# lisa_l.net
KiCad netlist of a schematic drawn in EAGLE
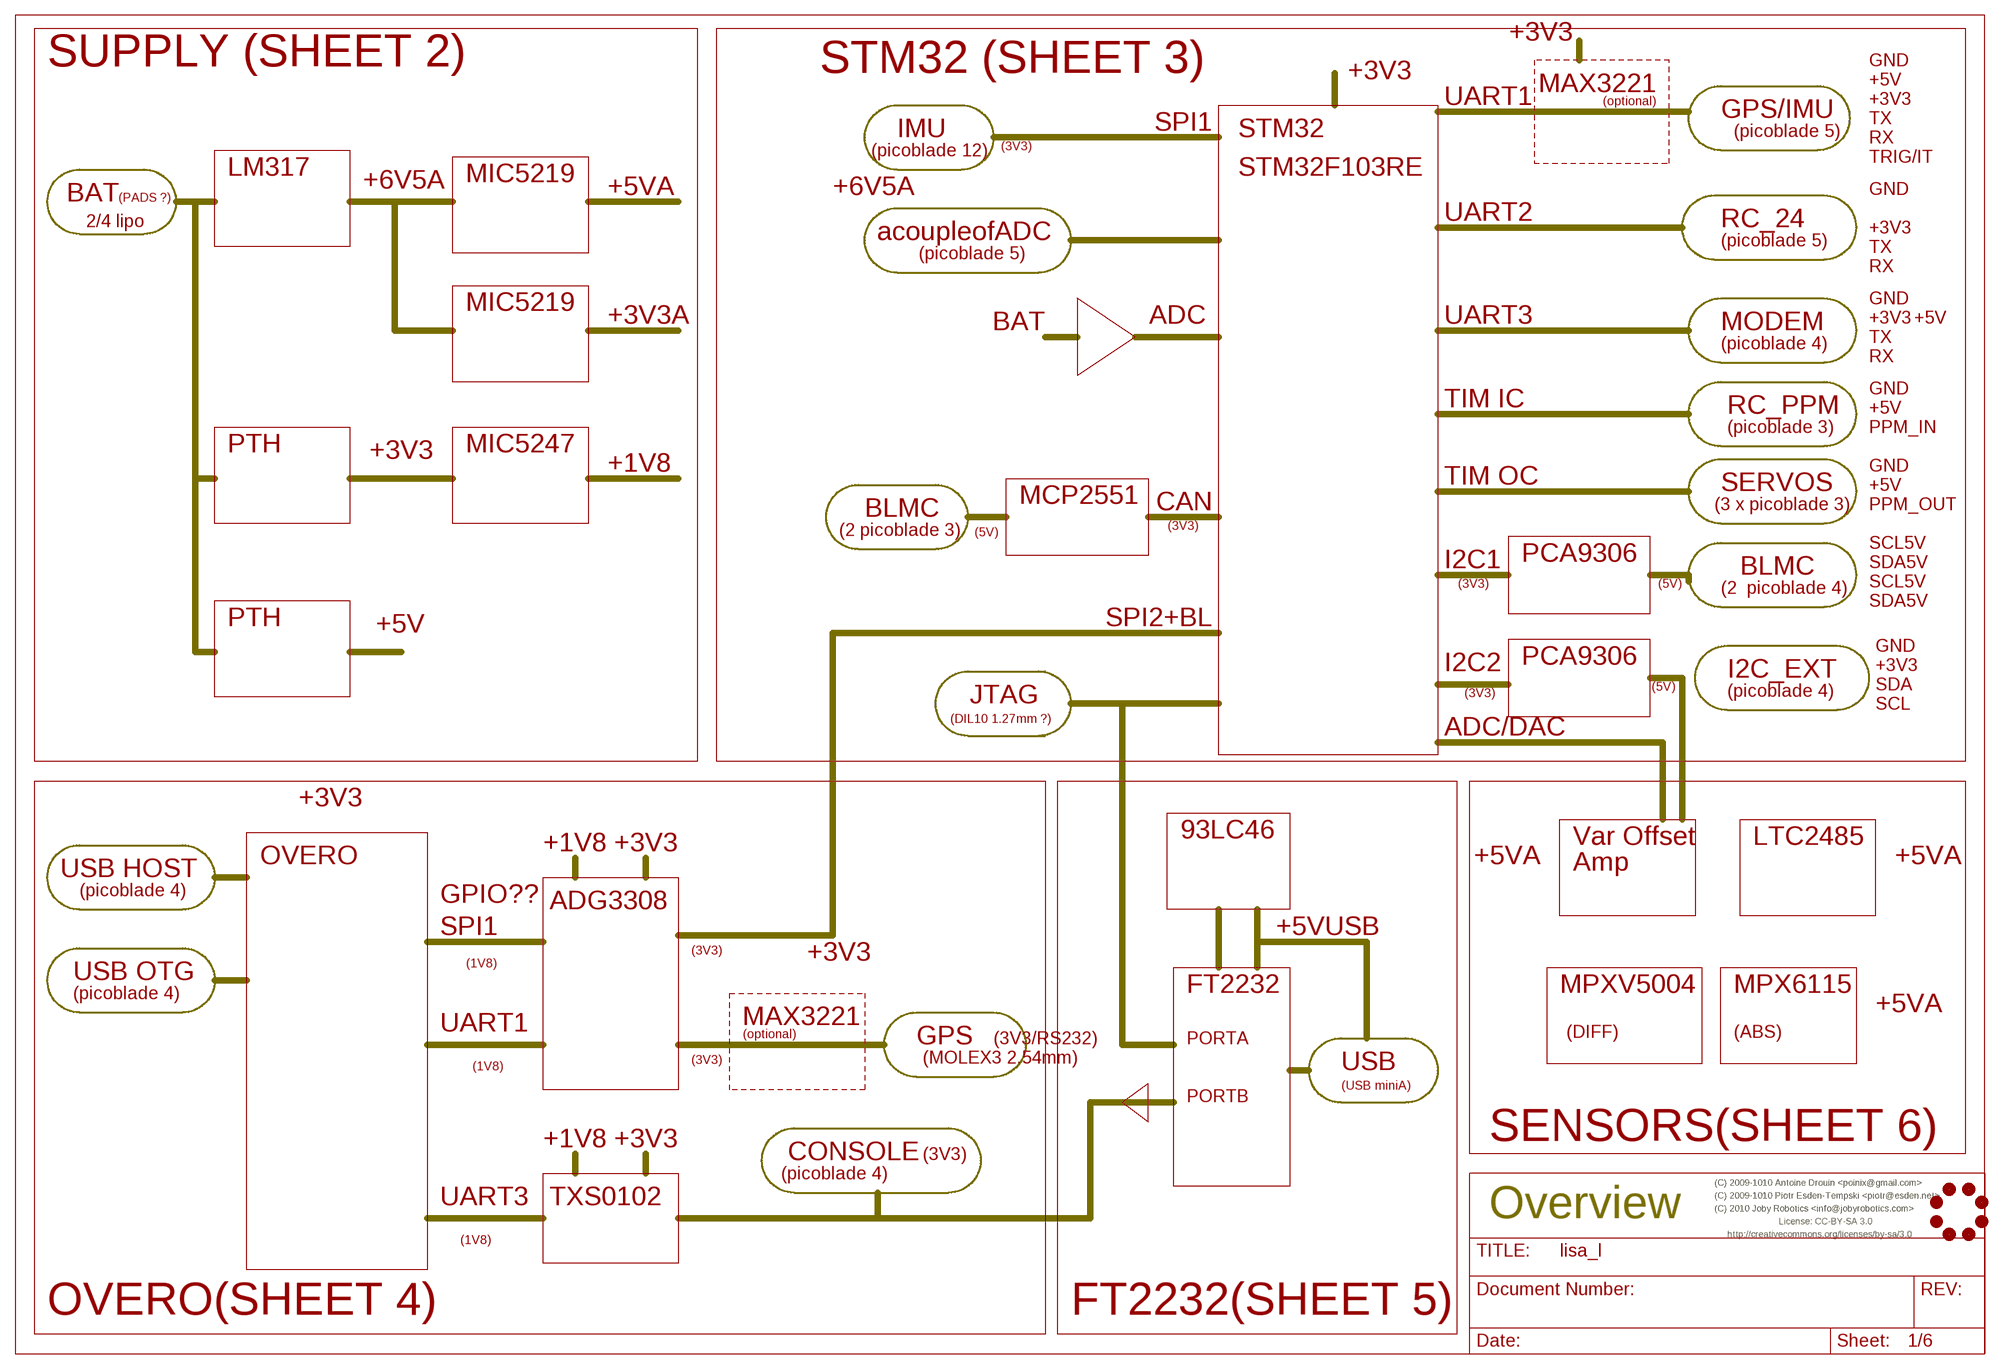
[diagram p0: schematic, sheet 1]
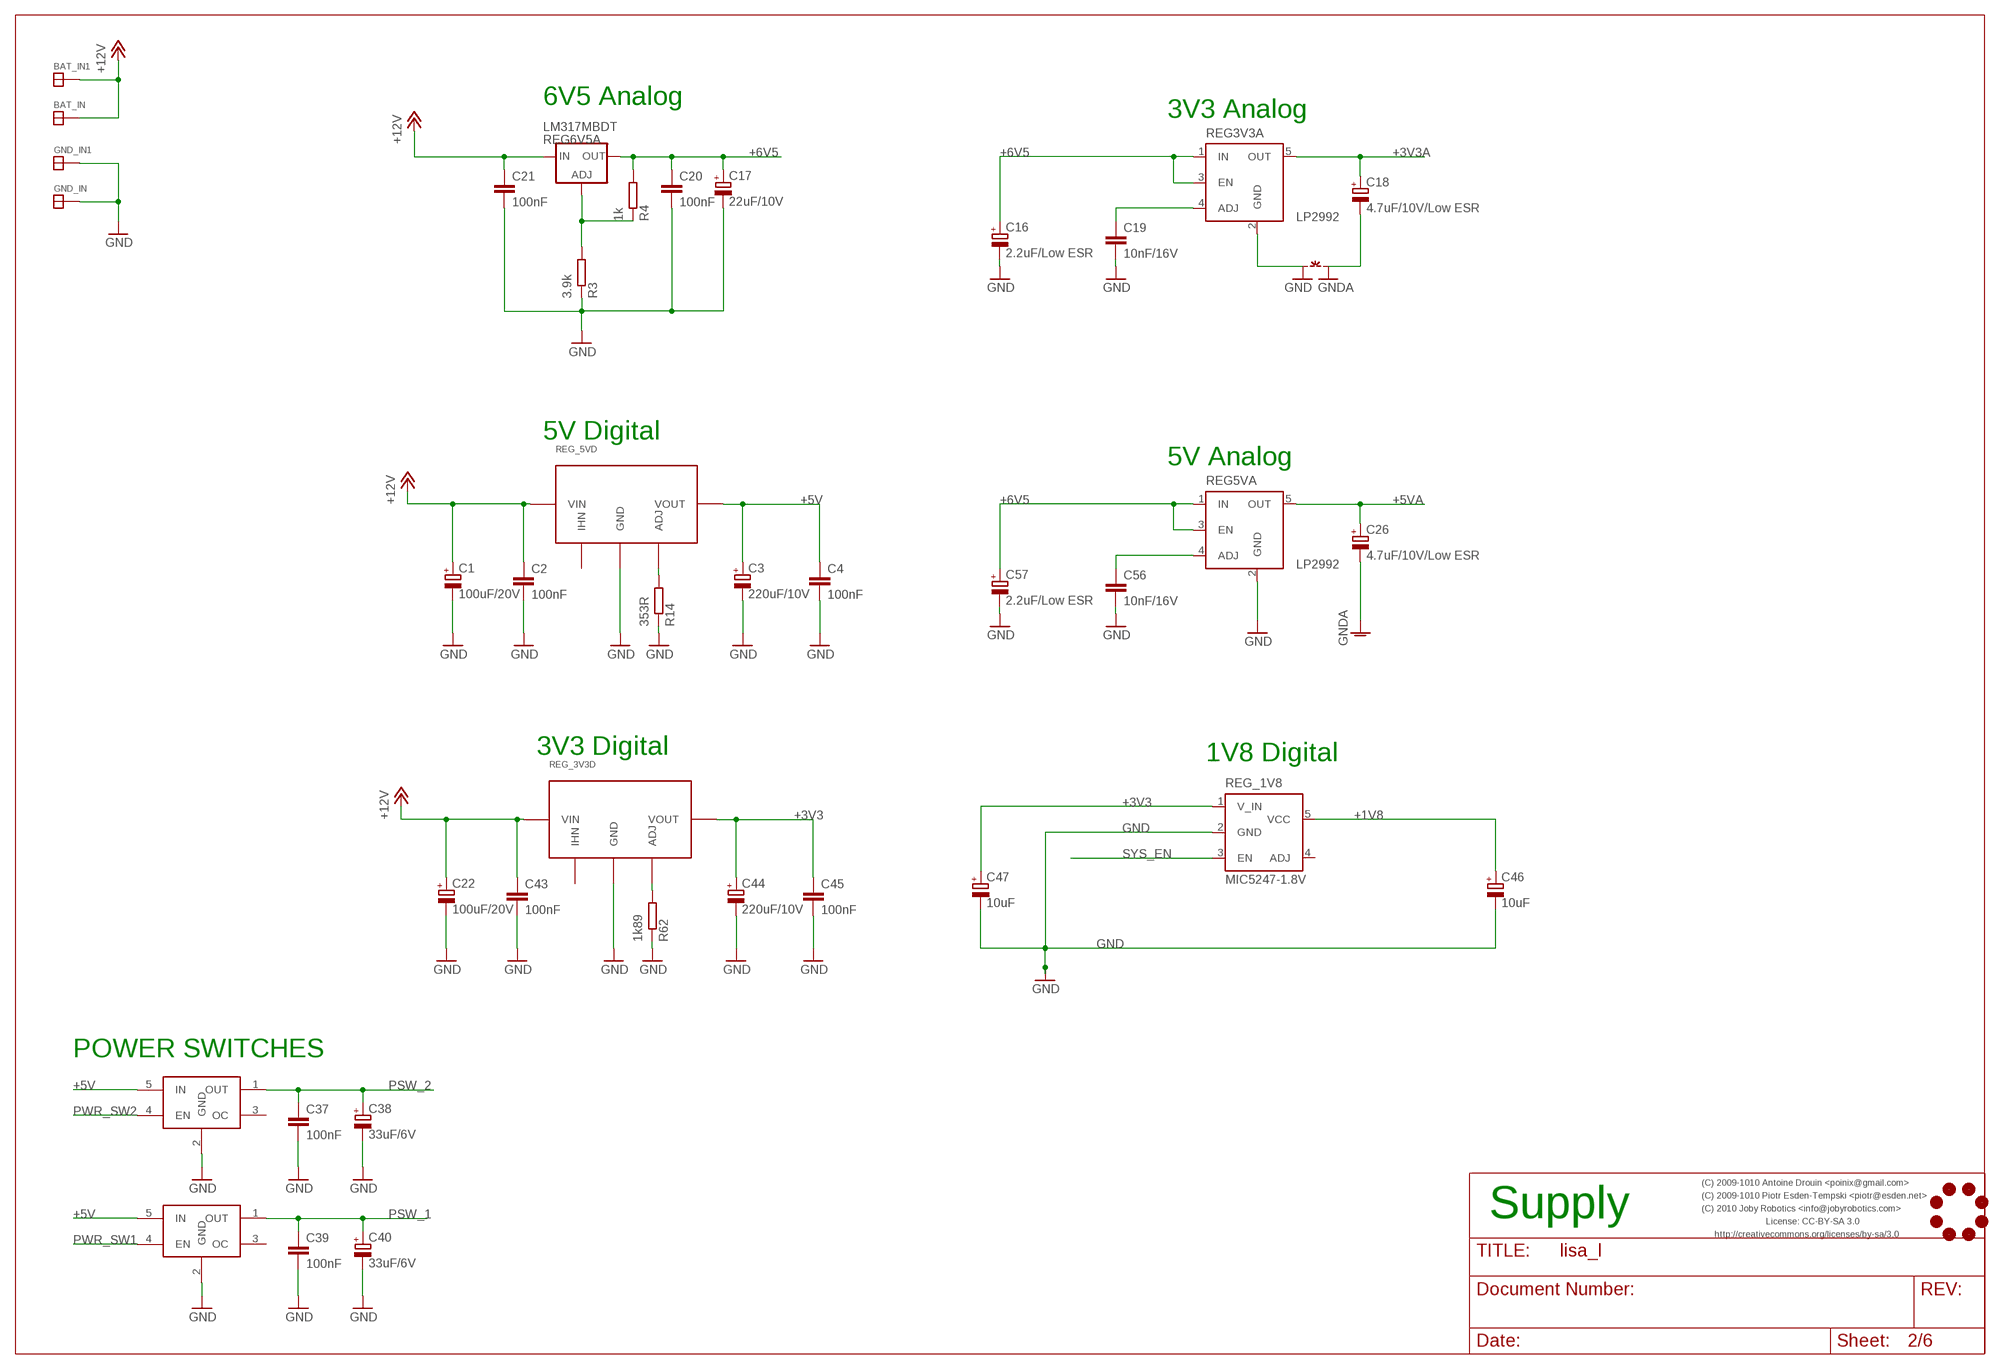
[diagram p1: schematic, sheet 2]
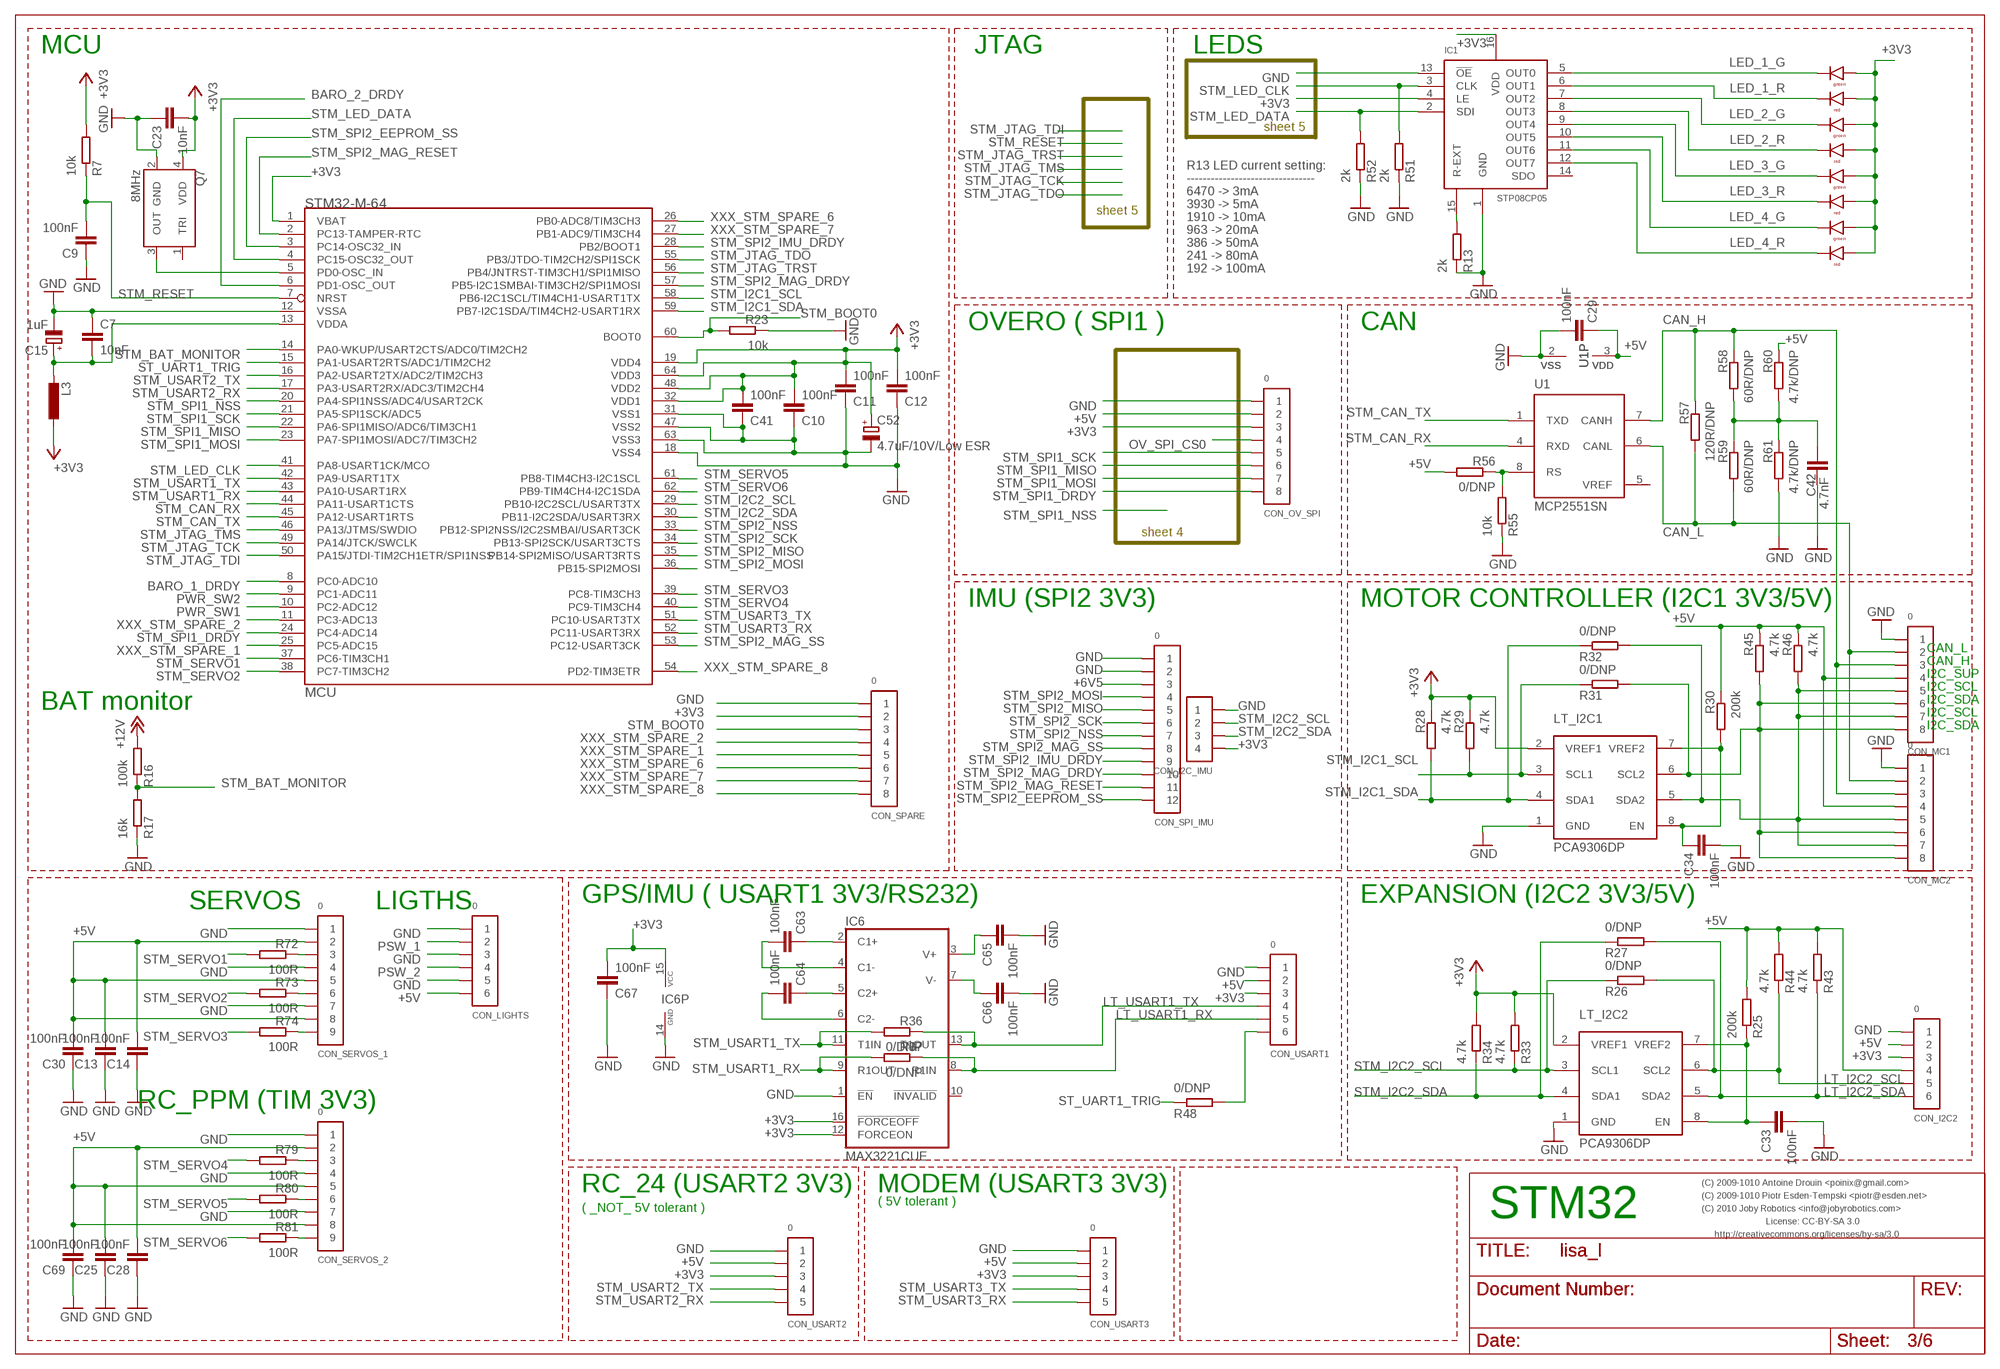
[diagram p2: schematic, sheet 3]
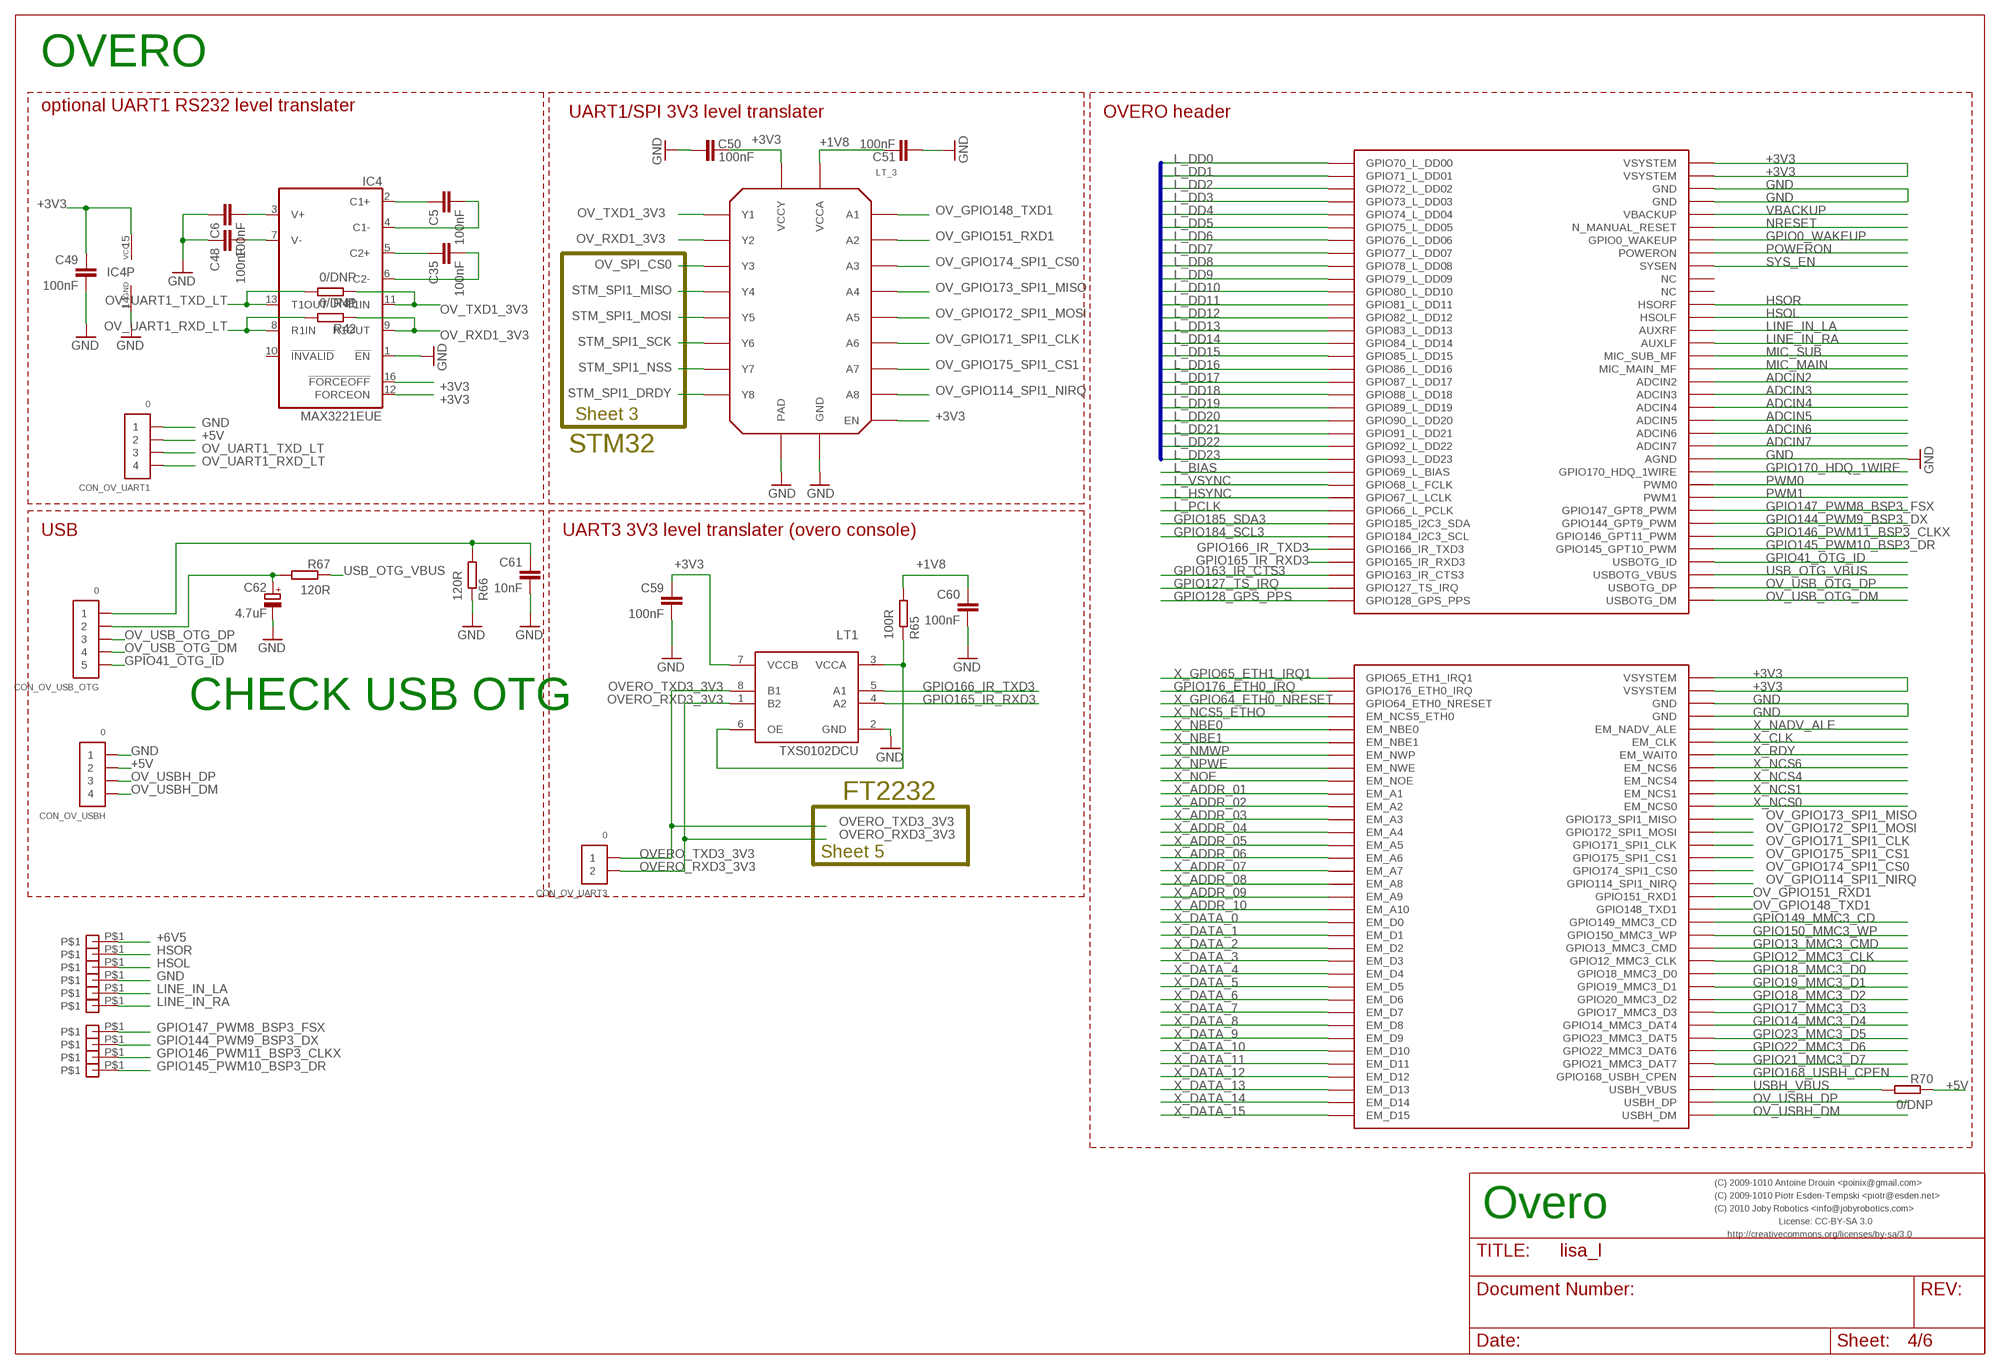
[diagram p3: schematic, sheet 4]
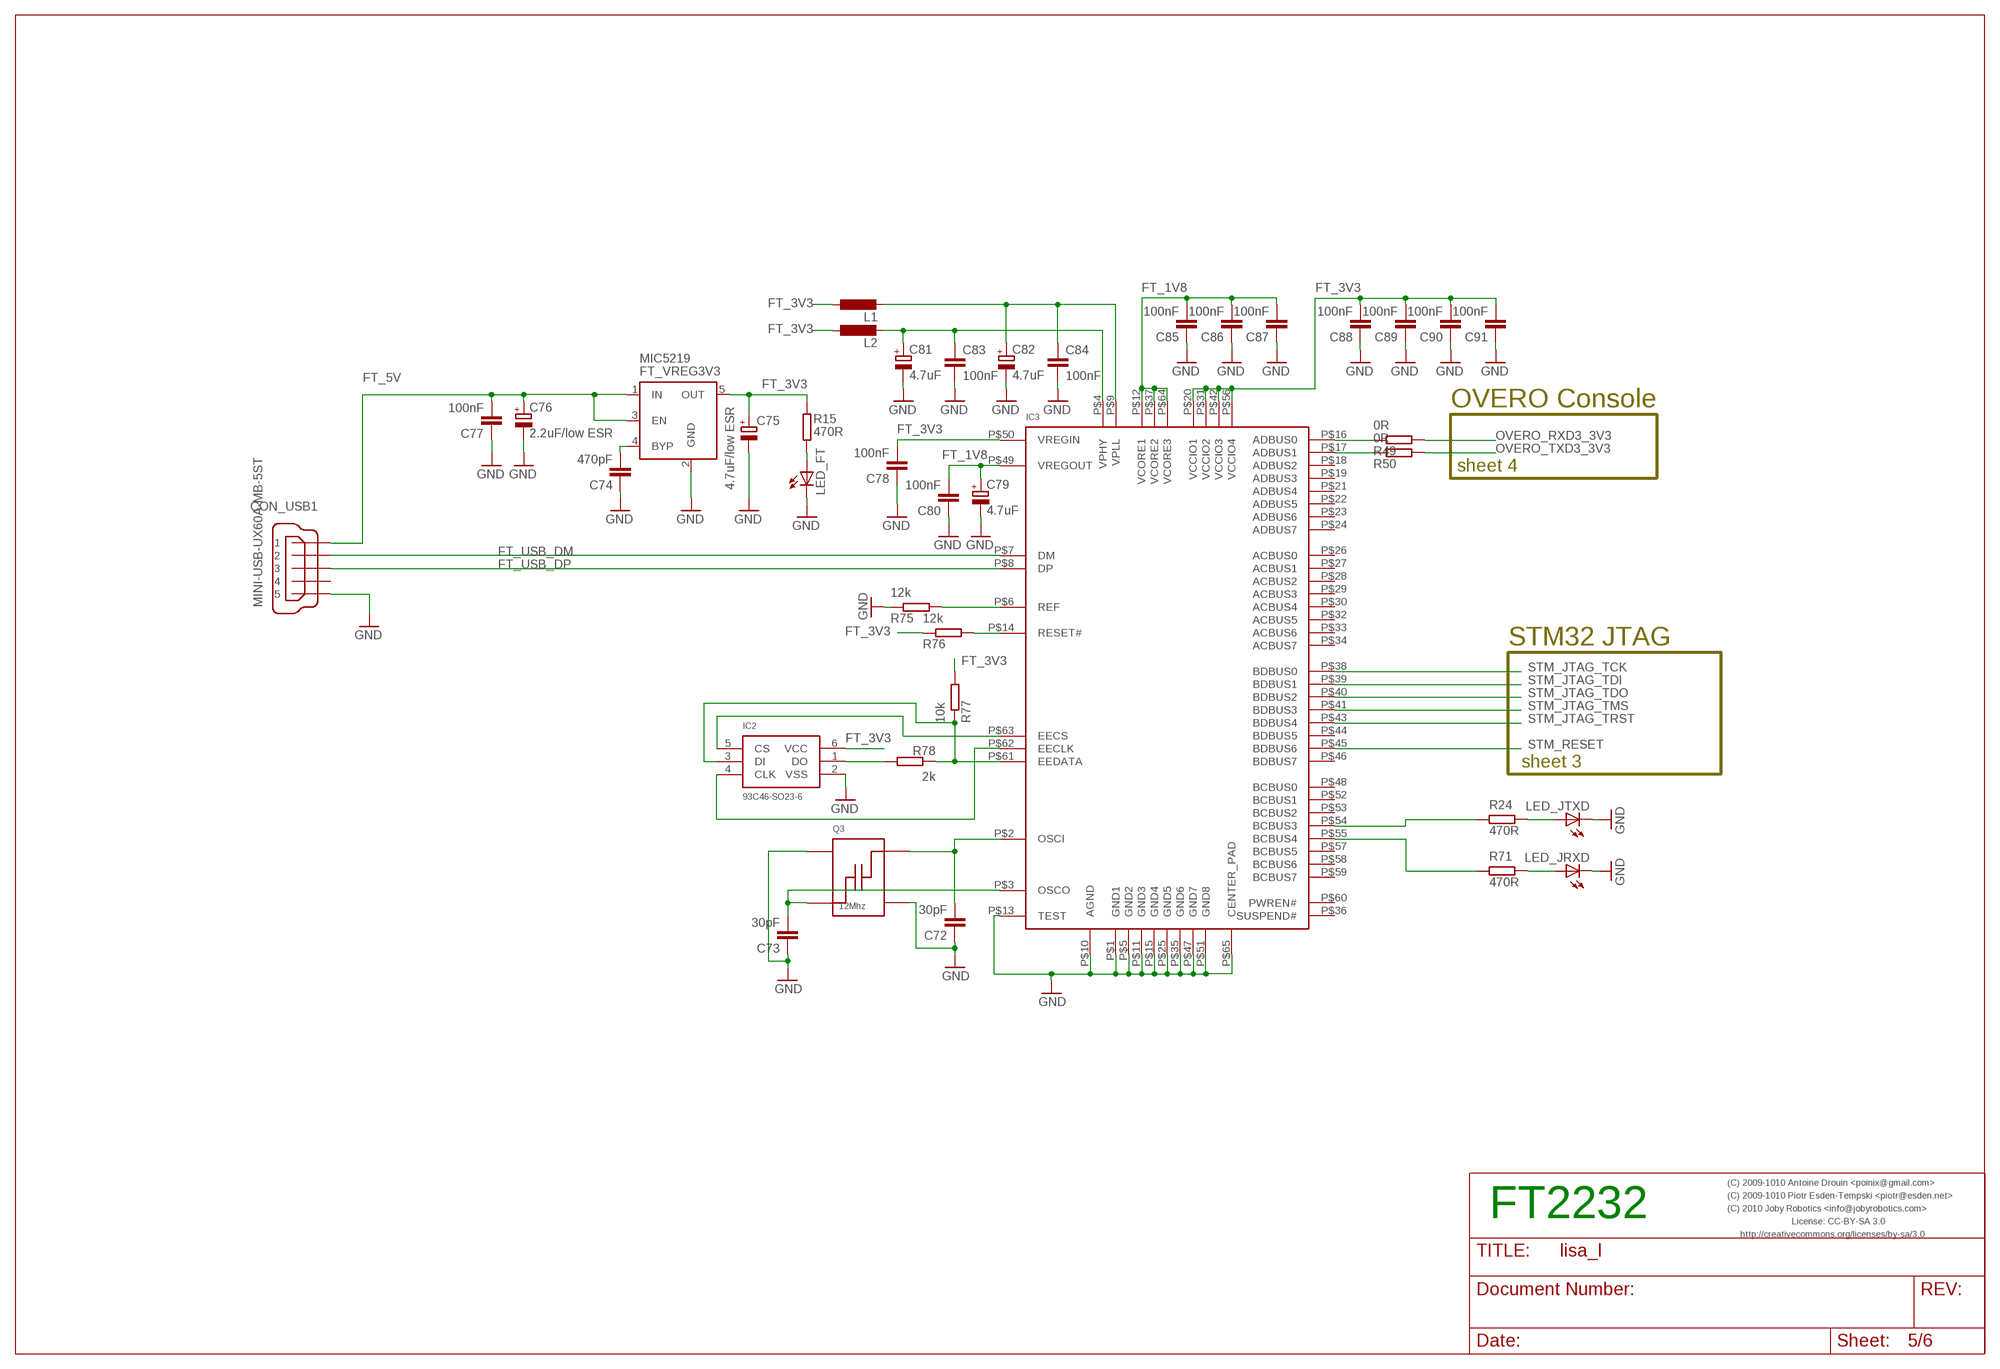
[diagram p4: schematic, sheet 5]
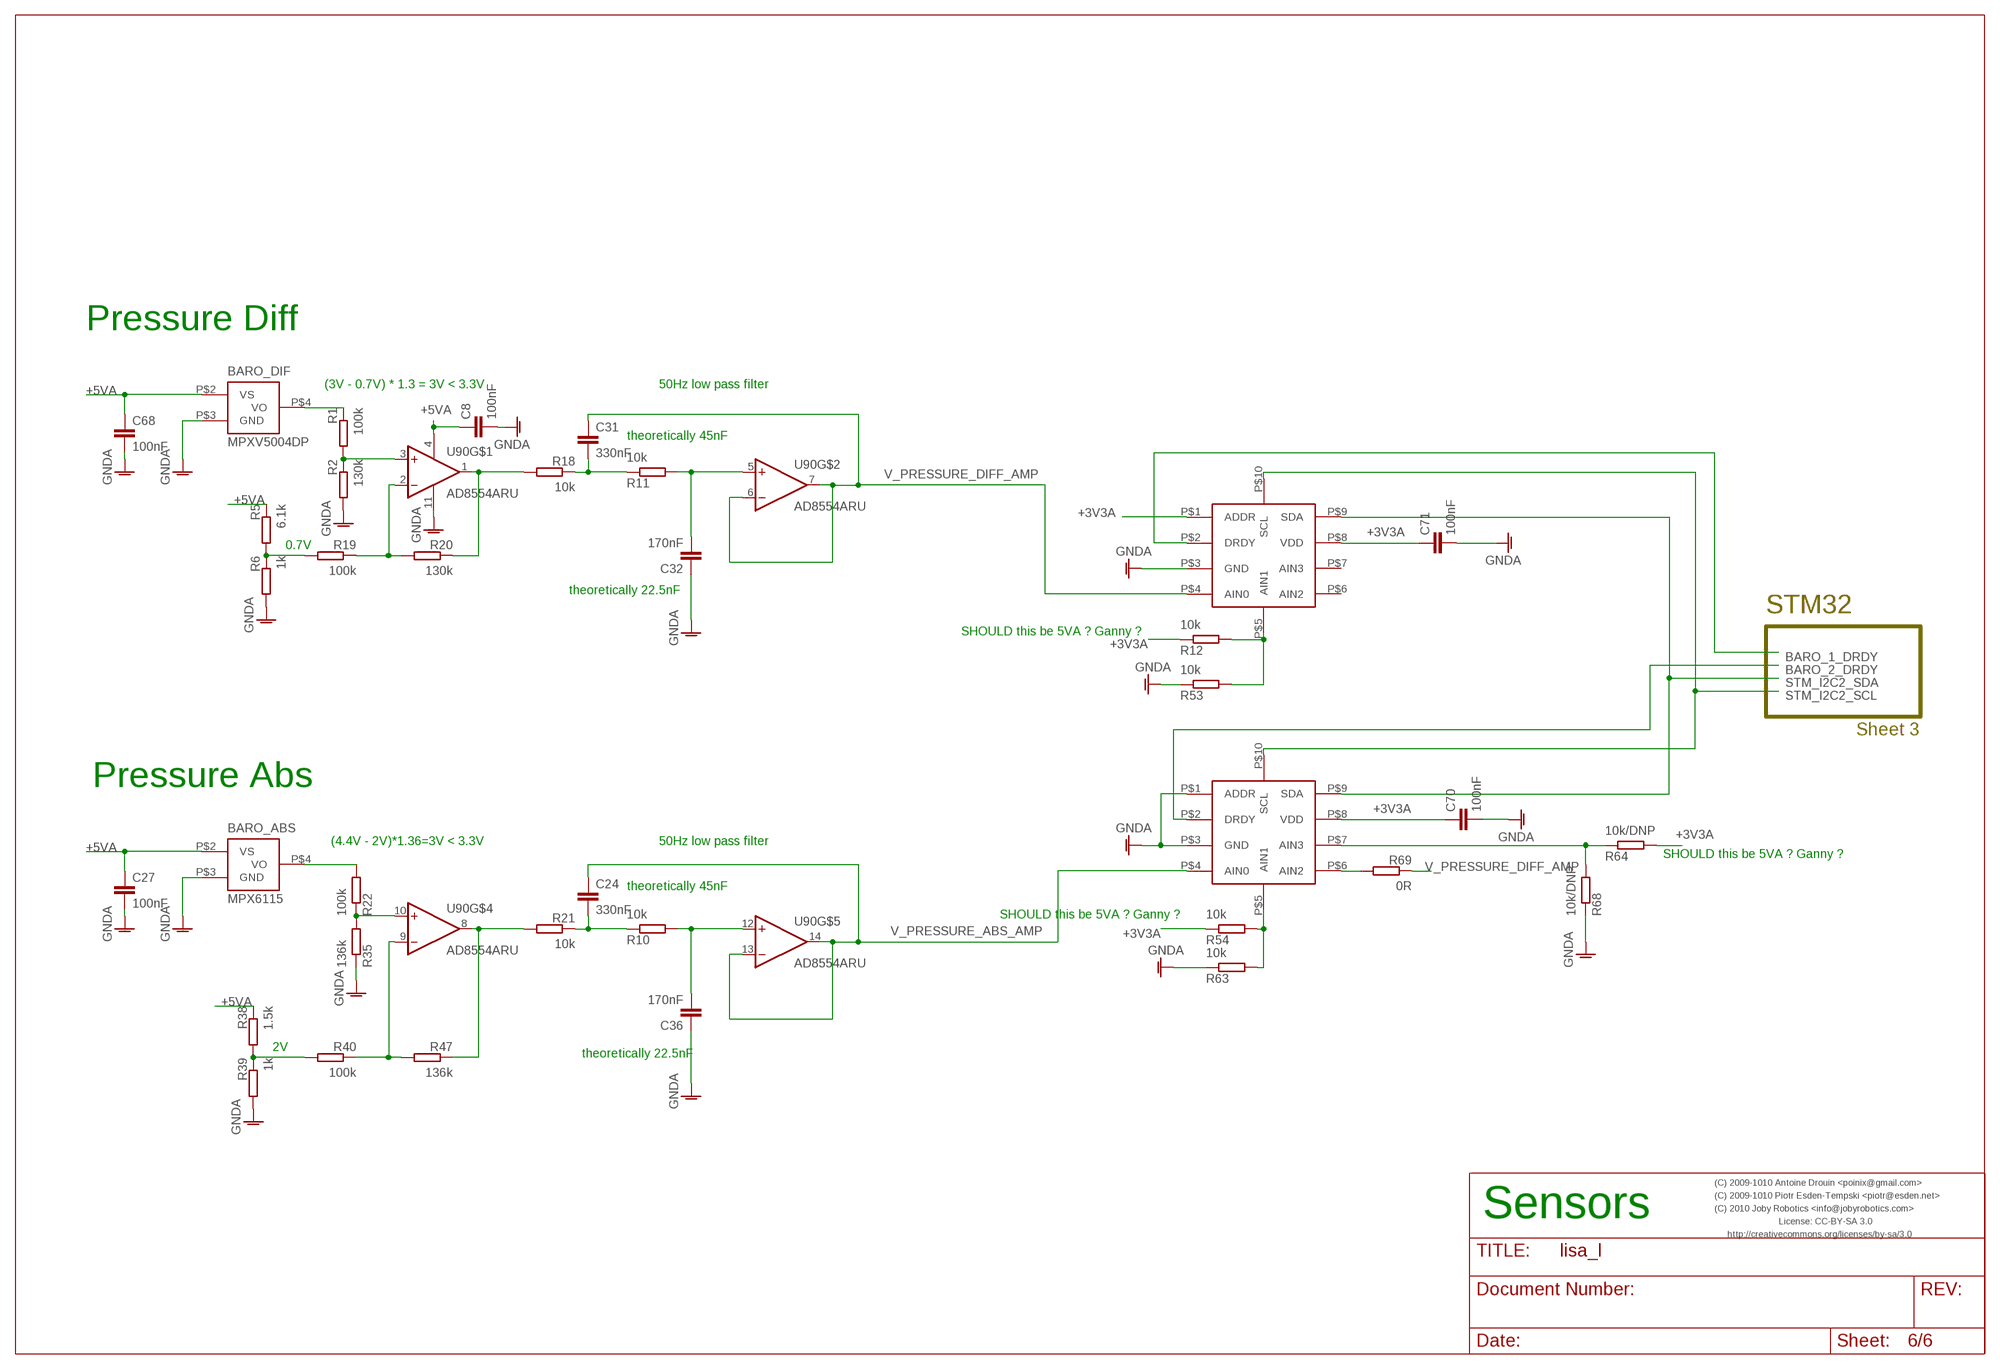
[diagram p5: schematic, sheet 6]

(export (version "E")
  (design (tool "Eeschema 10.0.6"))
  (components
    (comp (ref "C7")
      (value "10nF")
      (footprint "eagle-import:0603-CAP")
      (libsource (lib "eagle-import") (part "CAPACITOR-0603"))
    )
    (comp (ref "C9")
      (value "100nF")
      (footprint "eagle-import:0603-CAP")
      (libsource (lib "eagle-import") (part "res_cap_CAPACITOR-0603"))
    )
    (comp (ref "C10")
      (value "100nF")
      (footprint "eagle-import:0603-CAP")
      (libsource (lib "eagle-import") (part "CAPACITOR-0603"))
    )
    (comp (ref "C11")
      (value "100nF")
      (footprint "eagle-import:0603-CAP")
      (libsource (lib "eagle-import") (part "CAPACITOR-0603"))
    )
    (comp (ref "C12")
      (value "100nF")
      (footprint "eagle-import:0603-CAP")
      (libsource (lib "eagle-import") (part "CAPACITOR-0603"))
    )
    (comp (ref "C13")
      (value "100nF")
      (footprint "eagle-import:0603-CAP")
      (libsource (lib "eagle-import") (part "CAPACITOR-0603"))
    )
    (comp (ref "C14")
      (value "100nF")
      (footprint "eagle-import:0603-CAP")
      (libsource (lib "eagle-import") (part "CAPACITOR-0603"))
    )
    (comp (ref "C15")
      (value "1uF")
      (footprint "eagle-import:0603-POL-CAP")
      (libsource (lib "eagle-import") (part "CAPACITOR-POL-0603"))
    )
    (comp (ref "C23")
      (value "10nF")
      (footprint "eagle-import:0603-CAP")
      (libsource (lib "eagle-import") (part "CAPACITOR-0603"))
    )
    (comp (ref "C25")
      (value "100nF")
      (footprint "eagle-import:0603-CAP")
      (libsource (lib "eagle-import") (part "CAPACITOR-0603"))
    )
    (comp (ref "C28")
      (value "100nF")
      (footprint "eagle-import:0603-CAP")
      (libsource (lib "eagle-import") (part "CAPACITOR-0603"))
    )
    (comp (ref "C29")
      (value "100nF")
      (footprint "eagle-import:0603-CAP")
      (libsource (lib "eagle-import") (part "CAPACITOR-0603"))
    )
    (comp (ref "C30")
      (value "100nF")
      (footprint "eagle-import:0603-CAP")
      (libsource (lib "eagle-import") (part "CAPACITOR-0603"))
    )
    (comp (ref "C33")
      (value "100nF")
      (footprint "eagle-import:0603-CAP")
      (libsource (lib "eagle-import") (part "CAPACITOR-0603"))
    )
    (comp (ref "C34")
      (value "100nF")
      (footprint "eagle-import:0603-CAP")
      (libsource (lib "eagle-import") (part "CAPACITOR-0603"))
    )
    (comp (ref "C41")
      (value "100nF")
      (footprint "eagle-import:0603-CAP")
      (libsource (lib "eagle-import") (part "CAPACITOR-0603"))
    )
    (comp (ref "C42")
      (value "4.7nF")
      (footprint "eagle-import:0603-CAP")
      (libsource (lib "eagle-import") (part "CAPACITOR-0603"))
    )
    (comp (ref "C52")
      (value "4.7uF/10V/Low ESR")
      (footprint "eagle-import:0603-POL-CAP")
      (libsource (lib "eagle-import") (part "CAPACITOR-POL-0603"))
    )
    (comp (ref "C63")
      (value "100nF")
      (footprint "eagle-import:0603-CAP")
      (libsource (lib "eagle-import") (part "CAPACITOR-0603"))
    )
    (comp (ref "C64")
      (value "100nF")
      (footprint "eagle-import:0603-CAP")
      (libsource (lib "eagle-import") (part "CAPACITOR-0603"))
    )
    (comp (ref "C65")
      (value "100nF")
      (footprint "eagle-import:0603-CAP")
      (libsource (lib "eagle-import") (part "CAPACITOR-0603"))
    )
    (comp (ref "C66")
      (value "100nF")
      (footprint "eagle-import:0603-CAP")
      (libsource (lib "eagle-import") (part "CAPACITOR-0603"))
    )
    (comp (ref "C67")
      (value "100nF")
      (footprint "eagle-import:0603-CAP")
      (libsource (lib "eagle-import") (part "CAPACITOR-0603"))
    )
    (comp (ref "C69")
      (value "100nF")
      (footprint "eagle-import:0603-CAP")
      (libsource (lib "eagle-import") (part "CAPACITOR-0603"))
    )
    (comp (ref "CON_I2C2")
      (value "0")
      (footprint "eagle-import:PB-53261-06")
      (libsource (lib "eagle-import") (part "CONN_6-1-53261"))
    )
    (comp (ref "CON_I2C_IMU")
      (value "CONN_4-1-53398")
      (footprint "eagle-import:PB-53398-04")
      (libsource (lib "eagle-import") (part "CONN_4-1-53398"))
    )
    (comp (ref "CON_LIGHTS")
      (value "0")
      (footprint "eagle-import:PB-53261-06")
      (libsource (lib "eagle-import") (part "CONN_6-1-53261"))
    )
    (comp (ref "CON_MC1")
      (value "0")
      (footprint "eagle-import:PB-53261-08")
      (libsource (lib "eagle-import") (part "CONN_8-1-53261"))
    )
    (comp (ref "CON_MC2")
      (value "0")
      (footprint "eagle-import:PB-53261-08")
      (libsource (lib "eagle-import") (part "CONN_8-1-53261"))
    )
    (comp (ref "CON_OV_SPI")
      (value "0")
      (footprint "eagle-import:PB-53398-08")
      (libsource (lib "eagle-import") (part "CONN_8-1-53398"))
    )
    (comp (ref "CON_SERVOS_1")
      (value "0")
      (footprint "eagle-import:PB-53261-09")
      (libsource (lib "eagle-import") (part "CONN_9-1-53261"))
    )
    (comp (ref "CON_SERVOS_2")
      (value "0")
      (footprint "eagle-import:PB-53261-09")
      (libsource (lib "eagle-import") (part "CONN_9-1-53261"))
    )
    (comp (ref "CON_SPARE")
      (value "0")
      (footprint "eagle-import:PB-53261-08")
      (libsource (lib "eagle-import") (part "CONN_8-1-53261"))
    )
    (comp (ref "CON_SPI_IMU")
      (value "0")
      (footprint "eagle-import:PB-53398-12")
      (libsource (lib "eagle-import") (part "CONN_12-1-53398"))
    )
    (comp (ref "CON_USART1")
      (value "0")
      (footprint "eagle-import:PB-53398-06")
      (libsource (lib "eagle-import") (part "CONN_6-1-53398"))
    )
    (comp (ref "CON_USART2")
      (value "0")
      (footprint "eagle-import:PB-53261-05")
      (libsource (lib "eagle-import") (part "CONN_5-1-53261"))
    )
    (comp (ref "CON_USART3")
      (value "0")
      (footprint "eagle-import:PB-53261-05")
      (libsource (lib "eagle-import") (part "CONN_5-1-53261"))
    )
    (comp (ref "IC1")
      (value "STP08CP05")
      (footprint "eagle-import:TSSOP16")
      (libsource (lib "eagle-import") (part "STP08CP05"))
    )
    (comp (ref "IC6")
      (value "MAX3221CUE")
      (footprint "eagle-import:TSSOP16")
      (libsource (lib "eagle-import") (part "MAX3221UEC"))
    )
    (comp (ref "L3")
      (value "INDUCTOR-0603")
      (footprint "eagle-import:0603-IND")
      (libsource (lib "eagle-import") (part "INDUCTOR-0603"))
    )
    (comp (ref "LED_1")
      (value "LED_DUO")
      (footprint "eagle-import:DUO_LED")
      (libsource (lib "eagle-import") (part "LED_DUO"))
    )
    (comp (ref "LED_2")
      (value "LED_DUO")
      (footprint "eagle-import:DUO_LED")
      (libsource (lib "eagle-import") (part "LED_DUO"))
    )
    (comp (ref "LED_3")
      (value "LED_DUO")
      (footprint "eagle-import:DUO_LED")
      (libsource (lib "eagle-import") (part "LED_DUO"))
    )
    (comp (ref "LED_4")
      (value "LED_DUO")
      (footprint "eagle-import:DUO_LED")
      (libsource (lib "eagle-import") (part "LED_DUO"))
    )
    (comp (ref "LT_I2C1")
      (value "PCA9306DP")
      (footprint "eagle-import:TSSOP_B3")
      (libsource (lib "eagle-import") (part "PCA9306DP"))
    )
    (comp (ref "LT_I2C2")
      (value "PCA9306DP")
      (footprint "eagle-import:TSSOP_B3")
      (libsource (lib "eagle-import") (part "PCA9306DP"))
    )
    (comp (ref "MCU")
      (value "STM32-M-64")
      (footprint "eagle-import:LQFP64")
      (libsource (lib "eagle-import") (part "STM32-M-64"))
    )
    (comp (ref "Q7")
      (value "8MHz")
      (footprint "eagle-import:ASE_OSCILLATOR")
      (libsource (lib "eagle-import") (part "ASE_ASCILLATOR"))
    )
    (comp (ref "R7")
      (value "10k")
      (footprint "eagle-import:0603-RES")
      (libsource (lib "eagle-import") (part "RESISTOR-0603"))
    )
    (comp (ref "R13")
      (value "2k")
      (footprint "eagle-import:0603-RES")
      (libsource (lib "eagle-import") (part "RESISTOR-0603"))
    )
    (comp (ref "R16")
      (value "100k")
      (footprint "eagle-import:0603-RES")
      (libsource (lib "eagle-import") (part "RESISTOR-0603"))
    )
    (comp (ref "R17")
      (value "16k")
      (footprint "eagle-import:0603-RES")
      (libsource (lib "eagle-import") (part "RESISTOR-0603"))
    )
    (comp (ref "R23")
      (value "10k")
      (footprint "eagle-import:0603-RES")
      (libsource (lib "eagle-import") (part "RESISTOR-0603"))
    )
    (comp (ref "R25")
      (value "200k")
      (footprint "eagle-import:0603-RES")
      (libsource (lib "eagle-import") (part "RESISTOR-0603"))
    )
    (comp (ref "R26")
      (value "0/DNP")
      (footprint "eagle-import:0603-RES")
      (libsource (lib "eagle-import") (part "RESISTOR-0603"))
    )
    (comp (ref "R27")
      (value "0/DNP")
      (footprint "eagle-import:0603-RES")
      (libsource (lib "eagle-import") (part "RESISTOR-0603"))
    )
    (comp (ref "R28")
      (value "4.7k")
      (footprint "eagle-import:0603-RES")
      (libsource (lib "eagle-import") (part "RESISTOR-0603"))
    )
    (comp (ref "R29")
      (value "4.7k")
      (footprint "eagle-import:0603-RES")
      (libsource (lib "eagle-import") (part "RESISTOR-0603"))
    )
    (comp (ref "R30")
      (value "200k")
      (footprint "eagle-import:0603-RES")
      (libsource (lib "eagle-import") (part "RESISTOR-0603"))
    )
    (comp (ref "R31")
      (value "0/DNP")
      (footprint "eagle-import:0603-RES")
      (libsource (lib "eagle-import") (part "RESISTOR-0603"))
    )
    (comp (ref "R32")
      (value "0/DNP")
      (footprint "eagle-import:0603-RES")
      (libsource (lib "eagle-import") (part "RESISTOR-0603"))
    )
    (comp (ref "R33")
      (value "4.7k")
      (footprint "eagle-import:0603-RES")
      (libsource (lib "eagle-import") (part "RESISTOR-0603"))
    )
    (comp (ref "R34")
      (value "4.7k")
      (footprint "eagle-import:0603-RES")
      (libsource (lib "eagle-import") (part "RESISTOR-0603"))
    )
    (comp (ref "R36")
      (value "0/DNP")
      (footprint "eagle-import:0603-RES")
      (libsource (lib "eagle-import") (part "RESISTOR-0603"))
    )
    (comp (ref "R37")
      (value "0/DNP")
      (footprint "eagle-import:0603-RES")
      (libsource (lib "eagle-import") (part "RESISTOR-0603"))
    )
    (comp (ref "R43")
      (value "4.7k")
      (footprint "eagle-import:0603-RES")
      (libsource (lib "eagle-import") (part "RESISTOR-0603"))
    )
    (comp (ref "R44")
      (value "4.7k")
      (footprint "eagle-import:0603-RES")
      (libsource (lib "eagle-import") (part "RESISTOR-0603"))
    )
    (comp (ref "R45")
      (value "4.7k")
      (footprint "eagle-import:0603-RES")
      (libsource (lib "eagle-import") (part "RESISTOR-0603"))
    )
    (comp (ref "R46")
      (value "4.7k")
      (footprint "eagle-import:0603-RES")
      (libsource (lib "eagle-import") (part "RESISTOR-0603"))
    )
    (comp (ref "R48")
      (value "0/DNP")
      (footprint "eagle-import:0603-RES")
      (libsource (lib "eagle-import") (part "RESISTOR-0603"))
    )
    (comp (ref "R51")
      (value "2k")
      (footprint "eagle-import:0603-RES")
      (libsource (lib "eagle-import") (part "RESISTOR-0603"))
    )
    (comp (ref "R52")
      (value "2k")
      (footprint "eagle-import:0603-RES")
      (libsource (lib "eagle-import") (part "RESISTOR-0603"))
    )
    (comp (ref "R55")
      (value "10k")
      (footprint "eagle-import:0603-RES")
      (libsource (lib "eagle-import") (part "RESISTOR-0603"))
    )
    (comp (ref "R56")
      (value "0/DNP")
      (footprint "eagle-import:0603-RES")
      (libsource (lib "eagle-import") (part "RESISTOR-0603"))
    )
    (comp (ref "R57")
      (value "120R/DNP")
      (footprint "eagle-import:0603-RES")
      (libsource (lib "eagle-import") (part "RESISTOR-0603"))
    )
    (comp (ref "R58")
      (value "60R/DNP")
      (footprint "eagle-import:0603-RES")
      (libsource (lib "eagle-import") (part "RESISTOR-0603"))
    )
    (comp (ref "R59")
      (value "60R/DNP")
      (footprint "eagle-import:0603-RES")
      (libsource (lib "eagle-import") (part "RESISTOR-0603"))
    )
    (comp (ref "R60")
      (value "4.7k/DNP")
      (footprint "eagle-import:0603-RES")
      (libsource (lib "eagle-import") (part "RESISTOR-0603"))
    )
    (comp (ref "R61")
      (value "4.7k/DNP")
      (footprint "eagle-import:0603-RES")
      (libsource (lib "eagle-import") (part "RESISTOR-0603"))
    )
    (comp (ref "R72")
      (value "100R")
      (footprint "eagle-import:0603-RES")
      (libsource (lib "eagle-import") (part "RESISTOR-0603"))
    )
    (comp (ref "R73")
      (value "100R")
      (footprint "eagle-import:0603-RES")
      (libsource (lib "eagle-import") (part "RESISTOR-0603"))
    )
    (comp (ref "R74")
      (value "100R")
      (footprint "eagle-import:0603-RES")
      (libsource (lib "eagle-import") (part "RESISTOR-0603"))
    )
    (comp (ref "R79")
      (value "100R")
      (footprint "eagle-import:0603-RES")
      (libsource (lib "eagle-import") (part "RESISTOR-0603"))
    )
    (comp (ref "R80")
      (value "100R")
      (footprint "eagle-import:0603-RES")
      (libsource (lib "eagle-import") (part "RESISTOR-0603"))
    )
    (comp (ref "R81")
      (value "100R")
      (footprint "eagle-import:0603-RES")
      (libsource (lib "eagle-import") (part "RESISTOR-0603"))
    )
    (comp (ref "U1")
      (value "MCP2551SN")
      (footprint "eagle-import:SO-08")
      (libsource (lib "eagle-import") (part "MCP2551SN"))
    )
    (comp (ref "C5")
      (value "100nF")
      (footprint "eagle-import:0603-CAP")
      (libsource (lib "eagle-import") (part "CAPACITOR-0603"))
    )
    (comp (ref "C6")
      (value "100nF")
      (footprint "eagle-import:0603-CAP")
      (libsource (lib "eagle-import") (part "CAPACITOR-0603"))
    )
    (comp (ref "C35")
      (value "100nF")
      (footprint "eagle-import:0603-CAP")
      (libsource (lib "eagle-import") (part "CAPACITOR-0603"))
    )
    (comp (ref "C48")
      (value "100nF")
      (footprint "eagle-import:0603-CAP")
      (libsource (lib "eagle-import") (part "CAPACITOR-0603"))
    )
    (comp (ref "C49")
      (value "100nF")
      (footprint "eagle-import:0603-CAP")
      (libsource (lib "eagle-import") (part "CAPACITOR-0603"))
    )
    (comp (ref "C50")
      (value "100nF")
      (footprint "eagle-import:0603-CAP")
      (libsource (lib "eagle-import") (part "CAPACITOR-0603"))
    )
    (comp (ref "C51")
      (value "100nF")
      (footprint "eagle-import:0603-CAP")
      (libsource (lib "eagle-import") (part "CAPACITOR-0603"))
    )
    (comp (ref "C59")
      (value "100nF")
      (footprint "eagle-import:0603-CAP")
      (libsource (lib "eagle-import") (part "CAPACITOR-0603"))
    )
    (comp (ref "C60")
      (value "100nF")
      (footprint "eagle-import:0603-CAP")
      (libsource (lib "eagle-import") (part "CAPACITOR-0603"))
    )
    (comp (ref "C61")
      (value "10nF")
      (footprint "eagle-import:0603-CAP")
      (libsource (lib "eagle-import") (part "CAPACITOR-0603"))
    )
    (comp (ref "C62")
      (value "4.7uF")
      (footprint "eagle-import:0603-POL-CAP")
      (libsource (lib "eagle-import") (part "CAPACITOR-POL-0603"))
    )
    (comp (ref "CON_OV_UART1")
      (value "0")
      (footprint "eagle-import:PB-53261-04")
      (libsource (lib "eagle-import") (part "CONN_4-1-53261"))
    )
    (comp (ref "CON_OV_UART3")
      (value "0")
      (footprint "eagle-import:PB-53261-02")
      (libsource (lib "eagle-import") (part "CONN_2-1-53261"))
    )
    (comp (ref "CON_OV_USBH")
      (value "0")
      (footprint "eagle-import:PB-53261-04")
      (libsource (lib "eagle-import") (part "CONN_4-1-53261"))
    )
    (comp (ref "CON_OV_USB_OTG")
      (value "0")
      (footprint "eagle-import:PB-53261-05")
      (libsource (lib "eagle-import") (part "CONN_5-1-53261"))
    )
    (comp (ref "IC4")
      (value "MAX3221EUE")
      (footprint "eagle-import:TSSOP16")
      (libsource (lib "eagle-import") (part "MAX3221UEE"))
    )
    (comp (ref "J3&4")
      (value "OVERO")
      (footprint "eagle-import:OVERO")
      (libsource (lib "eagle-import") (part "OVERO"))
    )
    (comp (ref "LT1")
      (value "TXS0102DCU")
      (footprint "eagle-import:US8")
      (libsource (lib "eagle-import") (part "TXS0102DCU"))
    )
    (comp (ref "LT_3")
      (value "AD3308BCPZ")
      (footprint "eagle-import:LFCSP-20")
      (libsource (lib "eagle-import") (part "AD3308BCPZ"))
    )
    (comp (ref "R41")
      (value "0/DNP")
      (footprint "eagle-import:0603-RES")
      (libsource (lib "eagle-import") (part "RESISTOR-0603"))
    )
    (comp (ref "R42")
      (value "0/DNP")
      (footprint "eagle-import:0603-RES")
      (libsource (lib "eagle-import") (part "RESISTOR-0603"))
    )
    (comp (ref "R65")
      (value "100R")
      (footprint "eagle-import:0603-RES")
      (libsource (lib "eagle-import") (part "RESISTOR-0603"))
    )
    (comp (ref "R66")
      (value "120R")
      (footprint "eagle-import:0603-RES")
      (libsource (lib "eagle-import") (part "RESISTOR-0603"))
    )
    (comp (ref "R67")
      (value "120R")
      (footprint "eagle-import:0603-RES")
      (libsource (lib "eagle-import") (part "RESISTOR-0603"))
    )
    (comp (ref "R70")
      (value "0/DNP")
      (footprint "eagle-import:0603-RES")
      (libsource (lib "eagle-import") (part "RESISTOR-0603"))
    )
    (comp (ref "U$1")
      (value "SOLDER_PAD")
      (footprint "eagle-import:SOLDER_PAD_SMALL")
      (libsource (lib "eagle-import") (part "poinix_SOLDER_PAD"))
    )
    (comp (ref "U$2")
      (value "SOLDER_PAD")
      (footprint "eagle-import:SOLDER_PAD_SMALL")
      (libsource (lib "eagle-import") (part "poinix_SOLDER_PAD"))
    )
    (comp (ref "U$3")
      (value "SOLDER_PAD")
      (footprint "eagle-import:SOLDER_PAD_SMALL")
      (libsource (lib "eagle-import") (part "poinix_SOLDER_PAD"))
    )
    (comp (ref "U$4")
      (value "SOLDER_PAD")
      (footprint "eagle-import:SOLDER_PAD_SMALL")
      (libsource (lib "eagle-import") (part "poinix_SOLDER_PAD"))
    )
    (comp (ref "U$5")
      (value "SOLDER_PAD")
      (footprint "eagle-import:SOLDER_PAD_SMALL")
      (libsource (lib "eagle-import") (part "poinix_SOLDER_PAD"))
    )
    (comp (ref "U$6")
      (value "SOLDER_PAD")
      (footprint "eagle-import:SOLDER_PAD_SMALL")
      (libsource (lib "eagle-import") (part "poinix_SOLDER_PAD"))
    )
    (comp (ref "U$7")
      (value "SOLDER_PAD")
      (footprint "eagle-import:SOLDER_PAD_SMALL")
      (libsource (lib "eagle-import") (part "poinix_SOLDER_PAD"))
    )
    (comp (ref "U$8")
      (value "SOLDER_PAD")
      (footprint "eagle-import:SOLDER_PAD_SMALL")
      (libsource (lib "eagle-import") (part "poinix_SOLDER_PAD"))
    )
    (comp (ref "U$9")
      (value "SOLDER_PAD")
      (footprint "eagle-import:SOLDER_PAD_SMALL")
      (libsource (lib "eagle-import") (part "poinix_SOLDER_PAD"))
    )
    (comp (ref "U$10")
      (value "SOLDER_PAD")
      (footprint "eagle-import:SOLDER_PAD_SMALL")
      (libsource (lib "eagle-import") (part "poinix_SOLDER_PAD"))
    )
    (comp (ref "C72")
      (value "30pF")
      (footprint "eagle-import:0603-CAP")
      (libsource (lib "eagle-import") (part "res_cap_CAPACITOR-0603"))
    )
    (comp (ref "C73")
      (value "30pF")
      (footprint "eagle-import:0603-CAP")
      (libsource (lib "eagle-import") (part "res_cap_CAPACITOR-0603"))
    )
    (comp (ref "C74")
      (value "470pF")
      (footprint "eagle-import:0603-CAP")
      (libsource (lib "eagle-import") (part "res_cap_CAPACITOR-0603"))
    )
    (comp (ref "C75")
      (value "4.7uF/low ESR")
      (footprint "eagle-import:0603-POL-CAP")
      (libsource (lib "eagle-import") (part "CAPACITOR-POL-0603"))
    )
    (comp (ref "C76")
      (value "2.2uF/low ESR")
      (footprint "eagle-import:0603-POL-CAP")
      (libsource (lib "eagle-import") (part "CAPACITOR-POL-0603"))
    )
    (comp (ref "C77")
      (value "100nF")
      (footprint "eagle-import:0603-CAP")
      (libsource (lib "eagle-import") (part "res_cap_CAPACITOR-0603"))
    )
    (comp (ref "C78")
      (value "100nF")
      (footprint "eagle-import:0603-CAP")
      (libsource (lib "eagle-import") (part "res_cap_CAPACITOR-0603"))
    )
    (comp (ref "C79")
      (value "4.7uF")
      (footprint "eagle-import:0603-POL-CAP")
      (libsource (lib "eagle-import") (part "CAPACITOR-POL-0603"))
    )
    (comp (ref "C80")
      (value "100nF")
      (footprint "eagle-import:0603-CAP")
      (libsource (lib "eagle-import") (part "res_cap_CAPACITOR-0603"))
    )
    (comp (ref "C81")
      (value "4.7uF")
      (footprint "eagle-import:0603-POL-CAP")
      (libsource (lib "eagle-import") (part "CAPACITOR-POL-0603"))
    )
    (comp (ref "C82")
      (value "4.7uF")
      (footprint "eagle-import:0603-POL-CAP")
      (libsource (lib "eagle-import") (part "CAPACITOR-POL-0603"))
    )
    (comp (ref "C83")
      (value "100nF")
      (footprint "eagle-import:0603-CAP")
      (libsource (lib "eagle-import") (part "res_cap_CAPACITOR-0603"))
    )
    (comp (ref "C84")
      (value "100nF")
      (footprint "eagle-import:0603-CAP")
      (libsource (lib "eagle-import") (part "res_cap_CAPACITOR-0603"))
    )
    (comp (ref "C85")
      (value "100nF")
      (footprint "eagle-import:0603-CAP")
      (libsource (lib "eagle-import") (part "res_cap_CAPACITOR-0603"))
    )
    (comp (ref "C86")
      (value "100nF")
      (footprint "eagle-import:0603-CAP")
      (libsource (lib "eagle-import") (part "res_cap_CAPACITOR-0603"))
    )
    (comp (ref "C87")
      (value "100nF")
      (footprint "eagle-import:0603-CAP")
      (libsource (lib "eagle-import") (part "res_cap_CAPACITOR-0603"))
    )
    (comp (ref "C88")
      (value "100nF")
      (footprint "eagle-import:0603-CAP")
      (libsource (lib "eagle-import") (part "res_cap_CAPACITOR-0603"))
    )
    (comp (ref "C89")
      (value "100nF")
      (footprint "eagle-import:0603-CAP")
      (libsource (lib "eagle-import") (part "res_cap_CAPACITOR-0603"))
    )
    (comp (ref "C90")
      (value "100nF")
      (footprint "eagle-import:0603-CAP")
      (libsource (lib "eagle-import") (part "res_cap_CAPACITOR-0603"))
    )
    (comp (ref "C91")
      (value "100nF")
      (footprint "eagle-import:0603-CAP")
      (libsource (lib "eagle-import") (part "res_cap_CAPACITOR-0603"))
    )
    (comp (ref "CON_USB1")
      (value "MINI-USB-UX60A-MB-5ST")
      (footprint "eagle-import:UX60A-MB-5ST")
      (libsource (lib "eagle-import") (part "MINI-USB-UX60A-MB-5ST"))
    )
    (comp (ref "FT_VREG3V3")
      (value "MIC5219")
      (footprint "eagle-import:SOT23-5")
      (libsource (lib "eagle-import") (part "MIC5219XX"))
    )
    (comp (ref "IC2")
      (value "93C46-SO23-6")
      (footprint "eagle-import:SO23-6")
      (libsource (lib "eagle-import") (part "93C46-SO23-6"))
    )
    (comp (ref "IC3")
      (value "FT2232HQ")
      (footprint "eagle-import:QFN64")
      (libsource (lib "eagle-import") (part "FT2232HQ"))
    )
    (comp (ref "L1")
      (value "INDUCTOR-0603")
      (footprint "eagle-import:0603-IND")
      (libsource (lib "eagle-import") (part "INDUCTOR-0603"))
    )
    (comp (ref "L2")
      (value "INDUCTOR-0603")
      (footprint "eagle-import:0603-IND")
      (libsource (lib "eagle-import") (part "INDUCTOR-0603"))
    )
    (comp (ref "LED_FT")
      (value "LED-0603")
      (footprint "eagle-import:0603-LED")
      (libsource (lib "eagle-import") (part "LED-0603"))
    )
    (comp (ref "LED_JRXD")
      (value "LED-0603")
      (footprint "eagle-import:0603-LED")
      (libsource (lib "eagle-import") (part "LED-0603"))
    )
    (comp (ref "LED_JTXD")
      (value "LED-0603")
      (footprint "eagle-import:0603-LED")
      (libsource (lib "eagle-import") (part "LED-0603"))
    )
    (comp (ref "Q3")
      (value "12Mhz")
      (footprint "eagle-import:ABM8")
      (libsource (lib "eagle-import") (part "ABM8"))
    )
    (comp (ref "R15")
      (value "470R")
      (footprint "eagle-import:0603-RES")
      (libsource (lib "eagle-import") (part "res_cap_RESISTOR-0603"))
    )
    (comp (ref "R24")
      (value "470R")
      (footprint "eagle-import:0603-RES")
      (libsource (lib "eagle-import") (part "res_cap_RESISTOR-0603"))
    )
    (comp (ref "R49")
      (value "0R")
      (footprint "eagle-import:0603-RES")
      (libsource (lib "eagle-import") (part "RESISTOR-0603"))
    )
    (comp (ref "R50")
      (value "0R")
      (footprint "eagle-import:0603-RES")
      (libsource (lib "eagle-import") (part "RESISTOR-0603"))
    )
    (comp (ref "R71")
      (value "470R")
      (footprint "eagle-import:0603-RES")
      (libsource (lib "eagle-import") (part "res_cap_RESISTOR-0603"))
    )
    (comp (ref "R75")
      (value "12k")
      (footprint "eagle-import:0603-RES")
      (libsource (lib "eagle-import") (part "res_cap_RESISTOR-0603"))
    )
    (comp (ref "R76")
      (value "12k")
      (footprint "eagle-import:0603-RES")
      (libsource (lib "eagle-import") (part "res_cap_RESISTOR-0603"))
    )
    (comp (ref "R77")
      (value "10k")
      (footprint "eagle-import:0603-RES")
      (libsource (lib "eagle-import") (part "res_cap_RESISTOR-0603"))
    )
    (comp (ref "R78")
      (value "2k")
      (footprint "eagle-import:0603-RES")
      (libsource (lib "eagle-import") (part "res_cap_RESISTOR-0603"))
    )
    (comp (ref "ADC1")
      (value "ADS1114")
      (footprint "eagle-import:R-PQFP-N10")
      (libsource (lib "eagle-import") (part "ADS1114"))
    )
    (comp (ref "ADC2")
      (value "ADS1114")
      (footprint "eagle-import:R-PQFP-N10")
      (libsource (lib "eagle-import") (part "ADS1114"))
    )
    (comp (ref "BARO_ABS")
      (value "MPX6115")
      (footprint "eagle-import:CASE_1317")
      (libsource (lib "eagle-import") (part "MPX6115"))
    )
    (comp (ref "BARO_DIF")
      (value "MPXV5004DP")
      (footprint "eagle-import:CASE1351")
      (libsource (lib "eagle-import") (part "MPXV5004DP"))
    )
    (comp (ref "C8")
      (value "100nF")
      (footprint "eagle-import:0603-CAP")
      (libsource (lib "eagle-import") (part "CAPACITOR-0603"))
    )
    (comp (ref "C24")
      (value "330nF")
      (footprint "eagle-import:0603-CAP")
      (libsource (lib "eagle-import") (part "CAPACITOR-0603"))
    )
    (comp (ref "C27")
      (value "100nF")
      (footprint "eagle-import:0603-CAP")
      (libsource (lib "eagle-import") (part "CAPACITOR-0603"))
    )
    (comp (ref "C31")
      (value "330nF")
      (footprint "eagle-import:0603-CAP")
      (libsource (lib "eagle-import") (part "CAPACITOR-0603"))
    )
    (comp (ref "C32")
      (value "170nF")
      (footprint "eagle-import:0603-CAP")
      (libsource (lib "eagle-import") (part "CAPACITOR-0603"))
    )
    (comp (ref "C36")
      (value "170nF")
      (footprint "eagle-import:0603-CAP")
      (libsource (lib "eagle-import") (part "CAPACITOR-0603"))
    )
    (comp (ref "C68")
      (value "100nF")
      (footprint "eagle-import:0603-CAP")
      (libsource (lib "eagle-import") (part "CAPACITOR-0603"))
    )
    (comp (ref "C70")
      (value "100nF")
      (footprint "eagle-import:0603-CAP")
      (libsource (lib "eagle-import") (part "CAPACITOR-0603"))
    )
    (comp (ref "C71")
      (value "100nF")
      (footprint "eagle-import:0603-CAP")
      (libsource (lib "eagle-import") (part "CAPACITOR-0603"))
    )
    (comp (ref "R1")
      (value "100k")
      (footprint "eagle-import:0603-RES")
      (libsource (lib "eagle-import") (part "RESISTOR-0603"))
    )
    (comp (ref "R2")
      (value "130k")
      (footprint "eagle-import:0603-RES")
      (libsource (lib "eagle-import") (part "RESISTOR-0603"))
    )
    (comp (ref "R5")
      (value "6.1k")
      (footprint "eagle-import:0603-RES")
      (libsource (lib "eagle-import") (part "RESISTOR-0603"))
    )
    (comp (ref "R6")
      (value "1k")
      (footprint "eagle-import:0603-RES")
      (libsource (lib "eagle-import") (part "RESISTOR-0603"))
    )
    (comp (ref "R10")
      (value "10k")
      (footprint "eagle-import:0603-RES")
      (libsource (lib "eagle-import") (part "RESISTOR-0603"))
    )
    (comp (ref "R11")
      (value "10k")
      (footprint "eagle-import:0603-RES")
      (libsource (lib "eagle-import") (part "RESISTOR-0603"))
    )
    (comp (ref "R12")
      (value "10k")
      (footprint "eagle-import:0603-RES")
      (libsource (lib "eagle-import") (part "RESISTOR-0603"))
    )
    (comp (ref "R18")
      (value "10k")
      (footprint "eagle-import:0603-RES")
      (libsource (lib "eagle-import") (part "RESISTOR-0603"))
    )
    (comp (ref "R19")
      (value "100k")
      (footprint "eagle-import:0603-RES")
      (libsource (lib "eagle-import") (part "RESISTOR-0603"))
    )
    (comp (ref "R20")
      (value "130k")
      (footprint "eagle-import:0603-RES")
      (libsource (lib "eagle-import") (part "RESISTOR-0603"))
    )
    (comp (ref "R21")
      (value "10k")
      (footprint "eagle-import:0603-RES")
      (libsource (lib "eagle-import") (part "RESISTOR-0603"))
    )
    (comp (ref "R22")
      (value "100k")
      (footprint "eagle-import:0603-RES")
      (libsource (lib "eagle-import") (part "res_cap_RESISTOR-0603"))
    )
    (comp (ref "R35")
      (value "136k")
      (footprint "eagle-import:0603-RES")
      (libsource (lib "eagle-import") (part "res_cap_RESISTOR-0603"))
    )
    (comp (ref "R38")
      (value "1.5k")
      (footprint "eagle-import:0603-RES")
      (libsource (lib "eagle-import") (part "RESISTOR-0603"))
    )
    (comp (ref "R39")
      (value "1k")
      (footprint "eagle-import:0603-RES")
      (libsource (lib "eagle-import") (part "RESISTOR-0603"))
    )
    (comp (ref "R40")
      (value "100k")
      (footprint "eagle-import:0603-RES")
      (libsource (lib "eagle-import") (part "RESISTOR-0603"))
    )
    (comp (ref "R47")
      (value "136k")
      (footprint "eagle-import:0603-RES")
      (libsource (lib "eagle-import") (part "RESISTOR-0603"))
    )
    (comp (ref "R53")
      (value "10k")
      (footprint "eagle-import:0603-RES")
      (libsource (lib "eagle-import") (part "RESISTOR-0603"))
    )
    (comp (ref "R54")
      (value "10k")
      (footprint "eagle-import:0603-RES")
      (libsource (lib "eagle-import") (part "RESISTOR-0603"))
    )
    (comp (ref "R63")
      (value "10k")
      (footprint "eagle-import:0603-RES")
      (libsource (lib "eagle-import") (part "RESISTOR-0603"))
    )
    (comp (ref "R64")
      (value "10k/DNP")
      (footprint "eagle-import:0603-RES")
      (libsource (lib "eagle-import") (part "RESISTOR-0603"))
    )
    (comp (ref "R68")
      (value "10k/DNP")
      (footprint "eagle-import:0603-RES")
      (libsource (lib "eagle-import") (part "RESISTOR-0603"))
    )
    (comp (ref "R69")
      (value "0R")
      (footprint "eagle-import:0603-RES")
      (libsource (lib "eagle-import") (part "RESISTOR-0603"))
    )
    (comp (ref "U90")
      (value "AD8554ARU")
      (footprint "eagle-import:TSSOP14")
      (libsource (lib "eagle-import") (part "AD8554ARU"))
    )
    (comp (ref "BAT_IN")
      (value "SOLDER_PAD150_75")
      (footprint "eagle-import:SOLD_PAD_150_75")
      (libsource (lib "eagle-import") (part "SOLDER_PAD150_75"))
    )
    (comp (ref "BAT_IN1")
      (value "SOLDER_PAD150_75")
      (footprint "eagle-import:SOLD_PAD_150_75")
      (libsource (lib "eagle-import") (part "SOLDER_PAD150_75"))
    )
    (comp (ref "C1")
      (value "100uF/20V")
      (footprint "eagle-import:7343_D")
      (libsource (lib "eagle-import") (part "CAPACITOR-POLD"))
    )
    (comp (ref "C2")
      (value "100nF")
      (footprint "eagle-import:0603-CAP")
      (libsource (lib "eagle-import") (part "CAPACITOR-0603"))
    )
    (comp (ref "C3")
      (value "220uF/10V")
      (footprint "eagle-import:7343_D")
      (libsource (lib "eagle-import") (part "CAPACITOR-POLD"))
    )
    (comp (ref "C4")
      (value "100nF")
      (footprint "eagle-import:0603-CAP")
      (libsource (lib "eagle-import") (part "CAPACITOR-0603"))
    )
    (comp (ref "C16")
      (value "2.2uF/Low ESR")
      (footprint "eagle-import:0603-POL-CAP")
      (libsource (lib "eagle-import") (part "CAPACITOR-POL-0603"))
    )
    (comp (ref "C17")
      (value "22uF/10V")
      (footprint "eagle-import:1206-POL-CAP")
      (libsource (lib "eagle-import") (part "CAPACITOR-POL-1206"))
    )
    (comp (ref "C18")
      (value "4.7uF/10V/Low ESR")
      (footprint "eagle-import:0603-POL-CAP")
      (libsource (lib "eagle-import") (part "CAPACITOR-POL-0603"))
    )
    (comp (ref "C19")
      (value "10nF/16V")
      (footprint "eagle-import:0603-CAP")
      (libsource (lib "eagle-import") (part "CAPACITOR-0603"))
    )
    (comp (ref "C20")
      (value "100nF")
      (footprint "eagle-import:0603-CAP")
      (libsource (lib "eagle-import") (part "CAPACITOR-0603"))
    )
    (comp (ref "C21")
      (value "100nF")
      (footprint "eagle-import:0603-CAP")
      (libsource (lib "eagle-import") (part "CAPACITOR-0603"))
    )
    (comp (ref "C22")
      (value "100uF/20V")
      (footprint "eagle-import:7343_D")
      (libsource (lib "eagle-import") (part "CAPACITOR-POLD"))
    )
    (comp (ref "C26")
      (value "4.7uF/10V/Low ESR")
      (footprint "eagle-import:0603-POL-CAP")
      (libsource (lib "eagle-import") (part "CAPACITOR-POL-0603"))
    )
    (comp (ref "C37")
      (value "100nF")
      (footprint "eagle-import:0603-CAP")
      (libsource (lib "eagle-import") (part "res_cap_CAPACITOR-0603"))
    )
    (comp (ref "C38")
      (value "33uF/6V")
      (footprint "eagle-import:1206-POL-CAP")
      (libsource (lib "eagle-import") (part "CAPACITOR-POL-1206"))
    )
    (comp (ref "C39")
      (value "100nF")
      (footprint "eagle-import:0603-CAP")
      (libsource (lib "eagle-import") (part "res_cap_CAPACITOR-0603"))
    )
    (comp (ref "C40")
      (value "33uF/6V")
      (footprint "eagle-import:1206-POL-CAP")
      (libsource (lib "eagle-import") (part "CAPACITOR-POL-1206"))
    )
    (comp (ref "C43")
      (value "100nF")
      (footprint "eagle-import:0603-CAP")
      (libsource (lib "eagle-import") (part "CAPACITOR-0603"))
    )
    (comp (ref "C44")
      (value "220uF/10V")
      (footprint "eagle-import:7343_D")
      (libsource (lib "eagle-import") (part "CAPACITOR-POLD"))
    )
    (comp (ref "C45")
      (value "100nF")
      (footprint "eagle-import:0603-CAP")
      (libsource (lib "eagle-import") (part "CAPACITOR-0603"))
    )
    (comp (ref "C46")
      (value "10uF")
      (footprint "eagle-import:0603-POL-CAP")
      (libsource (lib "eagle-import") (part "CAPACITOR-POL-0603"))
    )
    (comp (ref "C47")
      (value "10uF")
      (footprint "eagle-import:0603-POL-CAP")
      (libsource (lib "eagle-import") (part "CAPACITOR-POL-0603"))
    )
    (comp (ref "C56")
      (value "10nF/16V")
      (footprint "eagle-import:0603-CAP")
      (libsource (lib "eagle-import") (part "CAPACITOR-0603"))
    )
    (comp (ref "C57")
      (value "2.2uF/Low ESR")
      (footprint "eagle-import:0603-POL-CAP")
      (libsource (lib "eagle-import") (part "CAPACITOR-POL-0603"))
    )
    (comp (ref "GND_IN")
      (value "SOLDER_PAD150_75")
      (footprint "eagle-import:SOLD_PAD_150_75")
      (libsource (lib "eagle-import") (part "SOLDER_PAD150_75"))
    )
    (comp (ref "GND_IN1")
      (value "SOLDER_PAD150_75")
      (footprint "eagle-import:SOLD_PAD_150_75")
      (libsource (lib "eagle-import") (part "SOLDER_PAD150_75"))
    )
    (comp (ref "JL2")
      (value "JOBY_LOGO-12MIL")
      (footprint "eagle-import:JOBY_LOGO_12MIL")
      (libsource (lib "eagle-import") (part "JOBY_LOGO-12MIL"))
    )
    (comp (ref "PWS1")
      (value "TPS2051B")
      (footprint "eagle-import:SOT23-5L")
      (libsource (lib "eagle-import") (part "TPS2051B"))
    )
    (comp (ref "PWS2")
      (value "TPS2051B")
      (footprint "eagle-import:SOT23-5L")
      (libsource (lib "eagle-import") (part "TPS2051B"))
    )
    (comp (ref "R3")
      (value "3.9k")
      (footprint "eagle-import:0603-RES")
      (libsource (lib "eagle-import") (part "res_cap_RESISTOR-0603"))
    )
    (comp (ref "R4")
      (value "1k")
      (footprint "eagle-import:0603-RES")
      (libsource (lib "eagle-import") (part "res_cap_RESISTOR-0603"))
    )
    (comp (ref "R14")
      (value "353R")
      (footprint "eagle-import:0603-RES")
      (libsource (lib "eagle-import") (part "res_cap_RESISTOR-0603"))
    )
    (comp (ref "R62")
      (value "1k89")
      (footprint "eagle-import:0603-RES")
      (libsource (lib "eagle-import") (part "RESISTOR-0603"))
    )
    (comp (ref "REG3V3A")
      (value "LP2992")
      (footprint "eagle-import:SOT23-5")
      (libsource (lib "eagle-import") (part "v-reg-micrel_MIC5219BM5"))
    )
    (comp (ref "REG5VA")
      (value "LP2992")
      (footprint "eagle-import:SOT23-5")
      (libsource (lib "eagle-import") (part "v-reg-micrel_MIC5219BM5"))
    )
    (comp (ref "REG6V5A")
      (value "LM317MBDT")
      (footprint "eagle-import:DPACK")
      (libsource (lib "eagle-import") (part "LM317?MBDT"))
    )
    (comp (ref "REG_1V8")
      (value "MIC5247-1.8V")
      (footprint "eagle-import:SOT-23-5")
      (libsource (lib "eagle-import") (part "MIC5219YM5"))
    )
    (comp (ref "REG_3V3D")
      (value "PTHTH")
      (footprint "eagle-import:PTH_TH")
      (libsource (lib "eagle-import") (part "PTHTH"))
    )
    (comp (ref "REG_5VD")
      (value "PTHTH")
      (footprint "eagle-import:PTH_TH")
      (libsource (lib "eagle-import") (part "PTHTH"))
    )
    (comp (ref "~NUDEV~1")
      (value "GND-GNDA")
      (footprint "eagle-import:GND-GNDA")
      (libsource (lib "eagle-import") (part "GND-GNDA"))
    )
    (comp (ref "JL1")
      (value "JOBY_LOGO-12MIL")
      (footprint "eagle-import:JOBY_LOGO_12MIL")
      (libsource (lib "eagle-import") (part "JOBY_LOGO-12MIL"))
    )
  )
  (nets
    (net (code "1") (name "+1V8") (class "Default")
      (node (ref "C46") (pin "+") (pinfunction "+_+") (pintype "passive"))
      (node (ref "C51") (pin "P$1") (pinfunction "1_P$1") (pintype "passive"))
      (node (ref "C60") (pin "P$1") (pinfunction "1_P$1") (pintype "passive"))
      (node (ref "LT_3") (pin "P$19") (pinfunction "VCCA_P$19") (pintype "bidirectional"))
      (node (ref "R65") (pin "P$2") (pinfunction "2_P$2") (pintype "passive"))
      (node (ref "REG_1V8") (pin "5") (pinfunction "VCC_5") (pintype "power_in"))
    )
    (net (code "2") (name "+3V3") (class "Default")
      (node (ref "C10") (pin "P$2") (pinfunction "2_P$2") (pintype "passive"))
      (node (ref "C11") (pin "P$2") (pinfunction "2_P$2") (pintype "passive"))
      (node (ref "C12") (pin "P$2") (pinfunction "2_P$2") (pintype "passive"))
      (node (ref "C23") (pin "P$2") (pinfunction "2_P$2") (pintype "passive"))
      (node (ref "C41") (pin "P$2") (pinfunction "2_P$2") (pintype "passive"))
      (node (ref "C44") (pin "+") (pinfunction "+_+") (pintype "passive"))
      (node (ref "C45") (pin "P$1") (pinfunction "1_P$1") (pintype "passive"))
      (node (ref "C47") (pin "+") (pinfunction "+_+") (pintype "passive"))
      (node (ref "C49") (pin "P$1") (pinfunction "1_P$1") (pintype "passive"))
      (node (ref "C50") (pin "P$1") (pinfunction "1_P$1") (pintype "passive"))
      (node (ref "C52") (pin "+") (pinfunction "+_+") (pintype "passive"))
      (node (ref "C59") (pin "P$1") (pinfunction "1_P$1") (pintype "passive"))
      (node (ref "C67") (pin "P$2") (pinfunction "2_P$2") (pintype "passive"))
      (node (ref "CON_I2C2") (pin "3") (pinfunction "3_3") (pintype "bidirectional"))
      (node (ref "CON_I2C_IMU") (pin "4") (pinfunction "4_4") (pintype "bidirectional"))
      (node (ref "CON_OV_SPI") (pin "3") (pinfunction "3_3") (pintype "bidirectional"))
      (node (ref "CON_SPARE") (pin "2") (pinfunction "2_2") (pintype "bidirectional"))
      (node (ref "CON_USART1") (pin "3") (pinfunction "3_3") (pintype "bidirectional"))
      (node (ref "CON_USART2") (pin "3") (pinfunction "3_3") (pintype "bidirectional"))
      (node (ref "CON_USART3") (pin "3") (pinfunction "3_3") (pintype "bidirectional"))
      (node (ref "IC1") (pin "16") (pinfunction "VDD_16") (pintype "bidirectional"))
      (node (ref "IC1") (pin "4") (pinfunction "LE_4") (pintype "bidirectional"))
      (node (ref "IC4") (pin "12") (pinfunction "FORCEON_12") (pintype "input"))
      (node (ref "IC4") (pin "15") (pinfunction "VCC_15") (pintype "power_in"))
      (node (ref "IC4") (pin "16") (pinfunction "~{FORCEOFF}_16") (pintype "input"))
      (node (ref "IC6") (pin "12") (pinfunction "FORCEON_12") (pintype "input"))
      (node (ref "IC6") (pin "15") (pinfunction "VCC_15") (pintype "power_in"))
      (node (ref "IC6") (pin "16") (pinfunction "~{FORCEOFF}_16") (pintype "input"))
      (node (ref "J3&4") (pin "VSYSTEM@1") (pinfunction "VSYSTEM_VSYSTEM@1") (pintype "bidirectional"))
      (node (ref "J3&4") (pin "VSYSTEM@2") (pinfunction "VSYSTEM_VSYSTEM@2") (pintype "bidirectional"))
      (node (ref "J3&4") (pin "VSYSTEM@66") (pinfunction "VSYSTEM_VSYSTEM@66") (pintype "bidirectional"))
      (node (ref "J3&4") (pin "VSYSTEM@67") (pinfunction "VSYSTEM_VSYSTEM@67") (pintype "bidirectional"))
      (node (ref "L3") (pin "P$1") (pinfunction "1_P$1") (pintype "passive"))
      (node (ref "LED_1") (pin "1") (pinfunction "P$1_1") (pintype "bidirectional"))
      (node (ref "LED_1") (pin "4") (pinfunction "P$4_4") (pintype "bidirectional"))
      (node (ref "LED_2") (pin "1") (pinfunction "P$1_1") (pintype "bidirectional"))
      (node (ref "LED_2") (pin "4") (pinfunction "P$4_4") (pintype "bidirectional"))
      (node (ref "LED_3") (pin "1") (pinfunction "P$1_1") (pintype "bidirectional"))
      (node (ref "LED_3") (pin "4") (pinfunction "P$4_4") (pintype "bidirectional"))
      (node (ref "LED_4") (pin "1") (pinfunction "P$1_1") (pintype "bidirectional"))
      (node (ref "LED_4") (pin "4") (pinfunction "P$4_4") (pintype "bidirectional"))
      (node (ref "LT1") (pin "7") (pinfunction "VCCB_7") (pintype "bidirectional"))
      (node (ref "LT_3") (pin "P$18") (pinfunction "VCCY_P$18") (pintype "bidirectional"))
      (node (ref "LT_3") (pin "P$8") (pinfunction "EN_P$8") (pintype "bidirectional"))
      (node (ref "LT_I2C1") (pin "2") (pinfunction "VREF1_2") (pintype "bidirectional"))
      (node (ref "LT_I2C2") (pin "2") (pinfunction "VREF1_2") (pintype "bidirectional"))
      (node (ref "MCU") (pin "1") (pinfunction "VBAT_1") (pintype "power_in"))
      (node (ref "MCU") (pin "19") (pinfunction "VDD4_19") (pintype "bidirectional"))
      (node (ref "MCU") (pin "32") (pinfunction "VDD1_32") (pintype "power_in"))
      (node (ref "MCU") (pin "48") (pinfunction "VDD2_48") (pintype "power_in"))
      (node (ref "MCU") (pin "64") (pinfunction "VDD3_64") (pintype "power_in"))
      (node (ref "Q7") (pin "4") (pinfunction "VDD_4") (pintype "power_in"))
      (node (ref "R28") (pin "P$1") (pinfunction "1_P$1") (pintype "passive"))
      (node (ref "R29") (pin "P$1") (pinfunction "1_P$1") (pintype "passive"))
      (node (ref "R33") (pin "P$2") (pinfunction "2_P$2") (pintype "passive"))
      (node (ref "R34") (pin "P$2") (pinfunction "2_P$2") (pintype "passive"))
      (node (ref "R7") (pin "P$2") (pinfunction "2_P$2") (pintype "passive"))
      (node (ref "REG_1V8") (pin "1") (pinfunction "V_IN_1") (pintype "input"))
      (node (ref "REG_3V3D") (pin "P$3") (pinfunction "VOUT_P$3") (pintype "bidirectional"))
    )
    (net (code "3") (name "+3V3A") (class "Default")
      (node (ref "ADC1") (pin "P$1") (pinfunction "ADDR_P$1") (pintype "bidirectional"))
      (node (ref "ADC1") (pin "P$8") (pinfunction "VDD_P$8") (pintype "bidirectional"))
      (node (ref "ADC2") (pin "P$8") (pinfunction "VDD_P$8") (pintype "bidirectional"))
      (node (ref "C18") (pin "+") (pinfunction "+_+") (pintype "passive"))
      (node (ref "C70") (pin "P$1") (pinfunction "1_P$1") (pintype "passive"))
      (node (ref "C71") (pin "P$1") (pinfunction "1_P$1") (pintype "passive"))
      (node (ref "R12") (pin "P$1") (pinfunction "1_P$1") (pintype "passive"))
      (node (ref "R54") (pin "P$1") (pinfunction "1_P$1") (pintype "passive"))
      (node (ref "R64") (pin "P$2") (pinfunction "2_P$2") (pintype "passive"))
      (node (ref "REG3V3A") (pin "5") (pinfunction "OUT_5") (pintype "output"))
    )
    (net (code "4") (name "+5V") (class "Default")
      (node (ref "C13") (pin "P$2") (pinfunction "2_P$2") (pintype "passive"))
      (node (ref "C14") (pin "P$2") (pinfunction "2_P$2") (pintype "passive"))
      (node (ref "C25") (pin "P$2") (pinfunction "2_P$2") (pintype "passive"))
      (node (ref "C28") (pin "P$2") (pinfunction "2_P$2") (pintype "passive"))
      (node (ref "C29") (pin "P$1") (pinfunction "1_P$1") (pintype "passive"))
      (node (ref "C3") (pin "+") (pinfunction "+_+") (pintype "passive"))
      (node (ref "C30") (pin "P$2") (pinfunction "2_P$2") (pintype "passive"))
      (node (ref "C4") (pin "P$1") (pinfunction "1_P$1") (pintype "passive"))
      (node (ref "C69") (pin "P$2") (pinfunction "2_P$2") (pintype "passive"))
      (node (ref "CON_I2C2") (pin "2") (pinfunction "2_2") (pintype "bidirectional"))
      (node (ref "CON_I2C2") (pin "4") (pinfunction "4_4") (pintype "bidirectional"))
      (node (ref "CON_LIGHTS") (pin "6") (pinfunction "6_6") (pintype "bidirectional"))
      (node (ref "CON_MC1") (pin "4") (pinfunction "4_4") (pintype "bidirectional"))
      (node (ref "CON_MC2") (pin "4") (pinfunction "4_4") (pintype "bidirectional"))
      (node (ref "CON_OV_SPI") (pin "2") (pinfunction "2_2") (pintype "bidirectional"))
      (node (ref "CON_OV_UART1") (pin "2") (pinfunction "2_2") (pintype "bidirectional"))
      (node (ref "CON_OV_USBH") (pin "2") (pinfunction "2_2") (pintype "bidirectional"))
      (node (ref "CON_SERVOS_1") (pin "2") (pinfunction "2_2") (pintype "bidirectional"))
      (node (ref "CON_SERVOS_1") (pin "5") (pinfunction "5_5") (pintype "bidirectional"))
      (node (ref "CON_SERVOS_1") (pin "8") (pinfunction "8_8") (pintype "bidirectional"))
      (node (ref "CON_SERVOS_2") (pin "2") (pinfunction "2_2") (pintype "bidirectional"))
      (node (ref "CON_SERVOS_2") (pin "5") (pinfunction "5_5") (pintype "bidirectional"))
      (node (ref "CON_SERVOS_2") (pin "8") (pinfunction "8_8") (pintype "bidirectional"))
      (node (ref "CON_USART1") (pin "2") (pinfunction "2_2") (pintype "bidirectional"))
      (node (ref "CON_USART2") (pin "2") (pinfunction "2_2") (pintype "bidirectional"))
      (node (ref "CON_USART3") (pin "2") (pinfunction "2_2") (pintype "bidirectional"))
      (node (ref "PWS1") (pin "5") (pinfunction "IN_5") (pintype "bidirectional"))
      (node (ref "PWS2") (pin "5") (pinfunction "IN_5") (pintype "bidirectional"))
      (node (ref "R25") (pin "P$2") (pinfunction "2_P$2") (pintype "passive"))
      (node (ref "R30") (pin "P$1") (pinfunction "1_P$1") (pintype "passive"))
      (node (ref "R43") (pin "P$2") (pinfunction "2_P$2") (pintype "passive"))
      (node (ref "R44") (pin "P$2") (pinfunction "2_P$2") (pintype "passive"))
      (node (ref "R45") (pin "P$1") (pinfunction "1_P$1") (pintype "passive"))
      (node (ref "R46") (pin "P$1") (pinfunction "1_P$1") (pintype "passive"))
      (node (ref "R56") (pin "P$2") (pinfunction "2_P$2") (pintype "passive"))
      (node (ref "R60") (pin "P$1") (pinfunction "1_P$1") (pintype "passive"))
      (node (ref "R70") (pin "P$1") (pinfunction "1_P$1") (pintype "passive"))
      (node (ref "REG_5VD") (pin "P$3") (pinfunction "VOUT_P$3") (pintype "bidirectional"))
      (node (ref "U1") (pin "3") (pinfunction "VDD_3") (pintype "power_in"))
    )
    (net (code "5") (name "+5VA") (class "Default")
      (node (ref "BARO_ABS") (pin "P$2") (pinfunction "VS_P$2") (pintype "bidirectional"))
      (node (ref "BARO_DIF") (pin "P$2") (pinfunction "VS_P$2") (pintype "bidirectional"))
      (node (ref "C26") (pin "+") (pinfunction "+_+") (pintype "passive"))
      (node (ref "C27") (pin "P$1") (pinfunction "1_P$1") (pintype "passive"))
      (node (ref "C68") (pin "P$1") (pinfunction "1_P$1") (pintype "passive"))
      (node (ref "C8") (pin "P$1") (pinfunction "1_P$1") (pintype "passive"))
      (node (ref "R38") (pin "P$1") (pinfunction "1_P$1") (pintype "passive"))
      (node (ref "R5") (pin "P$1") (pinfunction "1_P$1") (pintype "passive"))
      (node (ref "REG5VA") (pin "5") (pinfunction "OUT_5") (pintype "output"))
      (node (ref "U90") (pin "4") (pinfunction "V+_4") (pintype "power_in"))
    )
    (net (code "6") (name "+6V5") (class "Default")
      (node (ref "C16") (pin "+") (pinfunction "+_+") (pintype "passive"))
      (node (ref "C17") (pin "+") (pinfunction "+_+") (pintype "passive"))
      (node (ref "C20") (pin "P$1") (pinfunction "1_P$1") (pintype "passive"))
      (node (ref "C57") (pin "+") (pinfunction "+_+") (pintype "passive"))
      (node (ref "CON_SPI_IMU") (pin "3") (pinfunction "3_3") (pintype "bidirectional"))
      (node (ref "R4") (pin "P$2") (pinfunction "2_P$2") (pintype "passive"))
      (node (ref "REG3V3A") (pin "1") (pinfunction "IN_1") (pintype "input"))
      (node (ref "REG3V3A") (pin "3") (pinfunction "EN_3") (pintype "input"))
      (node (ref "REG5VA") (pin "1") (pinfunction "IN_1") (pintype "input"))
      (node (ref "REG5VA") (pin "3") (pinfunction "EN_3") (pintype "input"))
      (node (ref "REG6V5A") (pin "4") (pinfunction "OUT_4") (pintype "passive"))
      (node (ref "U$1") (pin "P$1") (pinfunction "P$1_P$1") (pintype "bidirectional"))
    )
    (net (code "7") (name "+12V") (class "Default")
      (node (ref "BAT_IN") (pin "P$1") (pinfunction "P$1_P$1") (pintype "bidirectional"))
      (node (ref "BAT_IN1") (pin "P$1") (pinfunction "P$1_P$1") (pintype "bidirectional"))
      (node (ref "C1") (pin "+") (pinfunction "+_+") (pintype "passive"))
      (node (ref "C2") (pin "P$1") (pinfunction "1_P$1") (pintype "passive"))
      (node (ref "C21") (pin "P$1") (pinfunction "1_P$1") (pintype "passive"))
      (node (ref "C22") (pin "+") (pinfunction "+_+") (pintype "passive"))
      (node (ref "C43") (pin "P$1") (pinfunction "1_P$1") (pintype "passive"))
      (node (ref "R16") (pin "P$2") (pinfunction "2_P$2") (pintype "passive"))
      (node (ref "REG6V5A") (pin "3") (pinfunction "IN_3") (pintype "input"))
      (node (ref "REG_3V3D") (pin "P$1") (pinfunction "VIN_P$1") (pintype "bidirectional"))
      (node (ref "REG_5VD") (pin "P$1") (pinfunction "VIN_P$1") (pintype "bidirectional"))
    )
    (net (code "8") (name "ADCIN2") (class "Default")
      (node (ref "J3&4") (pin "ADCIN2") (pinfunction "ADCIN2_ADCIN2") (pintype "bidirectional"))
    )
    (net (code "9") (name "ADCIN3") (class "Default")
      (node (ref "J3&4") (pin "ADCIN3") (pinfunction "ADCIN3_ADCIN3") (pintype "bidirectional"))
    )
    (net (code "10") (name "ADCIN4") (class "Default")
      (node (ref "J3&4") (pin "ADCIN4") (pinfunction "ADCIN4_ADCIN4") (pintype "bidirectional"))
    )
    (net (code "11") (name "ADCIN5") (class "Default")
      (node (ref "J3&4") (pin "ADCIN5") (pinfunction "ADCIN5_ADCIN5") (pintype "bidirectional"))
    )
    (net (code "12") (name "ADCIN6") (class "Default")
      (node (ref "J3&4") (pin "ADCIN6") (pinfunction "ADCIN6_ADCIN6") (pintype "bidirectional"))
    )
    (net (code "13") (name "ADCIN7") (class "Default")
      (node (ref "J3&4") (pin "ADCIN7") (pinfunction "ADCIN7_ADCIN7") (pintype "bidirectional"))
    )
    (net (code "14") (name "BARO_1_DRDY") (class "Default")
      (node (ref "ADC1") (pin "P$2") (pinfunction "DRDY_P$2") (pintype "bidirectional"))
      (node (ref "MCU") (pin "8") (pinfunction "PC0-ADC10_8") (pintype "bidirectional"))
    )
    (net (code "15") (name "BARO_2_DRDY") (class "Default")
      (node (ref "ADC2") (pin "P$2") (pinfunction "DRDY_P$2") (pintype "bidirectional"))
      (node (ref "MCU") (pin "6") (pinfunction "PD1-OSC_OUT_6") (pintype "output"))
    )
    (net (code "16") (name "CAN_H") (class "Default")
      (node (ref "CON_MC1") (pin "3") (pinfunction "3_3") (pintype "bidirectional"))
      (node (ref "CON_MC2") (pin "3") (pinfunction "3_3") (pintype "bidirectional"))
      (node (ref "R57") (pin "P$1") (pinfunction "1_P$1") (pintype "passive"))
      (node (ref "R58") (pin "P$1") (pinfunction "1_P$1") (pintype "passive"))
      (node (ref "U1") (pin "7") (pinfunction "CANH_7") (pintype "bidirectional"))
    )
    (net (code "17") (name "CAN_L") (class "Default")
      (node (ref "CON_MC1") (pin "2") (pinfunction "2_2") (pintype "bidirectional"))
      (node (ref "CON_MC2") (pin "2") (pinfunction "2_2") (pintype "bidirectional"))
      (node (ref "R57") (pin "P$2") (pinfunction "2_P$2") (pintype "passive"))
      (node (ref "R59") (pin "P$2") (pinfunction "2_P$2") (pintype "passive"))
      (node (ref "U1") (pin "6") (pinfunction "CANL_6") (pintype "bidirectional"))
    )
    (net (code "18") (name "FT_1V8") (class "Default")
      (node (ref "C79") (pin "+") (pinfunction "+_+") (pintype "passive"))
      (node (ref "C80") (pin "P$2") (pinfunction "2_P$2") (pintype "passive"))
      (node (ref "C85") (pin "P$2") (pinfunction "2_P$2") (pintype "passive"))
      (node (ref "C86") (pin "P$2") (pinfunction "2_P$2") (pintype "passive"))
      (node (ref "C87") (pin "P$2") (pinfunction "2_P$2") (pintype "passive"))
      (node (ref "IC3") (pin "P$12") (pinfunction "VCORE1_P$12") (pintype "bidirectional"))
      (node (ref "IC3") (pin "P$37") (pinfunction "VCORE2_P$37") (pintype "bidirectional"))
      (node (ref "IC3") (pin "P$49") (pinfunction "VREGOUT_P$49") (pintype "bidirectional"))
      (node (ref "IC3") (pin "P$64") (pinfunction "VCORE3_P$64") (pintype "bidirectional"))
    )
    (net (code "19") (name "FT_3V3") (class "Default")
      (node (ref "C75") (pin "+") (pinfunction "+_+") (pintype "passive"))
      (node (ref "C78") (pin "P$2") (pinfunction "2_P$2") (pintype "passive"))
      (node (ref "C88") (pin "P$2") (pinfunction "2_P$2") (pintype "passive"))
      (node (ref "C89") (pin "P$2") (pinfunction "2_P$2") (pintype "passive"))
      (node (ref "C90") (pin "P$2") (pinfunction "2_P$2") (pintype "passive"))
      (node (ref "C91") (pin "P$2") (pinfunction "2_P$2") (pintype "passive"))
      (node (ref "FT_VREG3V3") (pin "5") (pinfunction "OUT_5") (pintype "output"))
      (node (ref "IC2") (pin "6") (pinfunction "VCC_6") (pintype "bidirectional"))
      (node (ref "IC3") (pin "P$20") (pinfunction "VCCIO1_P$20") (pintype "bidirectional"))
      (node (ref "IC3") (pin "P$31") (pinfunction "VCCIO2_P$31") (pintype "bidirectional"))
      (node (ref "IC3") (pin "P$42") (pinfunction "VCCIO3_P$42") (pintype "bidirectional"))
      (node (ref "IC3") (pin "P$50") (pinfunction "VREGIN_P$50") (pintype "bidirectional"))
      (node (ref "IC3") (pin "P$56") (pinfunction "VCCIO4_P$56") (pintype "bidirectional"))
      (node (ref "L1") (pin "P$1") (pinfunction "1_P$1") (pintype "passive"))
      (node (ref "L2") (pin "P$1") (pinfunction "1_P$1") (pintype "passive"))
      (node (ref "R15") (pin "P$2") (pinfunction "2_P$2") (pintype "passive"))
      (node (ref "R76") (pin "P$1") (pinfunction "1_P$1") (pintype "passive"))
      (node (ref "R77") (pin "P$2") (pinfunction "2_P$2") (pintype "passive"))
    )
    (net (code "20") (name "FT_5V") (class "Default")
      (node (ref "C76") (pin "+") (pinfunction "+_+") (pintype "passive"))
      (node (ref "C77") (pin "P$2") (pinfunction "2_P$2") (pintype "passive"))
      (node (ref "CON_USB1") (pin "1") (pinfunction "1_1") (pintype "input"))
      (node (ref "FT_VREG3V3") (pin "1") (pinfunction "IN_1") (pintype "input"))
      (node (ref "FT_VREG3V3") (pin "3") (pinfunction "EN_3") (pintype "input"))
    )
    (net (code "21") (name "FT_USB_DM") (class "Default")
      (node (ref "CON_USB1") (pin "2") (pinfunction "2_2") (pintype "input"))
      (node (ref "IC3") (pin "P$7") (pinfunction "DM_P$7") (pintype "bidirectional"))
    )
    (net (code "22") (name "FT_USB_DP") (class "Default")
      (node (ref "CON_USB1") (pin "3") (pinfunction "3_3") (pintype "input"))
      (node (ref "IC3") (pin "P$8") (pinfunction "DP_P$8") (pintype "bidirectional"))
    )
    (net (code "23") (name "GND") (class "Default")
      (node (ref "C1") (pin "-") (pinfunction "-_-") (pintype "passive"))
      (node (ref "C10") (pin "P$1") (pinfunction "1_P$1") (pintype "passive"))
      (node (ref "C11") (pin "P$1") (pinfunction "1_P$1") (pintype "passive"))
      (node (ref "C12") (pin "P$1") (pinfunction "1_P$1") (pintype "passive"))
      (node (ref "C13") (pin "P$1") (pinfunction "1_P$1") (pintype "passive"))
      (node (ref "C14") (pin "P$1") (pinfunction "1_P$1") (pintype "passive"))
      (node (ref "C15") (pin "-") (pinfunction "-_-") (pintype "passive"))
      (node (ref "C16") (pin "-") (pinfunction "-_-") (pintype "passive"))
      (node (ref "C17") (pin "-") (pinfunction "-_-") (pintype "passive"))
      (node (ref "C19") (pin "P$2") (pinfunction "2_P$2") (pintype "passive"))
      (node (ref "C2") (pin "P$2") (pinfunction "2_P$2") (pintype "passive"))
      (node (ref "C20") (pin "P$2") (pinfunction "2_P$2") (pintype "passive"))
      (node (ref "C21") (pin "P$2") (pinfunction "2_P$2") (pintype "passive"))
      (node (ref "C22") (pin "-") (pinfunction "-_-") (pintype "passive"))
      (node (ref "C23") (pin "P$1") (pinfunction "1_P$1") (pintype "passive"))
      (node (ref "C25") (pin "P$1") (pinfunction "1_P$1") (pintype "passive"))
      (node (ref "C28") (pin "P$1") (pinfunction "1_P$1") (pintype "passive"))
      (node (ref "C29") (pin "P$2") (pinfunction "2_P$2") (pintype "passive"))
      (node (ref "C3") (pin "-") (pinfunction "-_-") (pintype "passive"))
      (node (ref "C30") (pin "P$1") (pinfunction "1_P$1") (pintype "passive"))
      (node (ref "C33") (pin "P$2") (pinfunction "2_P$2") (pintype "passive"))
      (node (ref "C34") (pin "P$2") (pinfunction "2_P$2") (pintype "passive"))
      (node (ref "C37") (pin "P$2") (pinfunction "2_P$2") (pintype "passive"))
      (node (ref "C38") (pin "-") (pinfunction "-_-") (pintype "passive"))
      (node (ref "C39") (pin "P$2") (pinfunction "2_P$2") (pintype "passive"))
      (node (ref "C4") (pin "P$2") (pinfunction "2_P$2") (pintype "passive"))
      (node (ref "C40") (pin "-") (pinfunction "-_-") (pintype "passive"))
      (node (ref "C41") (pin "P$1") (pinfunction "1_P$1") (pintype "passive"))
      (node (ref "C42") (pin "P$1") (pinfunction "1_P$1") (pintype "passive"))
      (node (ref "C43") (pin "P$2") (pinfunction "2_P$2") (pintype "passive"))
      (node (ref "C44") (pin "-") (pinfunction "-_-") (pintype "passive"))
      (node (ref "C45") (pin "P$2") (pinfunction "2_P$2") (pintype "passive"))
      (node (ref "C46") (pin "-") (pinfunction "-_-") (pintype "passive"))
      (node (ref "C47") (pin "-") (pinfunction "-_-") (pintype "passive"))
      (node (ref "C48") (pin "P$1") (pinfunction "1_P$1") (pintype "passive"))
      (node (ref "C49") (pin "P$2") (pinfunction "2_P$2") (pintype "passive"))
      (node (ref "C50") (pin "P$2") (pinfunction "2_P$2") (pintype "passive"))
      (node (ref "C51") (pin "P$2") (pinfunction "2_P$2") (pintype "passive"))
      (node (ref "C52") (pin "-") (pinfunction "-_-") (pintype "passive"))
      (node (ref "C56") (pin "P$2") (pinfunction "2_P$2") (pintype "passive"))
      (node (ref "C57") (pin "-") (pinfunction "-_-") (pintype "passive"))
      (node (ref "C59") (pin "P$2") (pinfunction "2_P$2") (pintype "passive"))
      (node (ref "C6") (pin "P$1") (pinfunction "1_P$1") (pintype "passive"))
      (node (ref "C60") (pin "P$2") (pinfunction "2_P$2") (pintype "passive"))
      (node (ref "C61") (pin "P$2") (pinfunction "2_P$2") (pintype "passive"))
      (node (ref "C62") (pin "-") (pinfunction "-_-") (pintype "passive"))
      (node (ref "C65") (pin "P$2") (pinfunction "2_P$2") (pintype "passive"))
      (node (ref "C66") (pin "P$2") (pinfunction "2_P$2") (pintype "passive"))
      (node (ref "C67") (pin "P$1") (pinfunction "1_P$1") (pintype "passive"))
      (node (ref "C69") (pin "P$1") (pinfunction "1_P$1") (pintype "passive"))
      (node (ref "C7") (pin "P$1") (pinfunction "1_P$1") (pintype "passive"))
      (node (ref "C72") (pin "P$1") (pinfunction "1_P$1") (pintype "passive"))
      (node (ref "C73") (pin "P$1") (pinfunction "1_P$1") (pintype "passive"))
      (node (ref "C74") (pin "P$1") (pinfunction "1_P$1") (pintype "passive"))
      (node (ref "C75") (pin "-") (pinfunction "-_-") (pintype "passive"))
      (node (ref "C76") (pin "-") (pinfunction "-_-") (pintype "passive"))
      (node (ref "C77") (pin "P$1") (pinfunction "1_P$1") (pintype "passive"))
      (node (ref "C78") (pin "P$1") (pinfunction "1_P$1") (pintype "passive"))
      (node (ref "C79") (pin "-") (pinfunction "-_-") (pintype "passive"))
      (node (ref "C80") (pin "P$1") (pinfunction "1_P$1") (pintype "passive"))
      (node (ref "C81") (pin "-") (pinfunction "-_-") (pintype "passive"))
      (node (ref "C82") (pin "-") (pinfunction "-_-") (pintype "passive"))
      (node (ref "C83") (pin "P$2") (pinfunction "2_P$2") (pintype "passive"))
      (node (ref "C84") (pin "P$2") (pinfunction "2_P$2") (pintype "passive"))
      (node (ref "C85") (pin "P$1") (pinfunction "1_P$1") (pintype "passive"))
      (node (ref "C86") (pin "P$1") (pinfunction "1_P$1") (pintype "passive"))
      (node (ref "C87") (pin "P$1") (pinfunction "1_P$1") (pintype "passive"))
      (node (ref "C88") (pin "P$1") (pinfunction "1_P$1") (pintype "passive"))
      (node (ref "C89") (pin "P$1") (pinfunction "1_P$1") (pintype "passive"))
      (node (ref "C9") (pin "P$1") (pinfunction "1_P$1") (pintype "passive"))
      (node (ref "C90") (pin "P$1") (pinfunction "1_P$1") (pintype "passive"))
      (node (ref "C91") (pin "P$1") (pinfunction "1_P$1") (pintype "passive"))
      (node (ref "CON_I2C2") (pin "1") (pinfunction "1_1") (pintype "bidirectional"))
      (node (ref "CON_I2C_IMU") (pin "1") (pinfunction "1_1") (pintype "bidirectional"))
      (node (ref "CON_LIGHTS") (pin "1") (pinfunction "1_1") (pintype "bidirectional"))
      (node (ref "CON_LIGHTS") (pin "3") (pinfunction "3_3") (pintype "bidirectional"))
      (node (ref "CON_LIGHTS") (pin "5") (pinfunction "5_5") (pintype "bidirectional"))
      (node (ref "CON_MC1") (pin "1") (pinfunction "1_1") (pintype "bidirectional"))
      (node (ref "CON_MC2") (pin "1") (pinfunction "1_1") (pintype "bidirectional"))
      (node (ref "CON_OV_SPI") (pin "1") (pinfunction "1_1") (pintype "bidirectional"))
      (node (ref "CON_OV_UART1") (pin "1") (pinfunction "1_1") (pintype "bidirectional"))
      (node (ref "CON_OV_USBH") (pin "1") (pinfunction "1_1") (pintype "bidirectional"))
      (node (ref "CON_SERVOS_1") (pin "1") (pinfunction "1_1") (pintype "bidirectional"))
      (node (ref "CON_SERVOS_1") (pin "4") (pinfunction "4_4") (pintype "bidirectional"))
      (node (ref "CON_SERVOS_1") (pin "7") (pinfunction "7_7") (pintype "bidirectional"))
      (node (ref "CON_SERVOS_2") (pin "1") (pinfunction "1_1") (pintype "bidirectional"))
      (node (ref "CON_SERVOS_2") (pin "4") (pinfunction "4_4") (pintype "bidirectional"))
      (node (ref "CON_SERVOS_2") (pin "7") (pinfunction "7_7") (pintype "bidirectional"))
      (node (ref "CON_SPARE") (pin "1") (pinfunction "1_1") (pintype "bidirectional"))
      (node (ref "CON_SPI_IMU") (pin "1") (pinfunction "1_1") (pintype "bidirectional"))
      (node (ref "CON_SPI_IMU") (pin "2") (pinfunction "2_2") (pintype "bidirectional"))
      (node (ref "CON_USART1") (pin "1") (pinfunction "1_1") (pintype "bidirectional"))
      (node (ref "CON_USART2") (pin "1") (pinfunction "1_1") (pintype "bidirectional"))
      (node (ref "CON_USART3") (pin "1") (pinfunction "1_1") (pintype "bidirectional"))
      (node (ref "CON_USB1") (pin "5") (pinfunction "5_5") (pintype "input"))
      (node (ref "FT_VREG3V3") (pin "2") (pinfunction "GND_2") (pintype "power_in"))
      (node (ref "GND_IN") (pin "P$1") (pinfunction "P$1_P$1") (pintype "bidirectional"))
      (node (ref "GND_IN1") (pin "P$1") (pinfunction "P$1_P$1") (pintype "bidirectional"))
      (node (ref "IC1") (pin "1") (pinfunction "GND_1") (pintype "bidirectional"))
      (node (ref "IC1") (pin "13") (pinfunction "~{OE}_13") (pintype "bidirectional"))
      (node (ref "IC2") (pin "2") (pinfunction "VSS_2") (pintype "bidirectional"))
      (node (ref "IC3") (pin "P$1") (pinfunction "GND1_P$1") (pintype "bidirectional"))
      (node (ref "IC3") (pin "P$10") (pinfunction "AGND_P$10") (pintype "bidirectional"))
      (node (ref "IC3") (pin "P$11") (pinfunction "GND3_P$11") (pintype "bidirectional"))
      (node (ref "IC3") (pin "P$13") (pinfunction "TEST_P$13") (pintype "bidirectional"))
      (node (ref "IC3") (pin "P$15") (pinfunction "GND4_P$15") (pintype "bidirectional"))
      (node (ref "IC3") (pin "P$25") (pinfunction "GND5_P$25") (pintype "bidirectional"))
      (node (ref "IC3") (pin "P$35") (pinfunction "GND6_P$35") (pintype "bidirectional"))
      (node (ref "IC3") (pin "P$47") (pinfunction "GND7_P$47") (pintype "bidirectional"))
      (node (ref "IC3") (pin "P$5") (pinfunction "GND2_P$5") (pintype "bidirectional"))
      (node (ref "IC3") (pin "P$51") (pinfunction "GND8_P$51") (pintype "bidirectional"))
      (node (ref "IC3") (pin "P$65") (pinfunction "CENTER_PAD_P$65") (pintype "bidirectional"))
      (node (ref "IC4") (pin "1") (pinfunction "~{EN}_1") (pintype "input"))
      (node (ref "IC4") (pin "14") (pinfunction "GND_14") (pintype "power_in"))
      (node (ref "IC6") (pin "1") (pinfunction "~{EN}_1") (pintype "input"))
      (node (ref "IC6") (pin "14") (pinfunction "GND_14") (pintype "power_in"))
      (node (ref "J3&4") (pin "AGND") (pinfunction "AGND_AGND") (pintype "bidirectional"))
      (node (ref "J3&4") (pin "GND") (pinfunction "GND_GND") (pintype "bidirectional"))
      (node (ref "J3&4") (pin "GND@33") (pinfunction "GND_GND@33") (pintype "bidirectional"))
      (node (ref "J3&4") (pin "GND@56") (pinfunction "GND_GND@56") (pintype "bidirectional"))
      (node (ref "J3&4") (pin "GND@70") (pinfunction "GND_GND@70") (pintype "bidirectional"))
      (node (ref "LED_FT") (pin "C") (pinfunction "C_C") (pintype "passive"))
      (node (ref "LED_JRXD") (pin "C") (pinfunction "C_C") (pintype "passive"))
      (node (ref "LED_JTXD") (pin "C") (pinfunction "C_C") (pintype "passive"))
      (node (ref "LT1") (pin "2") (pinfunction "GND_2") (pintype "bidirectional"))
      (node (ref "LT_3") (pin "P$21") (pinfunction "PAD_P$21") (pintype "bidirectional"))
      (node (ref "LT_3") (pin "P$9") (pinfunction "GND_P$9") (pintype "bidirectional"))
      (node (ref "LT_I2C1") (pin "1") (pinfunction "GND_1") (pintype "bidirectional"))
      (node (ref "LT_I2C2") (pin "1") (pinfunction "GND_1") (pintype "bidirectional"))
      (node (ref "MCU") (pin "12") (pinfunction "VSSA_12") (pintype "power_in"))
      (node (ref "MCU") (pin "18") (pinfunction "VSS4_18") (pintype "bidirectional"))
      (node (ref "MCU") (pin "31") (pinfunction "VSS1_31") (pintype "power_in"))
      (node (ref "MCU") (pin "47") (pinfunction "VSS2_47") (pintype "power_in"))
      (node (ref "MCU") (pin "63") (pinfunction "VSS3_63") (pintype "power_in"))
      (node (ref "PWS1") (pin "2") (pinfunction "GND_2") (pintype "bidirectional"))
      (node (ref "PWS2") (pin "2") (pinfunction "GND_2") (pintype "bidirectional"))
      (node (ref "Q3") (pin "P$2") (pinfunction "P$2_P$2") (pintype "bidirectional"))
      (node (ref "Q3") (pin "P$4") (pinfunction "P$4_P$4") (pintype "bidirectional"))
      (node (ref "Q7") (pin "2") (pinfunction "GND_2") (pintype "power_in"))
      (node (ref "R13") (pin "P$1") (pinfunction "1_P$1") (pintype "passive"))
      (node (ref "R14") (pin "P$1") (pinfunction "1_P$1") (pintype "passive"))
      (node (ref "R17") (pin "P$1") (pinfunction "1_P$1") (pintype "passive"))
      (node (ref "R23") (pin "P$1") (pinfunction "1_P$1") (pintype "passive"))
      (node (ref "R3") (pin "P$1") (pinfunction "1_P$1") (pintype "passive"))
      (node (ref "R51") (pin "P$1") (pinfunction "1_P$1") (pintype "passive"))
      (node (ref "R52") (pin "P$1") (pinfunction "1_P$1") (pintype "passive"))
      (node (ref "R55") (pin "P$1") (pinfunction "1_P$1") (pintype "passive"))
      (node (ref "R61") (pin "P$2") (pinfunction "2_P$2") (pintype "passive"))
      (node (ref "R62") (pin "P$1") (pinfunction "1_P$1") (pintype "passive"))
      (node (ref "R66") (pin "P$1") (pinfunction "1_P$1") (pintype "passive"))
      (node (ref "R75") (pin "P$1") (pinfunction "1_P$1") (pintype "passive"))
      (node (ref "REG3V3A") (pin "2") (pinfunction "GND_2") (pintype "power_in"))
      (node (ref "REG5VA") (pin "2") (pinfunction "GND_2") (pintype "power_in"))
      (node (ref "REG_1V8") (pin "2") (pinfunction "GND_2") (pintype "power_in"))
      (node (ref "REG_3V3D") (pin "P$2") (pinfunction "GND_P$2") (pintype "bidirectional"))
      (node (ref "REG_5VD") (pin "P$2") (pinfunction "GND_P$2") (pintype "bidirectional"))
      (node (ref "U$4") (pin "P$1") (pinfunction "P$1_P$1") (pintype "bidirectional"))
      (node (ref "U1") (pin "2") (pinfunction "VSS_2") (pintype "power_in"))
      (node (ref "~NUDEV~1") (pin "GND") (pinfunction "GND_GND") (pintype "power_in"))
    )
    (net (code "24") (name "GNDA") (class "Default")
      (node (ref "ADC1") (pin "P$3") (pinfunction "GND_P$3") (pintype "bidirectional"))
      (node (ref "ADC2") (pin "P$1") (pinfunction "ADDR_P$1") (pintype "bidirectional"))
      (node (ref "ADC2") (pin "P$3") (pinfunction "GND_P$3") (pintype "bidirectional"))
      (node (ref "BARO_ABS") (pin "P$3") (pinfunction "GND_P$3") (pintype "bidirectional"))
      (node (ref "BARO_DIF") (pin "P$3") (pinfunction "GND_P$3") (pintype "bidirectional"))
      (node (ref "C18") (pin "-") (pinfunction "-_-") (pintype "passive"))
      (node (ref "C26") (pin "-") (pinfunction "-_-") (pintype "passive"))
      (node (ref "C27") (pin "P$2") (pinfunction "2_P$2") (pintype "passive"))
      (node (ref "C32") (pin "P$1") (pinfunction "1_P$1") (pintype "passive"))
      (node (ref "C36") (pin "P$1") (pinfunction "1_P$1") (pintype "passive"))
      (node (ref "C68") (pin "P$2") (pinfunction "2_P$2") (pintype "passive"))
      (node (ref "C70") (pin "P$2") (pinfunction "2_P$2") (pintype "passive"))
      (node (ref "C71") (pin "P$2") (pinfunction "2_P$2") (pintype "passive"))
      (node (ref "C8") (pin "P$2") (pinfunction "2_P$2") (pintype "passive"))
      (node (ref "R2") (pin "P$2") (pinfunction "2_P$2") (pintype "passive"))
      (node (ref "R35") (pin "P$1") (pinfunction "1_P$1") (pintype "passive"))
      (node (ref "R39") (pin "P$2") (pinfunction "2_P$2") (pintype "passive"))
      (node (ref "R53") (pin "P$1") (pinfunction "1_P$1") (pintype "passive"))
      (node (ref "R6") (pin "P$2") (pinfunction "2_P$2") (pintype "passive"))
      (node (ref "R63") (pin "P$1") (pinfunction "1_P$1") (pintype "passive"))
      (node (ref "R68") (pin "P$1") (pinfunction "1_P$1") (pintype "passive"))
      (node (ref "U90") (pin "11") (pinfunction "V-_11") (pintype "power_in"))
      (node (ref "~NUDEV~1") (pin "GNDA") (pinfunction "GNDA_GNDA") (pintype "power_in"))
    )
    (net (code "25") (name "GPIO0_WAKEUP") (class "Default")
      (node (ref "J3&4") (pin "GPIO0_WAKEUP") (pinfunction "GPIO0_WAKEUP_GPIO0_WAKEUP") (pintype "bidirectional"))
    )
    (net (code "26") (name "GPIO12_MMC3_CLK") (class "Default")
      (node (ref "J3&4") (pin "GPIO12_MMC3_CLK") (pinfunction "GPIO12_MMC3_CLK_GPIO12_MMC3_CLK") (pintype "bidirectional"))
    )
    (net (code "27") (name "GPIO13_MMC3_CMD") (class "Default")
      (node (ref "J3&4") (pin "GPIO13_MMC3_CMD") (pinfunction "GPIO13_MMC3_CMD_GPIO13_MMC3_CMD") (pintype "bidirectional"))
    )
    (net (code "28") (name "GPIO14_MMC3_D4") (class "Default")
      (node (ref "J3&4") (pin "GPIO14_MMC3_DAT4") (pinfunction "GPIO14_MMC3_DAT4_GPIO14_MMC3_DAT4") (pintype "bidirectional"))
    )
    (net (code "29") (name "GPIO17_MMC3_D3") (class "Default")
      (node (ref "J3&4") (pin "GPIO17_MMC3_D3") (pinfunction "GPIO17_MMC3_D3_GPIO17_MMC3_D3") (pintype "bidirectional"))
    )
    (net (code "30") (name "GPIO18_MMC3_D0") (class "Default")
      (node (ref "J3&4") (pin "GPIO18_MMC3_D0") (pinfunction "GPIO18_MMC3_D0_GPIO18_MMC3_D0") (pintype "bidirectional"))
    )
    (net (code "31") (name "GPIO18_MMC3_D2") (class "Default")
      (node (ref "J3&4") (pin "GPIO20_MMC3_D2") (pinfunction "GPIO20_MMC3_D2_GPIO20_MMC3_D2") (pintype "bidirectional"))
    )
    (net (code "32") (name "GPIO19_MMC3_D1") (class "Default")
      (node (ref "J3&4") (pin "GPIO19_MMC3_D1") (pinfunction "GPIO19_MMC3_D1_GPIO19_MMC3_D1") (pintype "bidirectional"))
    )
    (net (code "33") (name "GPIO21_MMC3_D7") (class "Default")
      (node (ref "J3&4") (pin "GPIO21_MMC3_DAT7") (pinfunction "GPIO21_MMC3_DAT7_GPIO21_MMC3_DAT7") (pintype "bidirectional"))
    )
    (net (code "34") (name "GPIO22_MMC3_D6") (class "Default")
      (node (ref "J3&4") (pin "GPIO22_MMC3_DAT6") (pinfunction "GPIO22_MMC3_DAT6_GPIO22_MMC3_DAT6") (pintype "bidirectional"))
    )
    (net (code "35") (name "GPIO23_MMC3_D5") (class "Default")
      (node (ref "J3&4") (pin "GPIO23_MMC3_DAT5") (pinfunction "GPIO23_MMC3_DAT5_GPIO23_MMC3_DAT5") (pintype "bidirectional"))
    )
    (net (code "36") (name "GPIO41_OTG_ID") (class "Default")
      (node (ref "CON_OV_USB_OTG") (pin "5") (pinfunction "5_5") (pintype "bidirectional"))
      (node (ref "J3&4") (pin "USBOTG_ID") (pinfunction "USBOTG_ID_USBOTG_ID") (pintype "bidirectional"))
    )
    (net (code "37") (name "GPIO127_TS_IRQ") (class "Default")
      (node (ref "J3&4") (pin "GPIO127_TS_IRQ") (pinfunction "GPIO127_TS_IRQ_GPIO127_TS_IRQ") (pintype "bidirectional"))
    )
    (net (code "38") (name "GPIO128_GPS_PPS") (class "Default")
      (node (ref "J3&4") (pin "GPIO128_GPS_PPS") (pinfunction "GPIO128_GPS_PPS_GPIO128_GPS_PPS") (pintype "bidirectional"))
    )
    (net (code "39") (name "GPIO144_PWM9_BSP3_DX") (class "Default")
      (node (ref "J3&4") (pin "GPIO144_GPT9_PWM") (pinfunction "GPIO144_GPT9_PWM_GPIO144_GPT9_PWM") (pintype "bidirectional"))
      (node (ref "U$8") (pin "P$1") (pinfunction "P$1_P$1") (pintype "bidirectional"))
    )
    (net (code "40") (name "GPIO145_PWM10_BSP3_DR") (class "Default")
      (node (ref "J3&4") (pin "GPIO145_GPT10_PWM") (pinfunction "GPIO145_GPT10_PWM_GPIO145_GPT10_PWM") (pintype "bidirectional"))
      (node (ref "U$10") (pin "P$1") (pinfunction "P$1_P$1") (pintype "bidirectional"))
    )
    (net (code "41") (name "GPIO146_PWM11_BSP3_CLKX") (class "Default")
      (node (ref "J3&4") (pin "GPIO146_GPT11_PWM") (pinfunction "GPIO146_GPT11_PWM_GPIO146_GPT11_PWM") (pintype "bidirectional"))
      (node (ref "U$9") (pin "P$1") (pinfunction "P$1_P$1") (pintype "bidirectional"))
    )
    (net (code "42") (name "GPIO147_PWM8_BSP3_FSX") (class "Default")
      (node (ref "J3&4") (pin "GPIO147_GPT8_PWM") (pinfunction "GPIO147_GPT8_PWM_GPIO147_GPT8_PWM") (pintype "bidirectional"))
      (node (ref "U$7") (pin "P$1") (pinfunction "P$1_P$1") (pintype "bidirectional"))
    )
    (net (code "43") (name "GPIO149_MMC3_CD") (class "Default")
      (node (ref "J3&4") (pin "GPIO149_MMC3_CD") (pinfunction "GPIO149_MMC3_CD_GPIO149_MMC3_CD") (pintype "bidirectional"))
    )
    (net (code "44") (name "GPIO150_MMC3_WP") (class "Default")
      (node (ref "J3&4") (pin "GPIO150_MMC3_WP") (pinfunction "GPIO150_MMC3_WP_GPIO150_MMC3_WP") (pintype "bidirectional"))
    )
    (net (code "45") (name "GPIO163_IR_CTS3") (class "Default")
      (node (ref "J3&4") (pin "GPIO163_IR_CTS3") (pinfunction "GPIO163_IR_CTS3_GPIO163_IR_CTS3") (pintype "bidirectional"))
    )
    (net (code "46") (name "GPIO165_IR_RXD3") (class "Default")
      (node (ref "J3&4") (pin "GPIO165_IR_RXD3") (pinfunction "GPIO165_IR_RXD3_GPIO165_IR_RXD3") (pintype "bidirectional"))
      (node (ref "LT1") (pin "4") (pinfunction "A2_4") (pintype "bidirectional"))
    )
    (net (code "47") (name "GPIO166_IR_TXD3") (class "Default")
      (node (ref "J3&4") (pin "GPIO166_IR_TXD3") (pinfunction "GPIO166_IR_TXD3_GPIO166_IR_TXD3") (pintype "bidirectional"))
      (node (ref "LT1") (pin "5") (pinfunction "A1_5") (pintype "bidirectional"))
    )
    (net (code "48") (name "GPIO168_USBH_CPEN") (class "Default")
      (node (ref "J3&4") (pin "GPIO168_USBH_CPEN") (pinfunction "GPIO168_USBH_CPEN_GPIO168_USBH_CPEN") (pintype "bidirectional"))
    )
    (net (code "49") (name "GPIO170_HDQ_1WIRE") (class "Default")
      (node (ref "J3&4") (pin "GPIO170_HDQ_1WIRE") (pinfunction "GPIO170_HDQ_1WIRE_GPIO170_HDQ_1WIRE") (pintype "bidirectional"))
    )
    (net (code "50") (name "GPIO176_ETH0_IRQ") (class "Default")
      (node (ref "J3&4") (pin "GPIO176_ETH0_IRQ") (pinfunction "GPIO176_ETH0_IRQ_GPIO176_ETH0_IRQ") (pintype "bidirectional"))
    )
    (net (code "51") (name "GPIO184_SCL3") (class "Default")
      (node (ref "J3&4") (pin "GPIO184_I2C3_SCL") (pinfunction "GPIO184_I2C3_SCL_GPIO184_I2C3_SCL") (pintype "bidirectional"))
    )
    (net (code "52") (name "GPIO185_SDA3") (class "Default")
      (node (ref "J3&4") (pin "GPIO185_I2C3_SDA") (pinfunction "GPIO185_I2C3_SDA_GPIO185_I2C3_SDA") (pintype "bidirectional"))
    )
    (net (code "53") (name "HSOL") (class "Default")
      (node (ref "J3&4") (pin "HSOLF") (pinfunction "HSOLF_HSOLF") (pintype "bidirectional"))
      (node (ref "U$3") (pin "P$1") (pinfunction "P$1_P$1") (pintype "bidirectional"))
    )
    (net (code "54") (name "HSOR") (class "Default")
      (node (ref "J3&4") (pin "HSORF") (pinfunction "HSORF_HSORF") (pintype "bidirectional"))
      (node (ref "U$2") (pin "P$1") (pinfunction "P$1_P$1") (pintype "bidirectional"))
    )
    (net (code "55") (name "LED_1_G") (class "Default")
      (node (ref "IC1") (pin "5") (pinfunction "OUT0_5") (pintype "bidirectional"))
      (node (ref "LED_1") (pin "3") (pinfunction "P$3_3") (pintype "bidirectional"))
    )
    (net (code "56") (name "LED_1_R") (class "Default")
      (node (ref "IC1") (pin "6") (pinfunction "OUT1_6") (pintype "bidirectional"))
      (node (ref "LED_1") (pin "2") (pinfunction "P$2_2") (pintype "bidirectional"))
    )
    (net (code "57") (name "LED_2_G") (class "Default")
      (node (ref "IC1") (pin "7") (pinfunction "OUT2_7") (pintype "bidirectional"))
      (node (ref "LED_2") (pin "3") (pinfunction "P$3_3") (pintype "bidirectional"))
    )
    (net (code "58") (name "LED_2_R") (class "Default")
      (node (ref "IC1") (pin "8") (pinfunction "OUT3_8") (pintype "bidirectional"))
      (node (ref "LED_2") (pin "2") (pinfunction "P$2_2") (pintype "bidirectional"))
    )
    (net (code "59") (name "LED_3_G") (class "Default")
      (node (ref "IC1") (pin "9") (pinfunction "OUT4_9") (pintype "bidirectional"))
      (node (ref "LED_3") (pin "3") (pinfunction "P$3_3") (pintype "bidirectional"))
    )
    (net (code "60") (name "LED_3_R") (class "Default")
      (node (ref "IC1") (pin "10") (pinfunction "OUT5_10") (pintype "bidirectional"))
      (node (ref "LED_3") (pin "2") (pinfunction "P$2_2") (pintype "bidirectional"))
    )
    (net (code "61") (name "LED_4_G") (class "Default")
      (node (ref "IC1") (pin "11") (pinfunction "OUT6_11") (pintype "bidirectional"))
      (node (ref "LED_4") (pin "3") (pinfunction "P$3_3") (pintype "bidirectional"))
    )
    (net (code "62") (name "LED_4_R") (class "Default")
      (node (ref "IC1") (pin "12") (pinfunction "OUT7_12") (pintype "bidirectional"))
      (node (ref "LED_4") (pin "2") (pinfunction "P$2_2") (pintype "bidirectional"))
    )
    (net (code "63") (name "LINE_IN_LA") (class "Default")
      (node (ref "J3&4") (pin "AUXRF") (pinfunction "AUXRF_AUXRF") (pintype "bidirectional"))
      (node (ref "U$5") (pin "P$1") (pinfunction "P$1_P$1") (pintype "bidirectional"))
    )
    (net (code "64") (name "LINE_IN_RA") (class "Default")
      (node (ref "J3&4") (pin "AUXLF") (pinfunction "AUXLF_AUXLF") (pintype "bidirectional"))
      (node (ref "U$6") (pin "P$1") (pinfunction "P$1_P$1") (pintype "bidirectional"))
    )
    (net (code "65") (name "LT_I2C2_SCL") (class "Default")
      (node (ref "CON_I2C2") (pin "5") (pinfunction "5_5") (pintype "bidirectional"))
      (node (ref "LT_I2C2") (pin "6") (pinfunction "SCL2_6") (pintype "bidirectional"))
      (node (ref "R26") (pin "P$2") (pinfunction "2_P$2") (pintype "passive"))
      (node (ref "R44") (pin "P$1") (pinfunction "1_P$1") (pintype "passive"))
    )
    (net (code "66") (name "LT_I2C2_SDA") (class "Default")
      (node (ref "CON_I2C2") (pin "6") (pinfunction "6_6") (pintype "bidirectional"))
      (node (ref "LT_I2C2") (pin "5") (pinfunction "SDA2_5") (pintype "bidirectional"))
      (node (ref "R27") (pin "P$2") (pinfunction "2_P$2") (pintype "passive"))
      (node (ref "R43") (pin "P$1") (pinfunction "1_P$1") (pintype "passive"))
    )
    (net (code "67") (name "LT_USART1_RX") (class "Default")
      (node (ref "CON_USART1") (pin "5") (pinfunction "5_5") (pintype "bidirectional"))
      (node (ref "IC6") (pin "8") (pinfunction "R1IN_8") (pintype "input"))
      (node (ref "R37") (pin "P$1") (pinfunction "1_P$1") (pintype "passive"))
    )
    (net (code "68") (name "LT_USART1_TX") (class "Default")
      (node (ref "CON_USART1") (pin "4") (pinfunction "4_4") (pintype "bidirectional"))
      (node (ref "IC6") (pin "13") (pinfunction "T1OUT_13") (pintype "output"))
      (node (ref "R36") (pin "P$1") (pinfunction "1_P$1") (pintype "passive"))
    )
    (net (code "69") (name "L_BIAS") (class "Default")
      (node (ref "J3&4") (pin "GPIO69_L_BIAS") (pinfunction "GPIO69_L_BIAS_GPIO69_L_BIAS") (pintype "bidirectional"))
    )
    (net (code "70") (name "L_DD0") (class "Default")
      (node (ref "J3&4") (pin "GPIO70_L_DD00") (pinfunction "GPIO70_L_DD00_GPIO70_L_DD00") (pintype "bidirectional"))
    )
    (net (code "71") (name "L_DD1") (class "Default")
      (node (ref "J3&4") (pin "GPIO71_L_DD01") (pinfunction "GPIO71_L_DD01_GPIO71_L_DD01") (pintype "bidirectional"))
    )
    (net (code "72") (name "L_DD2") (class "Default")
      (node (ref "J3&4") (pin "GPIO72_L_DD02") (pinfunction "GPIO72_L_DD02_GPIO72_L_DD02") (pintype "bidirectional"))
    )
    (net (code "73") (name "L_DD3") (class "Default")
      (node (ref "J3&4") (pin "GPIO73_L_DD03") (pinfunction "GPIO73_L_DD03_GPIO73_L_DD03") (pintype "bidirectional"))
    )
    (net (code "74") (name "L_DD4") (class "Default")
      (node (ref "J3&4") (pin "GPIO74_L_DD04") (pinfunction "GPIO74_L_DD04_GPIO74_L_DD04") (pintype "bidirectional"))
    )
    (net (code "75") (name "L_DD5") (class "Default")
      (node (ref "J3&4") (pin "GPIO75_L_DD05") (pinfunction "GPIO75_L_DD05_GPIO75_L_DD05") (pintype "bidirectional"))
    )
    (net (code "76") (name "L_DD6") (class "Default")
      (node (ref "J3&4") (pin "GPIO76_L_DD06") (pinfunction "GPIO76_L_DD06_GPIO76_L_DD06") (pintype "bidirectional"))
    )
    (net (code "77") (name "L_DD7") (class "Default")
      (node (ref "J3&4") (pin "GPIO77_L_DD07") (pinfunction "GPIO77_L_DD07_GPIO77_L_DD07") (pintype "bidirectional"))
    )
    (net (code "78") (name "L_DD8") (class "Default")
      (node (ref "J3&4") (pin "GPIO78_L_DD08") (pinfunction "GPIO78_L_DD08_GPIO78_L_DD08") (pintype "bidirectional"))
    )
    (net (code "79") (name "L_DD9") (class "Default")
      (node (ref "J3&4") (pin "GPIO79_L_DD09") (pinfunction "GPIO79_L_DD09_GPIO79_L_DD09") (pintype "bidirectional"))
    )
    (net (code "80") (name "L_DD10") (class "Default")
      (node (ref "J3&4") (pin "GPIO80_L_DD10") (pinfunction "GPIO80_L_DD10_GPIO80_L_DD10") (pintype "bidirectional"))
    )
    (net (code "81") (name "L_DD11") (class "Default")
      (node (ref "J3&4") (pin "GPIO81_L_DD11") (pinfunction "GPIO81_L_DD11_GPIO81_L_DD11") (pintype "bidirectional"))
    )
    (net (code "82") (name "L_DD12") (class "Default")
      (node (ref "J3&4") (pin "GPIO82_L_DD12") (pinfunction "GPIO82_L_DD12_GPIO82_L_DD12") (pintype "bidirectional"))
    )
    (net (code "83") (name "L_DD13") (class "Default")
      (node (ref "J3&4") (pin "GPIO83_L_DD13") (pinfunction "GPIO83_L_DD13_GPIO83_L_DD13") (pintype "bidirectional"))
    )
    (net (code "84") (name "L_DD14") (class "Default")
      (node (ref "J3&4") (pin "GPIO84_L_DD14") (pinfunction "GPIO84_L_DD14_GPIO84_L_DD14") (pintype "bidirectional"))
    )
    (net (code "85") (name "L_DD15") (class "Default")
      (node (ref "J3&4") (pin "GPIO85_L_DD15") (pinfunction "GPIO85_L_DD15_GPIO85_L_DD15") (pintype "bidirectional"))
    )
    (net (code "86") (name "L_DD16") (class "Default")
      (node (ref "J3&4") (pin "GPIO86_L_DD16") (pinfunction "GPIO86_L_DD16_GPIO86_L_DD16") (pintype "bidirectional"))
    )
    (net (code "87") (name "L_DD17") (class "Default")
      (node (ref "J3&4") (pin "GPIO87_L_DD17") (pinfunction "GPIO87_L_DD17_GPIO87_L_DD17") (pintype "bidirectional"))
    )
    (net (code "88") (name "L_DD18") (class "Default")
      (node (ref "J3&4") (pin "GPIO88_L_DD18") (pinfunction "GPIO88_L_DD18_GPIO88_L_DD18") (pintype "bidirectional"))
    )
    (net (code "89") (name "L_DD19") (class "Default")
      (node (ref "J3&4") (pin "GPIO89_L_DD19") (pinfunction "GPIO89_L_DD19_GPIO89_L_DD19") (pintype "bidirectional"))
    )
    (net (code "90") (name "L_DD20") (class "Default")
      (node (ref "J3&4") (pin "GPIO90_L_DD20") (pinfunction "GPIO90_L_DD20_GPIO90_L_DD20") (pintype "bidirectional"))
    )
    (net (code "91") (name "L_DD21") (class "Default")
      (node (ref "J3&4") (pin "GPIO91_L_DD21") (pinfunction "GPIO91_L_DD21_GPIO91_L_DD21") (pintype "bidirectional"))
    )
    (net (code "92") (name "L_DD22") (class "Default")
      (node (ref "J3&4") (pin "GPIO92_L_DD22") (pinfunction "GPIO92_L_DD22_GPIO92_L_DD22") (pintype "bidirectional"))
    )
    (net (code "93") (name "L_DD23") (class "Default")
      (node (ref "J3&4") (pin "GPIO93_L_DD23") (pinfunction "GPIO93_L_DD23_GPIO93_L_DD23") (pintype "bidirectional"))
    )
    (net (code "94") (name "L_HSYNC") (class "Default")
      (node (ref "J3&4") (pin "GPIO67_L_LCLK") (pinfunction "GPIO67_L_LCLK_GPIO67_L_LCLK") (pintype "bidirectional"))
    )
    (net (code "95") (name "L_PCLK") (class "Default")
      (node (ref "J3&4") (pin "GPIO66_L_PCLK") (pinfunction "GPIO66_L_PCLK_GPIO66_L_PCLK") (pintype "bidirectional"))
    )
    (net (code "96") (name "L_VSYNC") (class "Default")
      (node (ref "J3&4") (pin "GPIO68_L_FCLK") (pinfunction "GPIO68_L_FCLK_GPIO68_L_FCLK") (pintype "bidirectional"))
    )
    (net (code "97") (name "MIC_MAIN") (class "Default")
      (node (ref "J3&4") (pin "MIC_MAIN_MF") (pinfunction "MIC_MAIN_MF_MIC_MAIN_MF") (pintype "bidirectional"))
    )
    (net (code "98") (name "MIC_SUB") (class "Default")
      (node (ref "J3&4") (pin "MIC_SUB_MF") (pinfunction "MIC_SUB_MF_MIC_SUB_MF") (pintype "bidirectional"))
    )
    (net (code "99") (name "NRESET") (class "Default")
      (node (ref "J3&4") (pin "N_MANUAL_RESET") (pinfunction "N_MANUAL_RESET_N_MANUAL_RESET") (pintype "bidirectional"))
    )
    (net (code "100") (name "Net-(ADC1-AIN1)") (class "Default")
      (node (ref "ADC1") (pin "P$5") (pinfunction "AIN1_P$5") (pintype "bidirectional"))
      (node (ref "R12") (pin "P$2") (pinfunction "2_P$2") (pintype "passive"))
      (node (ref "R53") (pin "P$2") (pinfunction "2_P$2") (pintype "passive"))
    )
    (net (code "101") (name "Net-(ADC2-AIN1)") (class "Default")
      (node (ref "ADC2") (pin "P$5") (pinfunction "AIN1_P$5") (pintype "bidirectional"))
      (node (ref "R54") (pin "P$2") (pinfunction "2_P$2") (pintype "passive"))
      (node (ref "R63") (pin "P$2") (pinfunction "2_P$2") (pintype "passive"))
    )
    (net (code "102") (name "Net-(ADC2-AIN2)") (class "Default")
      (node (ref "ADC2") (pin "P$6") (pinfunction "AIN2_P$6") (pintype "bidirectional"))
      (node (ref "R69") (pin "P$2") (pinfunction "2_P$2") (pintype "passive"))
    )
    (net (code "103") (name "Net-(ADC2-AIN3)") (class "Default")
      (node (ref "ADC2") (pin "P$7") (pinfunction "AIN3_P$7") (pintype "bidirectional"))
      (node (ref "R64") (pin "P$1") (pinfunction "1_P$1") (pintype "passive"))
      (node (ref "R68") (pin "P$2") (pinfunction "2_P$2") (pintype "passive"))
    )
    (net (code "104") (name "Net-(BARO_ABS-VO)") (class "Default")
      (node (ref "BARO_ABS") (pin "P$4") (pinfunction "VO_P$4") (pintype "bidirectional"))
      (node (ref "R22") (pin "P$2") (pinfunction "2_P$2") (pintype "passive"))
    )
    (net (code "105") (name "Net-(BARO_DIF-VO)") (class "Default")
      (node (ref "BARO_DIF") (pin "P$4") (pinfunction "VO_P$4") (pintype "bidirectional"))
      (node (ref "R1") (pin "P$1") (pinfunction "1_P$1") (pintype "passive"))
    )
    (net (code "106") (name "Net-(C5-1)") (class "Default")
      (node (ref "C5") (pin "P$1") (pinfunction "1_P$1") (pintype "passive"))
      (node (ref "IC4") (pin "2") (pinfunction "C1+_2") (pintype "passive"))
    )
    (net (code "107") (name "Net-(C5-2)") (class "Default")
      (node (ref "C5") (pin "P$2") (pinfunction "2_P$2") (pintype "passive"))
      (node (ref "IC4") (pin "4") (pinfunction "C1-_4") (pintype "passive"))
    )
    (net (code "108") (name "Net-(C6-2)") (class "Default")
      (node (ref "C6") (pin "P$2") (pinfunction "2_P$2") (pintype "passive"))
      (node (ref "IC4") (pin "3") (pinfunction "V+_3") (pintype "passive"))
    )
    (net (code "109") (name "Net-(C7-2)") (class "Default")
      (node (ref "C15") (pin "+") (pinfunction "+_+") (pintype "passive"))
      (node (ref "C7") (pin "P$2") (pinfunction "2_P$2") (pintype "passive"))
      (node (ref "L3") (pin "P$2") (pinfunction "2_P$2") (pintype "passive"))
      (node (ref "MCU") (pin "13") (pinfunction "VDDA_13") (pintype "power_in"))
    )
    (net (code "110") (name "Net-(C19-1)") (class "Default")
      (node (ref "C19") (pin "P$1") (pinfunction "1_P$1") (pintype "passive"))
      (node (ref "REG3V3A") (pin "4") (pinfunction "ADJ_4") (pintype "passive"))
    )
    (net (code "111") (name "Net-(C24-2)") (class "Default")
      (node (ref "C24") (pin "P$2") (pinfunction "2_P$2") (pintype "passive"))
      (node (ref "R10") (pin "P$1") (pinfunction "1_P$1") (pintype "passive"))
      (node (ref "R21") (pin "P$1") (pinfunction "1_P$1") (pintype "passive"))
    )
    (net (code "112") (name "Net-(C31-2)") (class "Default")
      (node (ref "C31") (pin "P$2") (pinfunction "2_P$2") (pintype "passive"))
      (node (ref "R11") (pin "P$1") (pinfunction "1_P$1") (pintype "passive"))
      (node (ref "R18") (pin "P$1") (pinfunction "1_P$1") (pintype "passive"))
    )
    (net (code "113") (name "Net-(C32-2)") (class "Default")
      (node (ref "C32") (pin "P$2") (pinfunction "2_P$2") (pintype "passive"))
      (node (ref "R11") (pin "P$2") (pinfunction "2_P$2") (pintype "passive"))
      (node (ref "U90") (pin "5") (pinfunction "+IN_5") (pintype "input"))
    )
    (net (code "114") (name "Net-(C33-1)") (class "Default")
      (node (ref "C33") (pin "P$1") (pinfunction "1_P$1") (pintype "passive"))
      (node (ref "LT_I2C2") (pin "7") (pinfunction "VREF2_7") (pintype "bidirectional"))
      (node (ref "LT_I2C2") (pin "8") (pinfunction "EN_8") (pintype "bidirectional"))
      (node (ref "R25") (pin "P$1") (pinfunction "1_P$1") (pintype "passive"))
    )
    (net (code "115") (name "Net-(C34-1)") (class "Default")
      (node (ref "C34") (pin "P$1") (pinfunction "1_P$1") (pintype "passive"))
      (node (ref "LT_I2C1") (pin "7") (pinfunction "VREF2_7") (pintype "bidirectional"))
      (node (ref "LT_I2C1") (pin "8") (pinfunction "EN_8") (pintype "bidirectional"))
      (node (ref "R30") (pin "P$2") (pinfunction "2_P$2") (pintype "passive"))
    )
    (net (code "116") (name "Net-(C35-1)") (class "Default")
      (node (ref "C35") (pin "P$1") (pinfunction "1_P$1") (pintype "passive"))
      (node (ref "IC4") (pin "5") (pinfunction "C2+_5") (pintype "passive"))
    )
    (net (code "117") (name "Net-(C35-2)") (class "Default")
      (node (ref "C35") (pin "P$2") (pinfunction "2_P$2") (pintype "passive"))
      (node (ref "IC4") (pin "6") (pinfunction "C2-_6") (pintype "passive"))
    )
    (net (code "118") (name "Net-(C36-2)") (class "Default")
      (node (ref "C36") (pin "P$2") (pinfunction "2_P$2") (pintype "passive"))
      (node (ref "R10") (pin "P$2") (pinfunction "2_P$2") (pintype "passive"))
      (node (ref "U90") (pin "12") (pinfunction "+IN_12") (pintype "input"))
    )
    (net (code "119") (name "Net-(C42-2)") (class "Default")
      (node (ref "C42") (pin "P$2") (pinfunction "2_P$2") (pintype "passive"))
      (node (ref "R58") (pin "P$2") (pinfunction "2_P$2") (pintype "passive"))
      (node (ref "R59") (pin "P$1") (pinfunction "1_P$1") (pintype "passive"))
      (node (ref "R60") (pin "P$2") (pinfunction "2_P$2") (pintype "passive"))
      (node (ref "R61") (pin "P$1") (pinfunction "1_P$1") (pintype "passive"))
    )
    (net (code "120") (name "Net-(C48-2)") (class "Default")
      (node (ref "C48") (pin "P$2") (pinfunction "2_P$2") (pintype "passive"))
      (node (ref "IC4") (pin "7") (pinfunction "V-_7") (pintype "passive"))
    )
    (net (code "121") (name "Net-(C56-1)") (class "Default")
      (node (ref "C56") (pin "P$1") (pinfunction "1_P$1") (pintype "passive"))
      (node (ref "REG5VA") (pin "4") (pinfunction "ADJ_4") (pintype "passive"))
    )
    (net (code "122") (name "Net-(C61-1)") (class "Default")
      (node (ref "C61") (pin "P$1") (pinfunction "1_P$1") (pintype "passive"))
      (node (ref "CON_OV_USB_OTG") (pin "1") (pinfunction "1_1") (pintype "bidirectional"))
      (node (ref "R66") (pin "P$2") (pinfunction "2_P$2") (pintype "passive"))
    )
    (net (code "123") (name "Net-(C63-1)") (class "Default")
      (node (ref "C63") (pin "P$1") (pinfunction "1_P$1") (pintype "passive"))
      (node (ref "IC6") (pin "2") (pinfunction "C1+_2") (pintype "passive"))
    )
    (net (code "124") (name "Net-(C63-2)") (class "Default")
      (node (ref "C63") (pin "P$2") (pinfunction "2_P$2") (pintype "passive"))
      (node (ref "IC6") (pin "4") (pinfunction "C1-_4") (pintype "passive"))
    )
    (net (code "125") (name "Net-(C64-1)") (class "Default")
      (node (ref "C64") (pin "P$1") (pinfunction "1_P$1") (pintype "passive"))
      (node (ref "IC6") (pin "5") (pinfunction "C2+_5") (pintype "passive"))
    )
    (net (code "126") (name "Net-(C64-2)") (class "Default")
      (node (ref "C64") (pin "P$2") (pinfunction "2_P$2") (pintype "passive"))
      (node (ref "IC6") (pin "6") (pinfunction "C2-_6") (pintype "passive"))
    )
    (net (code "127") (name "Net-(C65-1)") (class "Default")
      (node (ref "C65") (pin "P$1") (pinfunction "1_P$1") (pintype "passive"))
      (node (ref "IC6") (pin "3") (pinfunction "V+_3") (pintype "passive"))
    )
    (net (code "128") (name "Net-(C66-1)") (class "Default")
      (node (ref "C66") (pin "P$1") (pinfunction "1_P$1") (pintype "passive"))
      (node (ref "IC6") (pin "7") (pinfunction "V-_7") (pintype "passive"))
    )
    (net (code "129") (name "Net-(C72-2)") (class "Default")
      (node (ref "C72") (pin "P$2") (pinfunction "2_P$2") (pintype "passive"))
      (node (ref "IC3") (pin "P$2") (pinfunction "OSCI_P$2") (pintype "bidirectional"))
      (node (ref "Q3") (pin "P$3") (pinfunction "P$3_P$3") (pintype "bidirectional"))
    )
    (net (code "130") (name "Net-(C73-2)") (class "Default")
      (node (ref "C73") (pin "P$2") (pinfunction "2_P$2") (pintype "passive"))
      (node (ref "IC3") (pin "P$3") (pinfunction "OSCO_P$3") (pintype "bidirectional"))
      (node (ref "Q3") (pin "P$1") (pinfunction "P$1_P$1") (pintype "bidirectional"))
    )
    (net (code "131") (name "Net-(C74-2)") (class "Default")
      (node (ref "C74") (pin "P$2") (pinfunction "2_P$2") (pintype "passive"))
      (node (ref "FT_VREG3V3") (pin "4") (pinfunction "BYP_4") (pintype "passive"))
    )
    (net (code "132") (name "Net-(C83-1)") (class "Default")
      (node (ref "C81") (pin "+") (pinfunction "+_+") (pintype "passive"))
      (node (ref "C83") (pin "P$1") (pinfunction "1_P$1") (pintype "passive"))
      (node (ref "IC3") (pin "P$4") (pinfunction "VPHY_P$4") (pintype "bidirectional"))
      (node (ref "L2") (pin "P$2") (pinfunction "2_P$2") (pintype "passive"))
    )
    (net (code "133") (name "Net-(C84-1)") (class "Default")
      (node (ref "C82") (pin "+") (pinfunction "+_+") (pintype "passive"))
      (node (ref "C84") (pin "P$1") (pinfunction "1_P$1") (pintype "passive"))
      (node (ref "IC3") (pin "P$9") (pinfunction "VPLL_P$9") (pintype "bidirectional"))
      (node (ref "L1") (pin "P$2") (pinfunction "2_P$2") (pintype "passive"))
    )
    (net (code "134") (name "Net-(IC1-R-EXT)") (class "Default")
      (node (ref "IC1") (pin "15") (pinfunction "R-EXT_15") (pintype "bidirectional"))
      (node (ref "R13") (pin "P$2") (pinfunction "2_P$2") (pintype "passive"))
    )
    (net (code "135") (name "Net-(IC2-CLK)") (class "Default")
      (node (ref "IC2") (pin "4") (pinfunction "CLK_4") (pintype "bidirectional"))
      (node (ref "IC3") (pin "P$62") (pinfunction "EECLK_P$62") (pintype "bidirectional"))
    )
    (net (code "136") (name "Net-(IC2-CS)") (class "Default")
      (node (ref "IC2") (pin "5") (pinfunction "CS_5") (pintype "bidirectional"))
      (node (ref "IC3") (pin "P$63") (pinfunction "EECS_P$63") (pintype "bidirectional"))
    )
    (net (code "137") (name "Net-(IC2-DI)") (class "Default")
      (node (ref "IC2") (pin "3") (pinfunction "DI_3") (pintype "bidirectional"))
      (node (ref "IC3") (pin "P$61") (pinfunction "EEDATA_P$61") (pintype "bidirectional"))
      (node (ref "R77") (pin "P$1") (pinfunction "1_P$1") (pintype "passive"))
      (node (ref "R78") (pin "P$1") (pinfunction "1_P$1") (pintype "passive"))
    )
    (net (code "138") (name "Net-(IC2-DO)") (class "Default")
      (node (ref "IC2") (pin "1") (pinfunction "DO_1") (pintype "bidirectional"))
      (node (ref "R78") (pin "P$2") (pinfunction "2_P$2") (pintype "passive"))
    )
    (net (code "139") (name "Net-(IC3-ADBUS0)") (class "Default")
      (node (ref "IC3") (pin "P$16") (pinfunction "ADBUS0_P$16") (pintype "bidirectional"))
      (node (ref "R49") (pin "P$1") (pinfunction "1_P$1") (pintype "passive"))
    )
    (net (code "140") (name "Net-(IC3-ADBUS1)") (class "Default")
      (node (ref "IC3") (pin "P$17") (pinfunction "ADBUS1_P$17") (pintype "bidirectional"))
      (node (ref "R50") (pin "P$1") (pinfunction "1_P$1") (pintype "passive"))
    )
    (net (code "141") (name "Net-(IC3-BCBUS3)") (class "Default")
      (node (ref "IC3") (pin "P$54") (pinfunction "BCBUS3_P$54") (pintype "bidirectional"))
      (node (ref "R24") (pin "P$2") (pinfunction "2_P$2") (pintype "passive"))
    )
    (net (code "142") (name "Net-(IC3-BCBUS4)") (class "Default")
      (node (ref "IC3") (pin "P$55") (pinfunction "BCBUS4_P$55") (pintype "bidirectional"))
      (node (ref "R71") (pin "P$2") (pinfunction "2_P$2") (pintype "passive"))
    )
    (net (code "143") (name "Net-(IC3-REF)") (class "Default")
      (node (ref "IC3") (pin "P$6") (pinfunction "REF_P$6") (pintype "bidirectional"))
      (node (ref "R75") (pin "P$2") (pinfunction "2_P$2") (pintype "passive"))
    )
    (net (code "144") (name "Net-(IC3-RESET#)") (class "Default")
      (node (ref "IC3") (pin "P$14") (pinfunction "RESET#_P$14") (pintype "bidirectional"))
      (node (ref "R76") (pin "P$2") (pinfunction "2_P$2") (pintype "passive"))
    )
    (net (code "145") (name "Net-(LT1-OE)") (class "Default")
      (node (ref "LT1") (pin "3") (pinfunction "VCCA_3") (pintype "bidirectional"))
      (node (ref "LT1") (pin "6") (pinfunction "OE_6") (pintype "bidirectional"))
      (node (ref "R65") (pin "P$1") (pinfunction "1_P$1") (pintype "passive"))
    )
    (net (code "146") (name "Net-(LT_I2C1-SCL2)") (class "Default")
      (node (ref "CON_MC1") (pin "6") (pinfunction "6_6") (pintype "bidirectional"))
      (node (ref "CON_MC1") (pin "8") (pinfunction "8_8") (pintype "bidirectional"))
      (node (ref "CON_MC2") (pin "6") (pinfunction "6_6") (pintype "bidirectional"))
      (node (ref "CON_MC2") (pin "8") (pinfunction "8_8") (pintype "bidirectional"))
      (node (ref "LT_I2C1") (pin "6") (pinfunction "SCL2_6") (pintype "bidirectional"))
      (node (ref "R31") (pin "P$2") (pinfunction "2_P$2") (pintype "passive"))
      (node (ref "R45") (pin "P$2") (pinfunction "2_P$2") (pintype "passive"))
    )
    (net (code "147") (name "Net-(LT_I2C1-SDA2)") (class "Default")
      (node (ref "CON_MC1") (pin "5") (pinfunction "5_5") (pintype "bidirectional"))
      (node (ref "CON_MC1") (pin "7") (pinfunction "7_7") (pintype "bidirectional"))
      (node (ref "CON_MC2") (pin "5") (pinfunction "5_5") (pintype "bidirectional"))
      (node (ref "CON_MC2") (pin "7") (pinfunction "7_7") (pintype "bidirectional"))
      (node (ref "LT_I2C1") (pin "5") (pinfunction "SDA2_5") (pintype "bidirectional"))
      (node (ref "R32") (pin "P$2") (pinfunction "2_P$2") (pintype "passive"))
      (node (ref "R46") (pin "P$2") (pinfunction "2_P$2") (pintype "passive"))
    )
    (net (code "148") (name "Net-(MCU-PD0-OSC_IN)") (class "Default")
      (node (ref "MCU") (pin "5") (pinfunction "PD0-OSC_IN_5") (pintype "input"))
      (node (ref "Q7") (pin "3") (pinfunction "OUT_3") (pintype "output"))
    )
    (net (code "149") (name "Net-(R1-2)") (class "Default")
      (node (ref "R1") (pin "P$2") (pinfunction "2_P$2") (pintype "passive"))
      (node (ref "R2") (pin "P$1") (pinfunction "1_P$1") (pintype "passive"))
      (node (ref "U90") (pin "3") (pinfunction "+IN_3") (pintype "input"))
    )
    (net (code "150") (name "Net-(R3-2)") (class "Default")
      (node (ref "R3") (pin "P$2") (pinfunction "2_P$2") (pintype "passive"))
      (node (ref "R4") (pin "P$1") (pinfunction "1_P$1") (pintype "passive"))
      (node (ref "REG6V5A") (pin "1") (pinfunction "ADJ_1") (pintype "input"))
    )
    (net (code "151") (name "Net-(R14-2)") (class "Default")
      (node (ref "R14") (pin "P$2") (pinfunction "2_P$2") (pintype "passive"))
      (node (ref "REG_5VD") (pin "P$4") (pinfunction "ADJ_P$4") (pintype "bidirectional"))
    )
    (net (code "152") (name "Net-(R15-1)") (class "Default")
      (node (ref "LED_FT") (pin "A") (pinfunction "A_A") (pintype "passive"))
      (node (ref "R15") (pin "P$1") (pinfunction "1_P$1") (pintype "passive"))
    )
    (net (code "153") (name "Net-(R18-2)") (class "Default")
      (node (ref "R18") (pin "P$2") (pinfunction "2_P$2") (pintype "passive"))
      (node (ref "R20") (pin "P$1") (pinfunction "1_P$1") (pintype "passive"))
      (node (ref "U90") (pin "1") (pinfunction "OUT_1") (pintype "output"))
    )
    (net (code "154") (name "Net-(R19-1)") (class "Default")
      (node (ref "R19") (pin "P$1") (pinfunction "1_P$1") (pintype "passive"))
      (node (ref "R20") (pin "P$2") (pinfunction "2_P$2") (pintype "passive"))
      (node (ref "U90") (pin "2") (pinfunction "-IN_2") (pintype "input"))
    )
    (net (code "155") (name "Net-(R19-2)") (class "Default")
      (node (ref "R19") (pin "P$2") (pinfunction "2_P$2") (pintype "passive"))
      (node (ref "R5") (pin "P$2") (pinfunction "2_P$2") (pintype "passive"))
      (node (ref "R6") (pin "P$1") (pinfunction "1_P$1") (pintype "passive"))
    )
    (net (code "156") (name "Net-(R21-2)") (class "Default")
      (node (ref "R21") (pin "P$2") (pinfunction "2_P$2") (pintype "passive"))
      (node (ref "R47") (pin "P$1") (pinfunction "1_P$1") (pintype "passive"))
      (node (ref "U90") (pin "8") (pinfunction "OUT_8") (pintype "output"))
    )
    (net (code "157") (name "Net-(R22-1)") (class "Default")
      (node (ref "R22") (pin "P$1") (pinfunction "1_P$1") (pintype "passive"))
      (node (ref "R35") (pin "P$2") (pinfunction "2_P$2") (pintype "passive"))
      (node (ref "U90") (pin "10") (pinfunction "+IN_10") (pintype "input"))
    )
    (net (code "158") (name "Net-(R24-1)") (class "Default")
      (node (ref "LED_JTXD") (pin "A") (pinfunction "A_A") (pintype "passive"))
      (node (ref "R24") (pin "P$1") (pinfunction "1_P$1") (pintype "passive"))
    )
    (net (code "159") (name "Net-(R38-2)") (class "Default")
      (node (ref "R38") (pin "P$2") (pinfunction "2_P$2") (pintype "passive"))
      (node (ref "R39") (pin "P$1") (pinfunction "1_P$1") (pintype "passive"))
      (node (ref "R40") (pin "P$2") (pinfunction "2_P$2") (pintype "passive"))
    )
    (net (code "160") (name "Net-(R40-1)") (class "Default")
      (node (ref "R40") (pin "P$1") (pinfunction "1_P$1") (pintype "passive"))
      (node (ref "R47") (pin "P$2") (pinfunction "2_P$2") (pintype "passive"))
      (node (ref "U90") (pin "9") (pinfunction "-IN_9") (pintype "input"))
    )
    (net (code "161") (name "Net-(R48-2)") (class "Default")
      (node (ref "CON_USART1") (pin "6") (pinfunction "6_6") (pintype "bidirectional"))
      (node (ref "R48") (pin "P$2") (pinfunction "2_P$2") (pintype "passive"))
    )
    (net (code "162") (name "Net-(R55-2)") (class "Default")
      (node (ref "R55") (pin "P$2") (pinfunction "2_P$2") (pintype "passive"))
      (node (ref "R56") (pin "P$1") (pinfunction "1_P$1") (pintype "passive"))
      (node (ref "U1") (pin "8") (pinfunction "RS_8") (pintype "input"))
    )
    (net (code "163") (name "Net-(R62-2)") (class "Default")
      (node (ref "R62") (pin "P$2") (pinfunction "2_P$2") (pintype "passive"))
      (node (ref "REG_3V3D") (pin "P$4") (pinfunction "ADJ_P$4") (pintype "bidirectional"))
    )
    (net (code "164") (name "Net-(R67-2)") (class "Default")
      (node (ref "C62") (pin "+") (pinfunction "+_+") (pintype "passive"))
      (node (ref "CON_OV_USB_OTG") (pin "2") (pinfunction "2_2") (pintype "bidirectional"))
      (node (ref "R67") (pin "P$2") (pinfunction "2_P$2") (pintype "passive"))
    )
    (net (code "165") (name "Net-(R71-1)") (class "Default")
      (node (ref "LED_JRXD") (pin "A") (pinfunction "A_A") (pintype "passive"))
      (node (ref "R71") (pin "P$1") (pinfunction "1_P$1") (pintype "passive"))
    )
    (net (code "166") (name "Net-(R72-1)") (class "Default")
      (node (ref "CON_SERVOS_1") (pin "3") (pinfunction "3_3") (pintype "bidirectional"))
      (node (ref "R72") (pin "P$1") (pinfunction "1_P$1") (pintype "passive"))
    )
    (net (code "167") (name "Net-(R73-1)") (class "Default")
      (node (ref "CON_SERVOS_1") (pin "6") (pinfunction "6_6") (pintype "bidirectional"))
      (node (ref "R73") (pin "P$1") (pinfunction "1_P$1") (pintype "passive"))
    )
    (net (code "168") (name "Net-(R74-1)") (class "Default")
      (node (ref "CON_SERVOS_1") (pin "9") (pinfunction "9_9") (pintype "bidirectional"))
      (node (ref "R74") (pin "P$1") (pinfunction "1_P$1") (pintype "passive"))
    )
    (net (code "169") (name "Net-(R79-1)") (class "Default")
      (node (ref "CON_SERVOS_2") (pin "3") (pinfunction "3_3") (pintype "bidirectional"))
      (node (ref "R79") (pin "P$1") (pinfunction "1_P$1") (pintype "passive"))
    )
    (net (code "170") (name "Net-(R80-1)") (class "Default")
      (node (ref "CON_SERVOS_2") (pin "6") (pinfunction "6_6") (pintype "bidirectional"))
      (node (ref "R80") (pin "P$1") (pinfunction "1_P$1") (pintype "passive"))
    )
    (net (code "171") (name "Net-(R81-1)") (class "Default")
      (node (ref "CON_SERVOS_2") (pin "9") (pinfunction "9_9") (pintype "bidirectional"))
      (node (ref "R81") (pin "P$1") (pinfunction "1_P$1") (pintype "passive"))
    )
    (net (code "172") (name "OVERO_RXD3_3V3") (class "Default")
      (node (ref "CON_OV_UART3") (pin "2") (pinfunction "2_2") (pintype "bidirectional"))
      (node (ref "LT1") (pin "1") (pinfunction "B2_1") (pintype "bidirectional"))
      (node (ref "R49") (pin "P$2") (pinfunction "2_P$2") (pintype "passive"))
    )
    (net (code "173") (name "OVERO_TXD3_3V3") (class "Default")
      (node (ref "CON_OV_UART3") (pin "1") (pinfunction "1_1") (pintype "bidirectional"))
      (node (ref "LT1") (pin "8") (pinfunction "B1_8") (pintype "bidirectional"))
      (node (ref "R50") (pin "P$2") (pinfunction "2_P$2") (pintype "passive"))
    )
    (net (code "174") (name "OV_GPIO114_SPI1_NIRQ") (class "Default")
      (node (ref "J3&4") (pin "GPIO114_SPI1_NIRQ") (pinfunction "GPIO114_SPI1_NIRQ_GPIO114_SPI1_NIRQ") (pintype "bidirectional"))
      (node (ref "LT_3") (pin "P$7") (pinfunction "A8_P$7") (pintype "bidirectional"))
    )
    (net (code "175") (name "OV_GPIO148_TXD1") (class "Default")
      (node (ref "J3&4") (pin "GPIO148_TXD1") (pinfunction "GPIO148_TXD1_GPIO148_TXD1") (pintype "bidirectional"))
      (node (ref "LT_3") (pin "P$20") (pinfunction "A1_P$20") (pintype "bidirectional"))
    )
    (net (code "176") (name "OV_GPIO151_RXD1") (class "Default")
      (node (ref "J3&4") (pin "GPIO151_RXD1") (pinfunction "GPIO151_RXD1_GPIO151_RXD1") (pintype "bidirectional"))
      (node (ref "LT_3") (pin "P$1") (pinfunction "A2_P$1") (pintype "bidirectional"))
    )
    (net (code "177") (name "OV_GPIO171_SPI1_CLK") (class "Default")
      (node (ref "J3&4") (pin "GPIO171_SPI1_CLK") (pinfunction "GPIO171_SPI1_CLK_GPIO171_SPI1_CLK") (pintype "bidirectional"))
      (node (ref "LT_3") (pin "P$5") (pinfunction "A6_P$5") (pintype "bidirectional"))
    )
    (net (code "178") (name "OV_GPIO172_SPI1_MOSI") (class "Default")
      (node (ref "J3&4") (pin "GPIO172_SPI1_MOSI") (pinfunction "GPIO172_SPI1_MOSI_GPIO172_SPI1_MOSI") (pintype "bidirectional"))
      (node (ref "LT_3") (pin "P$4") (pinfunction "A5_P$4") (pintype "bidirectional"))
    )
    (net (code "179") (name "OV_GPIO173_SPI1_MISO") (class "Default")
      (node (ref "J3&4") (pin "GPIO173_SPI1_MISO") (pinfunction "GPIO173_SPI1_MISO_GPIO173_SPI1_MISO") (pintype "bidirectional"))
      (node (ref "LT_3") (pin "P$3") (pinfunction "A4_P$3") (pintype "bidirectional"))
    )
    (net (code "180") (name "OV_GPIO174_SPI1_CS0") (class "Default")
      (node (ref "J3&4") (pin "GPIO174_SPI1_CS0") (pinfunction "GPIO174_SPI1_CS0_GPIO174_SPI1_CS0") (pintype "bidirectional"))
      (node (ref "LT_3") (pin "P$2") (pinfunction "A3_P$2") (pintype "bidirectional"))
    )
    (net (code "181") (name "OV_GPIO175_SPI1_CS1") (class "Default")
      (node (ref "J3&4") (pin "GPIO175_SPI1_CS1") (pinfunction "GPIO175_SPI1_CS1_GPIO175_SPI1_CS1") (pintype "bidirectional"))
      (node (ref "LT_3") (pin "P$6") (pinfunction "A7_P$6") (pintype "bidirectional"))
    )
    (net (code "182") (name "OV_RXD1_3V3") (class "Default")
      (node (ref "IC4") (pin "9") (pinfunction "R1OUT_9") (pintype "output"))
      (node (ref "LT_3") (pin "P$16") (pinfunction "Y2_P$16") (pintype "bidirectional"))
      (node (ref "R42") (pin "P$1") (pinfunction "1_P$1") (pintype "passive"))
    )
    (net (code "183") (name "OV_SPI_CS0") (class "Default")
      (node (ref "CON_OV_SPI") (pin "4") (pinfunction "4_4") (pintype "bidirectional"))
      (node (ref "LT_3") (pin "P$15") (pinfunction "Y3_P$15") (pintype "bidirectional"))
    )
    (net (code "184") (name "OV_TXD1_3V3") (class "Default")
      (node (ref "IC4") (pin "11") (pinfunction "T1IN_11") (pintype "input"))
      (node (ref "LT_3") (pin "P$17") (pinfunction "Y1_P$17") (pintype "bidirectional"))
      (node (ref "R41") (pin "P$1") (pinfunction "1_P$1") (pintype "passive"))
    )
    (net (code "185") (name "OV_UART1_RXD_LT") (class "Default")
      (node (ref "CON_OV_UART1") (pin "4") (pinfunction "4_4") (pintype "bidirectional"))
      (node (ref "IC4") (pin "8") (pinfunction "R1IN_8") (pintype "input"))
      (node (ref "R42") (pin "P$2") (pinfunction "2_P$2") (pintype "passive"))
    )
    (net (code "186") (name "OV_UART1_TXD_LT") (class "Default")
      (node (ref "CON_OV_UART1") (pin "3") (pinfunction "3_3") (pintype "bidirectional"))
      (node (ref "IC4") (pin "13") (pinfunction "T1OUT_13") (pintype "output"))
      (node (ref "R41") (pin "P$2") (pinfunction "2_P$2") (pintype "passive"))
    )
    (net (code "187") (name "OV_USBH_DM") (class "Default")
      (node (ref "CON_OV_USBH") (pin "4") (pinfunction "4_4") (pintype "bidirectional"))
      (node (ref "J3&4") (pin "USBH_DM") (pinfunction "USBH_DM_USBH_DM") (pintype "bidirectional"))
    )
    (net (code "188") (name "OV_USBH_DP") (class "Default")
      (node (ref "CON_OV_USBH") (pin "3") (pinfunction "3_3") (pintype "bidirectional"))
      (node (ref "J3&4") (pin "USBH_DP") (pinfunction "USBH_DP_USBH_DP") (pintype "bidirectional"))
    )
    (net (code "189") (name "OV_USB_OTG_DM") (class "Default")
      (node (ref "CON_OV_USB_OTG") (pin "4") (pinfunction "4_4") (pintype "bidirectional"))
      (node (ref "J3&4") (pin "USBOTG_DM") (pinfunction "USBOTG_DM_USBOTG_DM") (pintype "bidirectional"))
    )
    (net (code "190") (name "OV_USB_OTG_DP") (class "Default")
      (node (ref "CON_OV_USB_OTG") (pin "3") (pinfunction "3_3") (pintype "bidirectional"))
      (node (ref "J3&4") (pin "USBOTG_DP") (pinfunction "USBOTG_DP_USBOTG_DP") (pintype "bidirectional"))
    )
    (net (code "191") (name "POWERON") (class "Default")
      (node (ref "J3&4") (pin "POWERON") (pinfunction "POWERON_POWERON") (pintype "bidirectional"))
    )
    (net (code "192") (name "PSW_1") (class "Default")
      (node (ref "C39") (pin "P$1") (pinfunction "1_P$1") (pintype "passive"))
      (node (ref "C40") (pin "+") (pinfunction "+_+") (pintype "passive"))
      (node (ref "CON_LIGHTS") (pin "2") (pinfunction "2_2") (pintype "bidirectional"))
      (node (ref "PWS1") (pin "1") (pinfunction "OUT_1") (pintype "bidirectional"))
    )
    (net (code "193") (name "PSW_2") (class "Default")
      (node (ref "C37") (pin "P$1") (pinfunction "1_P$1") (pintype "passive"))
      (node (ref "C38") (pin "+") (pinfunction "+_+") (pintype "passive"))
      (node (ref "CON_LIGHTS") (pin "4") (pinfunction "4_4") (pintype "bidirectional"))
      (node (ref "PWS2") (pin "1") (pinfunction "OUT_1") (pintype "bidirectional"))
    )
    (net (code "194") (name "PWM0") (class "Default")
      (node (ref "J3&4") (pin "PWM0") (pinfunction "PWM0_PWM0") (pintype "bidirectional"))
    )
    (net (code "195") (name "PWM1") (class "Default")
      (node (ref "J3&4") (pin "PWM1") (pinfunction "PWM1_PWM1") (pintype "bidirectional"))
    )
    (net (code "196") (name "PWR_SW1") (class "Default")
      (node (ref "MCU") (pin "10") (pinfunction "PC2-ADC12_10") (pintype "bidirectional"))
      (node (ref "PWS1") (pin "4") (pinfunction "EN_4") (pintype "bidirectional"))
    )
    (net (code "197") (name "PWR_SW2") (class "Default")
      (node (ref "MCU") (pin "9") (pinfunction "PC1-ADC11_9") (pintype "bidirectional"))
      (node (ref "PWS2") (pin "4") (pinfunction "EN_4") (pintype "bidirectional"))
    )
    (net (code "198") (name "STM_BAT_MONITOR") (class "Default")
      (node (ref "MCU") (pin "14") (pinfunction "PA0-WKUP/USART2CTS/ADC0/TIM2CH2_14") (pintype "bidirectional"))
      (node (ref "R16") (pin "P$1") (pinfunction "1_P$1") (pintype "passive"))
      (node (ref "R17") (pin "P$2") (pinfunction "2_P$2") (pintype "passive"))
    )
    (net (code "199") (name "STM_BOOT0") (class "Default")
      (node (ref "CON_SPARE") (pin "3") (pinfunction "3_3") (pintype "bidirectional"))
      (node (ref "MCU") (pin "60") (pinfunction "BOOT0_60") (pintype "input"))
      (node (ref "R23") (pin "P$2") (pinfunction "2_P$2") (pintype "passive"))
    )
    (net (code "200") (name "STM_CAN_RX") (class "Default")
      (node (ref "MCU") (pin "44") (pinfunction "PA11-USART1CTS_44") (pintype "bidirectional"))
      (node (ref "U1") (pin "4") (pinfunction "RXD_4") (pintype "output"))
    )
    (net (code "201") (name "STM_CAN_TX") (class "Default")
      (node (ref "MCU") (pin "45") (pinfunction "PA12-USART1RTS_45") (pintype "bidirectional"))
      (node (ref "U1") (pin "1") (pinfunction "TXD_1") (pintype "input"))
    )
    (net (code "202") (name "STM_I2C1_SCL") (class "Default")
      (node (ref "LT_I2C1") (pin "3") (pinfunction "SCL1_3") (pintype "bidirectional"))
      (node (ref "MCU") (pin "58") (pinfunction "PB6-I2C1SCL/TIM4CH1-USART1TX_58") (pintype "bidirectional"))
      (node (ref "R29") (pin "P$2") (pinfunction "2_P$2") (pintype "passive"))
      (node (ref "R31") (pin "P$1") (pinfunction "1_P$1") (pintype "passive"))
    )
    (net (code "203") (name "STM_I2C1_SDA") (class "Default")
      (node (ref "LT_I2C1") (pin "4") (pinfunction "SDA1_4") (pintype "bidirectional"))
      (node (ref "MCU") (pin "59") (pinfunction "PB7-I2C1SDA/TIM4CH2-USART1RX_59") (pintype "bidirectional"))
      (node (ref "R28") (pin "P$2") (pinfunction "2_P$2") (pintype "passive"))
      (node (ref "R32") (pin "P$1") (pinfunction "1_P$1") (pintype "passive"))
    )
    (net (code "204") (name "STM_I2C2_SCL") (class "Default")
      (node (ref "ADC1") (pin "P$10") (pinfunction "SCL_P$10") (pintype "bidirectional"))
      (node (ref "ADC2") (pin "P$10") (pinfunction "SCL_P$10") (pintype "bidirectional"))
      (node (ref "CON_I2C_IMU") (pin "2") (pinfunction "2_2") (pintype "bidirectional"))
      (node (ref "LT_I2C2") (pin "3") (pinfunction "SCL1_3") (pintype "bidirectional"))
      (node (ref "MCU") (pin "29") (pinfunction "PB10-I2C2SCL/USART3TX_29") (pintype "bidirectional"))
      (node (ref "R26") (pin "P$1") (pinfunction "1_P$1") (pintype "passive"))
      (node (ref "R33") (pin "P$1") (pinfunction "1_P$1") (pintype "passive"))
    )
    (net (code "205") (name "STM_I2C2_SDA") (class "Default")
      (node (ref "ADC1") (pin "P$9") (pinfunction "SDA_P$9") (pintype "bidirectional"))
      (node (ref "ADC2") (pin "P$9") (pinfunction "SDA_P$9") (pintype "bidirectional"))
      (node (ref "CON_I2C_IMU") (pin "3") (pinfunction "3_3") (pintype "bidirectional"))
      (node (ref "LT_I2C2") (pin "4") (pinfunction "SDA1_4") (pintype "bidirectional"))
      (node (ref "MCU") (pin "30") (pinfunction "PB11-I2C2SDA/USART3RX_30") (pintype "bidirectional"))
      (node (ref "R27") (pin "P$1") (pinfunction "1_P$1") (pintype "passive"))
      (node (ref "R34") (pin "P$1") (pinfunction "1_P$1") (pintype "passive"))
    )
    (net (code "206") (name "STM_JTAG_TCK") (class "Default")
      (node (ref "IC3") (pin "P$38") (pinfunction "BDBUS0_P$38") (pintype "bidirectional"))
      (node (ref "MCU") (pin "49") (pinfunction "PA14/JTCK/SWCLK_49") (pintype "bidirectional"))
    )
    (net (code "207") (name "STM_JTAG_TDI") (class "Default")
      (node (ref "IC3") (pin "P$39") (pinfunction "BDBUS1_P$39") (pintype "bidirectional"))
      (node (ref "MCU") (pin "50") (pinfunction "PA15/JTDI-TIM2CH1ETR/SPI1NSS_50") (pintype "bidirectional"))
    )
    (net (code "208") (name "STM_JTAG_TDO") (class "Default")
      (node (ref "IC3") (pin "P$40") (pinfunction "BDBUS2_P$40") (pintype "bidirectional"))
      (node (ref "MCU") (pin "55") (pinfunction "PB3/JTDO-TIM2CH2/SPI1SCK_55") (pintype "bidirectional"))
    )
    (net (code "209") (name "STM_JTAG_TMS") (class "Default")
      (node (ref "IC3") (pin "P$41") (pinfunction "BDBUS3_P$41") (pintype "bidirectional"))
      (node (ref "MCU") (pin "46") (pinfunction "PA13/JTMS/SWDIO_46") (pintype "bidirectional"))
    )
    (net (code "210") (name "STM_JTAG_TRST") (class "Default")
      (node (ref "IC3") (pin "P$43") (pinfunction "BDBUS4_P$43") (pintype "bidirectional"))
      (node (ref "MCU") (pin "56") (pinfunction "PB4/JNTRST-TIM3CH1/SPI1MISO_56") (pintype "bidirectional"))
    )
    (net (code "211") (name "STM_LED_CLK") (class "Default")
      (node (ref "IC1") (pin "3") (pinfunction "CLK_3") (pintype "bidirectional"))
      (node (ref "MCU") (pin "41") (pinfunction "PA8-USART1CK/MCO_41") (pintype "bidirectional"))
      (node (ref "R51") (pin "P$2") (pinfunction "2_P$2") (pintype "passive"))
    )
    (net (code "212") (name "STM_LED_DATA") (class "Default")
      (node (ref "IC1") (pin "2") (pinfunction "SDI_2") (pintype "bidirectional"))
      (node (ref "MCU") (pin "4") (pinfunction "PC15-OSC32_OUT_4") (pintype "bidirectional"))
      (node (ref "R52") (pin "P$2") (pinfunction "2_P$2") (pintype "passive"))
    )
    (net (code "213") (name "STM_RESET") (class "Default")
      (node (ref "C9") (pin "P$2") (pinfunction "2_P$2") (pintype "passive"))
      (node (ref "IC3") (pin "P$45") (pinfunction "BDBUS6_P$45") (pintype "bidirectional"))
      (node (ref "MCU") (pin "7") (pinfunction "NRST_7") (pintype "bidirectional"))
      (node (ref "R7") (pin "P$1") (pinfunction "1_P$1") (pintype "passive"))
    )
    (net (code "214") (name "STM_SERVO1") (class "Default")
      (node (ref "MCU") (pin "37") (pinfunction "PC6-TIM3CH1_37") (pintype "bidirectional"))
      (node (ref "R72") (pin "P$2") (pinfunction "2_P$2") (pintype "passive"))
    )
    (net (code "215") (name "STM_SERVO2") (class "Default")
      (node (ref "MCU") (pin "38") (pinfunction "PC7-TIM3CH2_38") (pintype "bidirectional"))
      (node (ref "R73") (pin "P$2") (pinfunction "2_P$2") (pintype "passive"))
    )
    (net (code "216") (name "STM_SERVO3") (class "Default")
      (node (ref "MCU") (pin "39") (pinfunction "PC8-TIM3CH3_39") (pintype "bidirectional"))
      (node (ref "R74") (pin "P$2") (pinfunction "2_P$2") (pintype "passive"))
    )
    (net (code "217") (name "STM_SERVO4") (class "Default")
      (node (ref "MCU") (pin "40") (pinfunction "PC9-TIM3CH4_40") (pintype "bidirectional"))
      (node (ref "R79") (pin "P$2") (pinfunction "2_P$2") (pintype "passive"))
    )
    (net (code "218") (name "STM_SERVO5") (class "Default")
      (node (ref "MCU") (pin "61") (pinfunction "PB8-TIM4CH3-I2C1SCL_61") (pintype "bidirectional"))
      (node (ref "R80") (pin "P$2") (pinfunction "2_P$2") (pintype "passive"))
    )
    (net (code "219") (name "STM_SERVO6") (class "Default")
      (node (ref "MCU") (pin "62") (pinfunction "PB9-TIM4CH4-I2C1SDA_62") (pintype "bidirectional"))
      (node (ref "R81") (pin "P$2") (pinfunction "2_P$2") (pintype "passive"))
    )
    (net (code "220") (name "STM_SPI1_DRDY") (class "Default")
      (node (ref "CON_OV_SPI") (pin "8") (pinfunction "8_8") (pintype "bidirectional"))
      (node (ref "LT_3") (pin "P$10") (pinfunction "Y8_P$10") (pintype "bidirectional"))
      (node (ref "MCU") (pin "24") (pinfunction "PC4-ADC14_24") (pintype "bidirectional"))
    )
    (net (code "221") (name "STM_SPI1_MISO") (class "Default")
      (node (ref "CON_OV_SPI") (pin "6") (pinfunction "6_6") (pintype "bidirectional"))
      (node (ref "LT_3") (pin "P$14") (pinfunction "Y4_P$14") (pintype "bidirectional"))
      (node (ref "MCU") (pin "22") (pinfunction "PA6-SPI1MISO/ADC6/TIM3CH1_22") (pintype "bidirectional"))
    )
    (net (code "222") (name "STM_SPI1_MOSI") (class "Default")
      (node (ref "CON_OV_SPI") (pin "7") (pinfunction "7_7") (pintype "bidirectional"))
      (node (ref "LT_3") (pin "P$13") (pinfunction "Y5_P$13") (pintype "bidirectional"))
      (node (ref "MCU") (pin "23") (pinfunction "PA7-SPI1MOSI/ADC7/TIM3CH2_23") (pintype "bidirectional"))
    )
    (net (code "223") (name "STM_SPI1_NSS") (class "Default")
      (node (ref "LT_3") (pin "P$11") (pinfunction "Y7_P$11") (pintype "bidirectional"))
      (node (ref "MCU") (pin "20") (pinfunction "PA4-SPI1NSS/ADC4/USART2CK_20") (pintype "bidirectional"))
    )
    (net (code "224") (name "STM_SPI1_SCK") (class "Default")
      (node (ref "CON_OV_SPI") (pin "5") (pinfunction "5_5") (pintype "bidirectional"))
      (node (ref "LT_3") (pin "P$12") (pinfunction "Y6_P$12") (pintype "bidirectional"))
      (node (ref "MCU") (pin "21") (pinfunction "PA5-SPI1SCK/ADC5_21") (pintype "bidirectional"))
    )
    (net (code "225") (name "STM_SPI2_EEPROM_SS") (class "Default")
      (node (ref "CON_SPI_IMU") (pin "12") (pinfunction "12_12") (pintype "bidirectional"))
      (node (ref "MCU") (pin "3") (pinfunction "PC14-OSC32_IN_3") (pintype "bidirectional"))
    )
    (net (code "226") (name "STM_SPI2_IMU_DRDY") (class "Default")
      (node (ref "CON_SPI_IMU") (pin "9") (pinfunction "9_9") (pintype "bidirectional"))
      (node (ref "MCU") (pin "28") (pinfunction "PB2/BOOT1_28") (pintype "bidirectional"))
    )
    (net (code "227") (name "STM_SPI2_MAG_DRDY") (class "Default")
      (node (ref "CON_SPI_IMU") (pin "10") (pinfunction "10_10") (pintype "bidirectional"))
      (node (ref "MCU") (pin "57") (pinfunction "PB5-I2C1SMBAI-TIM3CH2/SPI1MOSI_57") (pintype "bidirectional"))
    )
    (net (code "228") (name "STM_SPI2_MAG_RESET") (class "Default")
      (node (ref "CON_SPI_IMU") (pin "11") (pinfunction "11_11") (pintype "bidirectional"))
      (node (ref "MCU") (pin "2") (pinfunction "PC13-TAMPER-RTC_2") (pintype "bidirectional"))
    )
    (net (code "229") (name "STM_SPI2_MAG_SS") (class "Default")
      (node (ref "CON_SPI_IMU") (pin "8") (pinfunction "8_8") (pintype "bidirectional"))
      (node (ref "MCU") (pin "53") (pinfunction "PC12-USART3CK_53") (pintype "bidirectional"))
    )
    (net (code "230") (name "STM_SPI2_MISO") (class "Default")
      (node (ref "CON_SPI_IMU") (pin "5") (pinfunction "5_5") (pintype "bidirectional"))
      (node (ref "MCU") (pin "35") (pinfunction "PB14-SPI2MISO/USART3RTS_35") (pintype "bidirectional"))
    )
    (net (code "231") (name "STM_SPI2_MOSI") (class "Default")
      (node (ref "CON_SPI_IMU") (pin "4") (pinfunction "4_4") (pintype "bidirectional"))
      (node (ref "MCU") (pin "36") (pinfunction "PB15-SPI2MOSI_36") (pintype "bidirectional"))
    )
    (net (code "232") (name "STM_SPI2_NSS") (class "Default")
      (node (ref "CON_SPI_IMU") (pin "7") (pinfunction "7_7") (pintype "bidirectional"))
      (node (ref "MCU") (pin "33") (pinfunction "PB12-SPI2NSS/I2C2SMBAI/USART3CK_33") (pintype "bidirectional"))
    )
    (net (code "233") (name "STM_SPI2_SCK") (class "Default")
      (node (ref "CON_SPI_IMU") (pin "6") (pinfunction "6_6") (pintype "bidirectional"))
      (node (ref "MCU") (pin "34") (pinfunction "PB13-SPI2SCK/USART3CTS_34") (pintype "bidirectional"))
    )
    (net (code "234") (name "STM_USART1_RX") (class "Default")
      (node (ref "IC6") (pin "9") (pinfunction "R1OUT_9") (pintype "output"))
      (node (ref "MCU") (pin "43") (pinfunction "PA10-USART1RX_43") (pintype "bidirectional"))
      (node (ref "R37") (pin "P$2") (pinfunction "2_P$2") (pintype "passive"))
    )
    (net (code "235") (name "STM_USART1_TX") (class "Default")
      (node (ref "IC6") (pin "11") (pinfunction "T1IN_11") (pintype "input"))
      (node (ref "MCU") (pin "42") (pinfunction "PA9-USART1TX_42") (pintype "bidirectional"))
      (node (ref "R36") (pin "P$2") (pinfunction "2_P$2") (pintype "passive"))
    )
    (net (code "236") (name "STM_USART2_RX") (class "Default")
      (node (ref "CON_USART2") (pin "5") (pinfunction "5_5") (pintype "bidirectional"))
      (node (ref "MCU") (pin "17") (pinfunction "PA3-USART2RX/ADC3/TIM2CH4_17") (pintype "bidirectional"))
    )
    (net (code "237") (name "STM_USART2_TX") (class "Default")
      (node (ref "CON_USART2") (pin "4") (pinfunction "4_4") (pintype "bidirectional"))
      (node (ref "MCU") (pin "16") (pinfunction "PA2-USART2TX/ADC2/TIM2CH3_16") (pintype "bidirectional"))
    )
    (net (code "238") (name "STM_USART3_RX") (class "Default")
      (node (ref "CON_USART3") (pin "5") (pinfunction "5_5") (pintype "bidirectional"))
      (node (ref "MCU") (pin "52") (pinfunction "PC11-USART3RX_52") (pintype "bidirectional"))
    )
    (net (code "239") (name "STM_USART3_TX") (class "Default")
      (node (ref "CON_USART3") (pin "4") (pinfunction "4_4") (pintype "bidirectional"))
      (node (ref "MCU") (pin "51") (pinfunction "PC10-USART3TX_51") (pintype "bidirectional"))
    )
    (net (code "240") (name "ST_UART1_TRIG") (class "Default")
      (node (ref "MCU") (pin "15") (pinfunction "PA1-USART2RTS/ADC1/TIM2CH2_15") (pintype "bidirectional"))
      (node (ref "R48") (pin "P$1") (pinfunction "1_P$1") (pintype "passive"))
    )
    (net (code "241") (name "SYS_EN") (class "Default")
      (node (ref "J3&4") (pin "SYSEN") (pinfunction "SYSEN_SYSEN") (pintype "bidirectional"))
      (node (ref "REG_1V8") (pin "3") (pinfunction "EN_3") (pintype "input"))
    )
    (net (code "242") (name "USBH_VBUS") (class "Default")
      (node (ref "J3&4") (pin "USBH_VBUS") (pinfunction "USBH_VBUS_USBH_VBUS") (pintype "bidirectional"))
      (node (ref "R70") (pin "P$2") (pinfunction "2_P$2") (pintype "passive"))
    )
    (net (code "243") (name "USB_OTG_VBUS") (class "Default")
      (node (ref "J3&4") (pin "USBOTG_VBUS") (pinfunction "USBOTG_VBUS_USBOTG_VBUS") (pintype "bidirectional"))
      (node (ref "R67") (pin "P$1") (pinfunction "1_P$1") (pintype "passive"))
    )
    (net (code "244") (name "VBACKUP") (class "Default")
      (node (ref "J3&4") (pin "VBACKUP") (pinfunction "VBACKUP_VBACKUP") (pintype "bidirectional"))
    )
    (net (code "245") (name "VREF") (class "Default")
      (node (ref "U1") (pin "5") (pinfunction "VREF_5") (pintype "power_in"))
    )
    (net (code "246") (name "V_PRESSURE_ABS_AMP") (class "Default")
      (node (ref "ADC2") (pin "P$4") (pinfunction "AIN0_P$4") (pintype "bidirectional"))
      (node (ref "C24") (pin "P$1") (pinfunction "1_P$1") (pintype "passive"))
      (node (ref "U90") (pin "13") (pinfunction "-IN_13") (pintype "input"))
      (node (ref "U90") (pin "14") (pinfunction "OUT_14") (pintype "output"))
    )
    (net (code "247") (name "V_PRESSURE_DIFF_AMP") (class "Default")
      (node (ref "ADC1") (pin "P$4") (pinfunction "AIN0_P$4") (pintype "bidirectional"))
      (node (ref "C31") (pin "P$1") (pinfunction "1_P$1") (pintype "passive"))
      (node (ref "R69") (pin "P$1") (pinfunction "1_P$1") (pintype "passive"))
      (node (ref "U90") (pin "6") (pinfunction "-IN_6") (pintype "input"))
      (node (ref "U90") (pin "7") (pinfunction "OUT_7") (pintype "output"))
    )
    (net (code "248") (name "XXX_STM_SPARE_1") (class "Default")
      (node (ref "CON_SPARE") (pin "5") (pinfunction "5_5") (pintype "bidirectional"))
      (node (ref "MCU") (pin "25") (pinfunction "PC5-ADC15_25") (pintype "bidirectional"))
    )
    (net (code "249") (name "XXX_STM_SPARE_2") (class "Default")
      (node (ref "CON_SPARE") (pin "4") (pinfunction "4_4") (pintype "bidirectional"))
      (node (ref "MCU") (pin "11") (pinfunction "PC3-ADC13_11") (pintype "bidirectional"))
    )
    (net (code "250") (name "XXX_STM_SPARE_6") (class "Default")
      (node (ref "CON_SPARE") (pin "6") (pinfunction "6_6") (pintype "bidirectional"))
      (node (ref "MCU") (pin "26") (pinfunction "PB0-ADC8/TIM3CH3_26") (pintype "bidirectional"))
    )
    (net (code "251") (name "XXX_STM_SPARE_7") (class "Default")
      (node (ref "CON_SPARE") (pin "7") (pinfunction "7_7") (pintype "bidirectional"))
      (node (ref "MCU") (pin "27") (pinfunction "PB1-ADC9/TIM3CH4_27") (pintype "bidirectional"))
    )
    (net (code "252") (name "XXX_STM_SPARE_8") (class "Default")
      (node (ref "CON_SPARE") (pin "8") (pinfunction "8_8") (pintype "bidirectional"))
      (node (ref "MCU") (pin "54") (pinfunction "PD2-TIM3ETR_54") (pintype "bidirectional"))
    )
    (net (code "253") (name "X_ADDR_01") (class "Default")
      (node (ref "J3&4") (pin "EM_A1") (pinfunction "EM_A1_EM_A1") (pintype "bidirectional"))
    )
    (net (code "254") (name "X_ADDR_02") (class "Default")
      (node (ref "J3&4") (pin "EM_A2") (pinfunction "EM_A2_EM_A2") (pintype "bidirectional"))
    )
    (net (code "255") (name "X_ADDR_03") (class "Default")
      (node (ref "J3&4") (pin "EM_A3") (pinfunction "EM_A3_EM_A3") (pintype "bidirectional"))
    )
    (net (code "256") (name "X_ADDR_04") (class "Default")
      (node (ref "J3&4") (pin "EM_A4") (pinfunction "EM_A4_EM_A4") (pintype "bidirectional"))
    )
    (net (code "257") (name "X_ADDR_05") (class "Default")
      (node (ref "J3&4") (pin "EM_A5") (pinfunction "EM_A5_EM_A5") (pintype "bidirectional"))
    )
    (net (code "258") (name "X_ADDR_06") (class "Default")
      (node (ref "J3&4") (pin "EM_A6") (pinfunction "EM_A6_EM_A6") (pintype "bidirectional"))
    )
    (net (code "259") (name "X_ADDR_07") (class "Default")
      (node (ref "J3&4") (pin "EM_A7") (pinfunction "EM_A7_EM_A7") (pintype "bidirectional"))
    )
    (net (code "260") (name "X_ADDR_08") (class "Default")
      (node (ref "J3&4") (pin "EM_A8") (pinfunction "EM_A8_EM_A8") (pintype "bidirectional"))
    )
    (net (code "261") (name "X_ADDR_09") (class "Default")
      (node (ref "J3&4") (pin "EM_A9") (pinfunction "EM_A9_EM_A9") (pintype "bidirectional"))
    )
    (net (code "262") (name "X_ADDR_10") (class "Default")
      (node (ref "J3&4") (pin "EM_A10") (pinfunction "EM_A10_EM_A10") (pintype "bidirectional"))
    )
    (net (code "263") (name "X_CLK") (class "Default")
      (node (ref "J3&4") (pin "EM_CLK") (pinfunction "EM_CLK_EM_CLK") (pintype "bidirectional"))
    )
    (net (code "264") (name "X_DATA_0") (class "Default")
      (node (ref "J3&4") (pin "EM_D0") (pinfunction "EM_D0_EM_D0") (pintype "bidirectional"))
    )
    (net (code "265") (name "X_DATA_1") (class "Default")
      (node (ref "J3&4") (pin "EM_D1") (pinfunction "EM_D1_EM_D1") (pintype "bidirectional"))
    )
    (net (code "266") (name "X_DATA_2") (class "Default")
      (node (ref "J3&4") (pin "EM_D2") (pinfunction "EM_D2_EM_D2") (pintype "bidirectional"))
    )
    (net (code "267") (name "X_DATA_3") (class "Default")
      (node (ref "J3&4") (pin "EM_D3") (pinfunction "EM_D3_EM_D3") (pintype "bidirectional"))
    )
    (net (code "268") (name "X_DATA_4") (class "Default")
      (node (ref "J3&4") (pin "EM_D4") (pinfunction "EM_D4_EM_D4") (pintype "bidirectional"))
    )
    (net (code "269") (name "X_DATA_5") (class "Default")
      (node (ref "J3&4") (pin "EM_D5") (pinfunction "EM_D5_EM_D5") (pintype "bidirectional"))
    )
    (net (code "270") (name "X_DATA_6") (class "Default")
      (node (ref "J3&4") (pin "EM_D6") (pinfunction "EM_D6_EM_D6") (pintype "bidirectional"))
    )
    (net (code "271") (name "X_DATA_7") (class "Default")
      (node (ref "J3&4") (pin "EM_D7") (pinfunction "EM_D7_EM_D7") (pintype "bidirectional"))
    )
    (net (code "272") (name "X_DATA_8") (class "Default")
      (node (ref "J3&4") (pin "EM_D8") (pinfunction "EM_D8_EM_D8") (pintype "bidirectional"))
    )
    (net (code "273") (name "X_DATA_9") (class "Default")
      (node (ref "J3&4") (pin "EM_D9") (pinfunction "EM_D9_EM_D9") (pintype "bidirectional"))
    )
    (net (code "274") (name "X_DATA_10") (class "Default")
      (node (ref "J3&4") (pin "EM_D10") (pinfunction "EM_D10_EM_D10") (pintype "bidirectional"))
    )
    (net (code "275") (name "X_DATA_11") (class "Default")
      (node (ref "J3&4") (pin "EM_D11") (pinfunction "EM_D11_EM_D11") (pintype "bidirectional"))
    )
    (net (code "276") (name "X_DATA_12") (class "Default")
      (node (ref "J3&4") (pin "EM_D12") (pinfunction "EM_D12_EM_D12") (pintype "bidirectional"))
    )
    (net (code "277") (name "X_DATA_13") (class "Default")
      (node (ref "J3&4") (pin "EM_D13") (pinfunction "EM_D13_EM_D13") (pintype "bidirectional"))
    )
    (net (code "278") (name "X_DATA_14") (class "Default")
      (node (ref "J3&4") (pin "EM_D14") (pinfunction "EM_D14_EM_D14") (pintype "bidirectional"))
    )
    (net (code "279") (name "X_DATA_15") (class "Default")
      (node (ref "J3&4") (pin "EM_D15") (pinfunction "EM_D15_EM_D15") (pintype "bidirectional"))
    )
    (net (code "280") (name "X_GPIO64_ETH0_NRESET") (class "Default")
      (node (ref "J3&4") (pin "GPIO64_ETH0_NRESET") (pinfunction "GPIO64_ETH0_NRESET_GPIO64_ETH0_NRESET") (pintype "bidirectional"))
    )
    (net (code "281") (name "X_GPIO65_ETH1_IRQ1") (class "Default")
      (node (ref "J3&4") (pin "GPIO65_ETH1_IRQ1") (pinfunction "GPIO65_ETH1_IRQ1_GPIO65_ETH1_IRQ1") (pintype "bidirectional"))
    )
    (net (code "282") (name "X_NADV_ALE") (class "Default")
      (node (ref "J3&4") (pin "EM_NADV_ALE") (pinfunction "EM_NADV_ALE_EM_NADV_ALE") (pintype "bidirectional"))
    )
    (net (code "283") (name "X_NBE0") (class "Default")
      (node (ref "J3&4") (pin "EM_NBE0") (pinfunction "EM_NBE0_EM_NBE0") (pintype "bidirectional"))
    )
    (net (code "284") (name "X_NBE1") (class "Default")
      (node (ref "J3&4") (pin "EM_NBE1") (pinfunction "EM_NBE1_EM_NBE1") (pintype "bidirectional"))
    )
    (net (code "285") (name "X_NCS0") (class "Default")
      (node (ref "J3&4") (pin "EM_NCS0") (pinfunction "EM_NCS0_EM_NCS0") (pintype "bidirectional"))
    )
    (net (code "286") (name "X_NCS1") (class "Default")
      (node (ref "J3&4") (pin "EM_NCS1") (pinfunction "EM_NCS1_EM_NCS1") (pintype "bidirectional"))
    )
    (net (code "287") (name "X_NCS4") (class "Default")
      (node (ref "J3&4") (pin "EM_NCS4") (pinfunction "EM_NCS4_EM_NCS4") (pintype "bidirectional"))
    )
    (net (code "288") (name "X_NCS5_ETHO") (class "Default")
      (node (ref "J3&4") (pin "EM_NCS5_ETH0") (pinfunction "EM_NCS5_ETH0_EM_NCS5_ETH0") (pintype "bidirectional"))
    )
    (net (code "289") (name "X_NCS6") (class "Default")
      (node (ref "J3&4") (pin "EM_NCS6") (pinfunction "EM_NCS6_EM_NCS6") (pintype "bidirectional"))
    )
    (net (code "290") (name "X_NMWP") (class "Default")
      (node (ref "J3&4") (pin "EM_NWP") (pinfunction "EM_NWP_EM_NWP") (pintype "bidirectional"))
    )
    (net (code "291") (name "X_NOE") (class "Default")
      (node (ref "J3&4") (pin "EM_NOE") (pinfunction "EM_NOE_EM_NOE") (pintype "bidirectional"))
    )
    (net (code "292") (name "X_NPWE") (class "Default")
      (node (ref "J3&4") (pin "EM_NWE") (pinfunction "EM_NWE_EM_NWE") (pintype "bidirectional"))
    )
    (net (code "293") (name "X_RDY") (class "Default")
      (node (ref "J3&4") (pin "EM_WAIT0") (pinfunction "EM_WAIT0_EM_WAIT0") (pintype "bidirectional"))
    )
    (net (code "294") (name "unconnected-(ADC1-AIN2-PadP$6)") (class "Default")
      (node (ref "ADC1") (pin "P$6") (pinfunction "AIN2_P$6") (pintype "bidirectional"))
    )
    (net (code "295") (name "unconnected-(ADC1-AIN3-PadP$7)") (class "Default")
      (node (ref "ADC1") (pin "P$7") (pinfunction "AIN3_P$7") (pintype "bidirectional"))
    )
    (net (code "296") (name "unconnected-(CON_USB1-Pad4)") (class "Default")
      (node (ref "CON_USB1") (pin "4") (pinfunction "4_4") (pintype "input"))
    )
    (net (code "297") (name "unconnected-(IC1-SDO-Pad14)") (class "Default")
      (node (ref "IC1") (pin "14") (pinfunction "SDO_14") (pintype "bidirectional"))
    )
    (net (code "298") (name "unconnected-(IC3-ACBUS0-PadP$26)") (class "Default")
      (node (ref "IC3") (pin "P$26") (pinfunction "ACBUS0_P$26") (pintype "bidirectional"))
    )
    (net (code "299") (name "unconnected-(IC3-ACBUS1-PadP$27)") (class "Default")
      (node (ref "IC3") (pin "P$27") (pinfunction "ACBUS1_P$27") (pintype "bidirectional"))
    )
    (net (code "300") (name "unconnected-(IC3-ACBUS2-PadP$28)") (class "Default")
      (node (ref "IC3") (pin "P$28") (pinfunction "ACBUS2_P$28") (pintype "bidirectional"))
    )
    (net (code "301") (name "unconnected-(IC3-ACBUS3-PadP$29)") (class "Default")
      (node (ref "IC3") (pin "P$29") (pinfunction "ACBUS3_P$29") (pintype "bidirectional"))
    )
    (net (code "302") (name "unconnected-(IC3-ACBUS4-PadP$30)") (class "Default")
      (node (ref "IC3") (pin "P$30") (pinfunction "ACBUS4_P$30") (pintype "bidirectional"))
    )
    (net (code "303") (name "unconnected-(IC3-ACBUS5-PadP$32)") (class "Default")
      (node (ref "IC3") (pin "P$32") (pinfunction "ACBUS5_P$32") (pintype "bidirectional"))
    )
    (net (code "304") (name "unconnected-(IC3-ACBUS6-PadP$33)") (class "Default")
      (node (ref "IC3") (pin "P$33") (pinfunction "ACBUS6_P$33") (pintype "bidirectional"))
    )
    (net (code "305") (name "unconnected-(IC3-ACBUS7-PadP$34)") (class "Default")
      (node (ref "IC3") (pin "P$34") (pinfunction "ACBUS7_P$34") (pintype "bidirectional"))
    )
    (net (code "306") (name "unconnected-(IC3-ADBUS2-PadP$18)") (class "Default")
      (node (ref "IC3") (pin "P$18") (pinfunction "ADBUS2_P$18") (pintype "bidirectional"))
    )
    (net (code "307") (name "unconnected-(IC3-ADBUS3-PadP$19)") (class "Default")
      (node (ref "IC3") (pin "P$19") (pinfunction "ADBUS3_P$19") (pintype "bidirectional"))
    )
    (net (code "308") (name "unconnected-(IC3-ADBUS4-PadP$21)") (class "Default")
      (node (ref "IC3") (pin "P$21") (pinfunction "ADBUS4_P$21") (pintype "bidirectional"))
    )
    (net (code "309") (name "unconnected-(IC3-ADBUS5-PadP$22)") (class "Default")
      (node (ref "IC3") (pin "P$22") (pinfunction "ADBUS5_P$22") (pintype "bidirectional"))
    )
    (net (code "310") (name "unconnected-(IC3-ADBUS6-PadP$23)") (class "Default")
      (node (ref "IC3") (pin "P$23") (pinfunction "ADBUS6_P$23") (pintype "bidirectional"))
    )
    (net (code "311") (name "unconnected-(IC3-ADBUS7-PadP$24)") (class "Default")
      (node (ref "IC3") (pin "P$24") (pinfunction "ADBUS7_P$24") (pintype "bidirectional"))
    )
    (net (code "312") (name "unconnected-(IC3-BCBUS0-PadP$48)") (class "Default")
      (node (ref "IC3") (pin "P$48") (pinfunction "BCBUS0_P$48") (pintype "bidirectional"))
    )
    (net (code "313") (name "unconnected-(IC3-BCBUS1-PadP$52)") (class "Default")
      (node (ref "IC3") (pin "P$52") (pinfunction "BCBUS1_P$52") (pintype "bidirectional"))
    )
    (net (code "314") (name "unconnected-(IC3-BCBUS2-PadP$53)") (class "Default")
      (node (ref "IC3") (pin "P$53") (pinfunction "BCBUS2_P$53") (pintype "bidirectional"))
    )
    (net (code "315") (name "unconnected-(IC3-BCBUS5-PadP$57)") (class "Default")
      (node (ref "IC3") (pin "P$57") (pinfunction "BCBUS5_P$57") (pintype "bidirectional"))
    )
    (net (code "316") (name "unconnected-(IC3-BCBUS6-PadP$58)") (class "Default")
      (node (ref "IC3") (pin "P$58") (pinfunction "BCBUS6_P$58") (pintype "bidirectional"))
    )
    (net (code "317") (name "unconnected-(IC3-BCBUS7-PadP$59)") (class "Default")
      (node (ref "IC3") (pin "P$59") (pinfunction "BCBUS7_P$59") (pintype "bidirectional"))
    )
    (net (code "318") (name "unconnected-(IC3-BDBUS5-PadP$44)") (class "Default")
      (node (ref "IC3") (pin "P$44") (pinfunction "BDBUS5_P$44") (pintype "bidirectional"))
    )
    (net (code "319") (name "unconnected-(IC3-BDBUS7-PadP$46)") (class "Default")
      (node (ref "IC3") (pin "P$46") (pinfunction "BDBUS7_P$46") (pintype "bidirectional"))
    )
    (net (code "320") (name "unconnected-(IC3-PWREN#-PadP$60)") (class "Default")
      (node (ref "IC3") (pin "P$60") (pinfunction "PWREN#_P$60") (pintype "bidirectional"))
    )
    (net (code "321") (name "unconnected-(IC3-SUSPEND#-PadP$36)") (class "Default")
      (node (ref "IC3") (pin "P$36") (pinfunction "SUSPEND#_P$36") (pintype "bidirectional"))
    )
    (net (code "322") (name "unconnected-(IC4A-~{INVALID}-Pad10)") (class "Default")
      (node (ref "IC4") (pin "10") (pinfunction "~{INVALID}_10") (pintype "input"))
    )
    (net (code "323") (name "unconnected-(IC6A-~{INVALID}-Pad10)") (class "Default")
      (node (ref "IC6") (pin "10") (pinfunction "~{INVALID}_10") (pintype "input"))
    )
    (net (code "324") (name "unconnected-(J3&4-NC-PadNC@62)") (class "Default")
      (node (ref "J3&4") (pin "NC@62") (pinfunction "NC_NC@62") (pintype "bidirectional"))
    )
    (net (code "325") (name "unconnected-(J3&4-NC-PadNC@63)") (class "Default")
      (node (ref "J3&4") (pin "NC@63") (pinfunction "NC_NC@63") (pintype "bidirectional"))
    )
    (net (code "326") (name "unconnected-(PWS1-OC-Pad3)") (class "Default")
      (node (ref "PWS1") (pin "3") (pinfunction "OC_3") (pintype "bidirectional"))
    )
    (net (code "327") (name "unconnected-(PWS2-OC-Pad3)") (class "Default")
      (node (ref "PWS2") (pin "3") (pinfunction "OC_3") (pintype "bidirectional"))
    )
    (net (code "328") (name "unconnected-(Q7-TRI-Pad1)") (class "Default")
      (node (ref "Q7") (pin "1") (pinfunction "TRI_1") (pintype "output"))
    )
    (net (code "329") (name "unconnected-(REG_1V8-ADJ-Pad4)") (class "Default")
      (node (ref "REG_1V8") (pin "4") (pinfunction "ADJ_4") (pintype "passive"))
    )
    (net (code "330") (name "unconnected-(REG_3V3D-IHN-PadP$5)") (class "Default")
      (node (ref "REG_3V3D") (pin "P$5") (pinfunction "IHN_P$5") (pintype "bidirectional"))
    )
    (net (code "331") (name "unconnected-(REG_5VD-IHN-PadP$5)") (class "Default")
      (node (ref "REG_5VD") (pin "P$5") (pinfunction "IHN_P$5") (pintype "bidirectional"))
    )
  )
)
